# Full_bridge-2-Buck_drives_-_8.net
KiCad netlist of a schematic drawn in Altium Designer
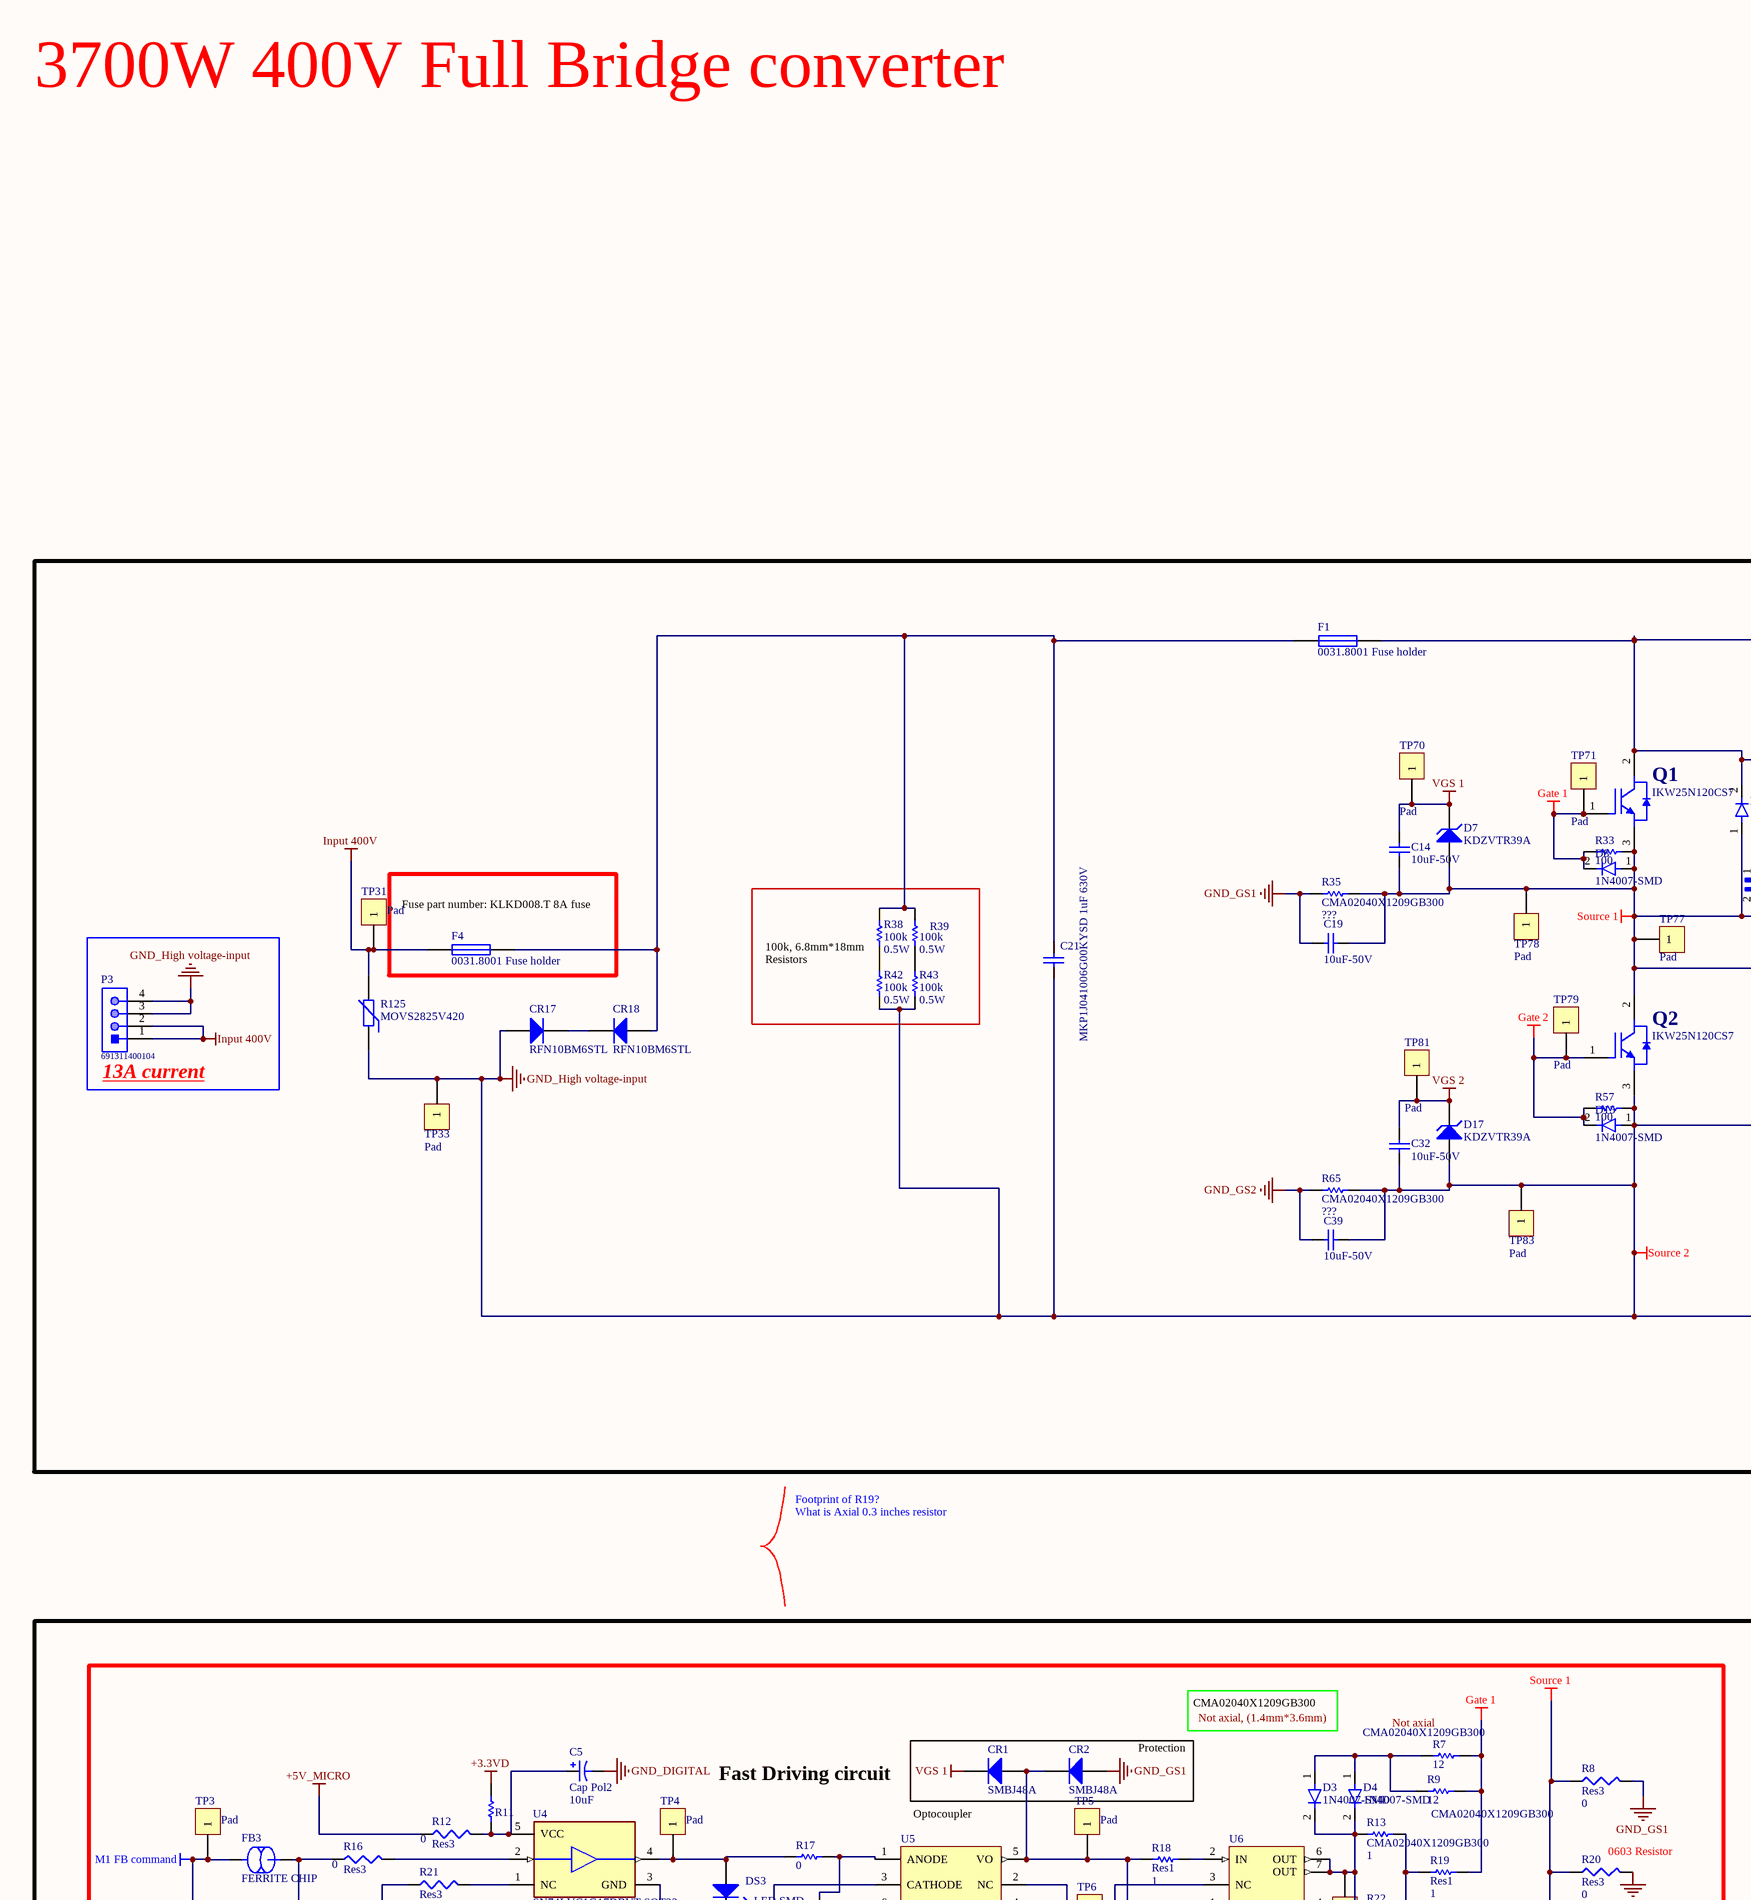
[diagram p0: Full bridge-2-Buck drives - 8.SchDoc, top left]
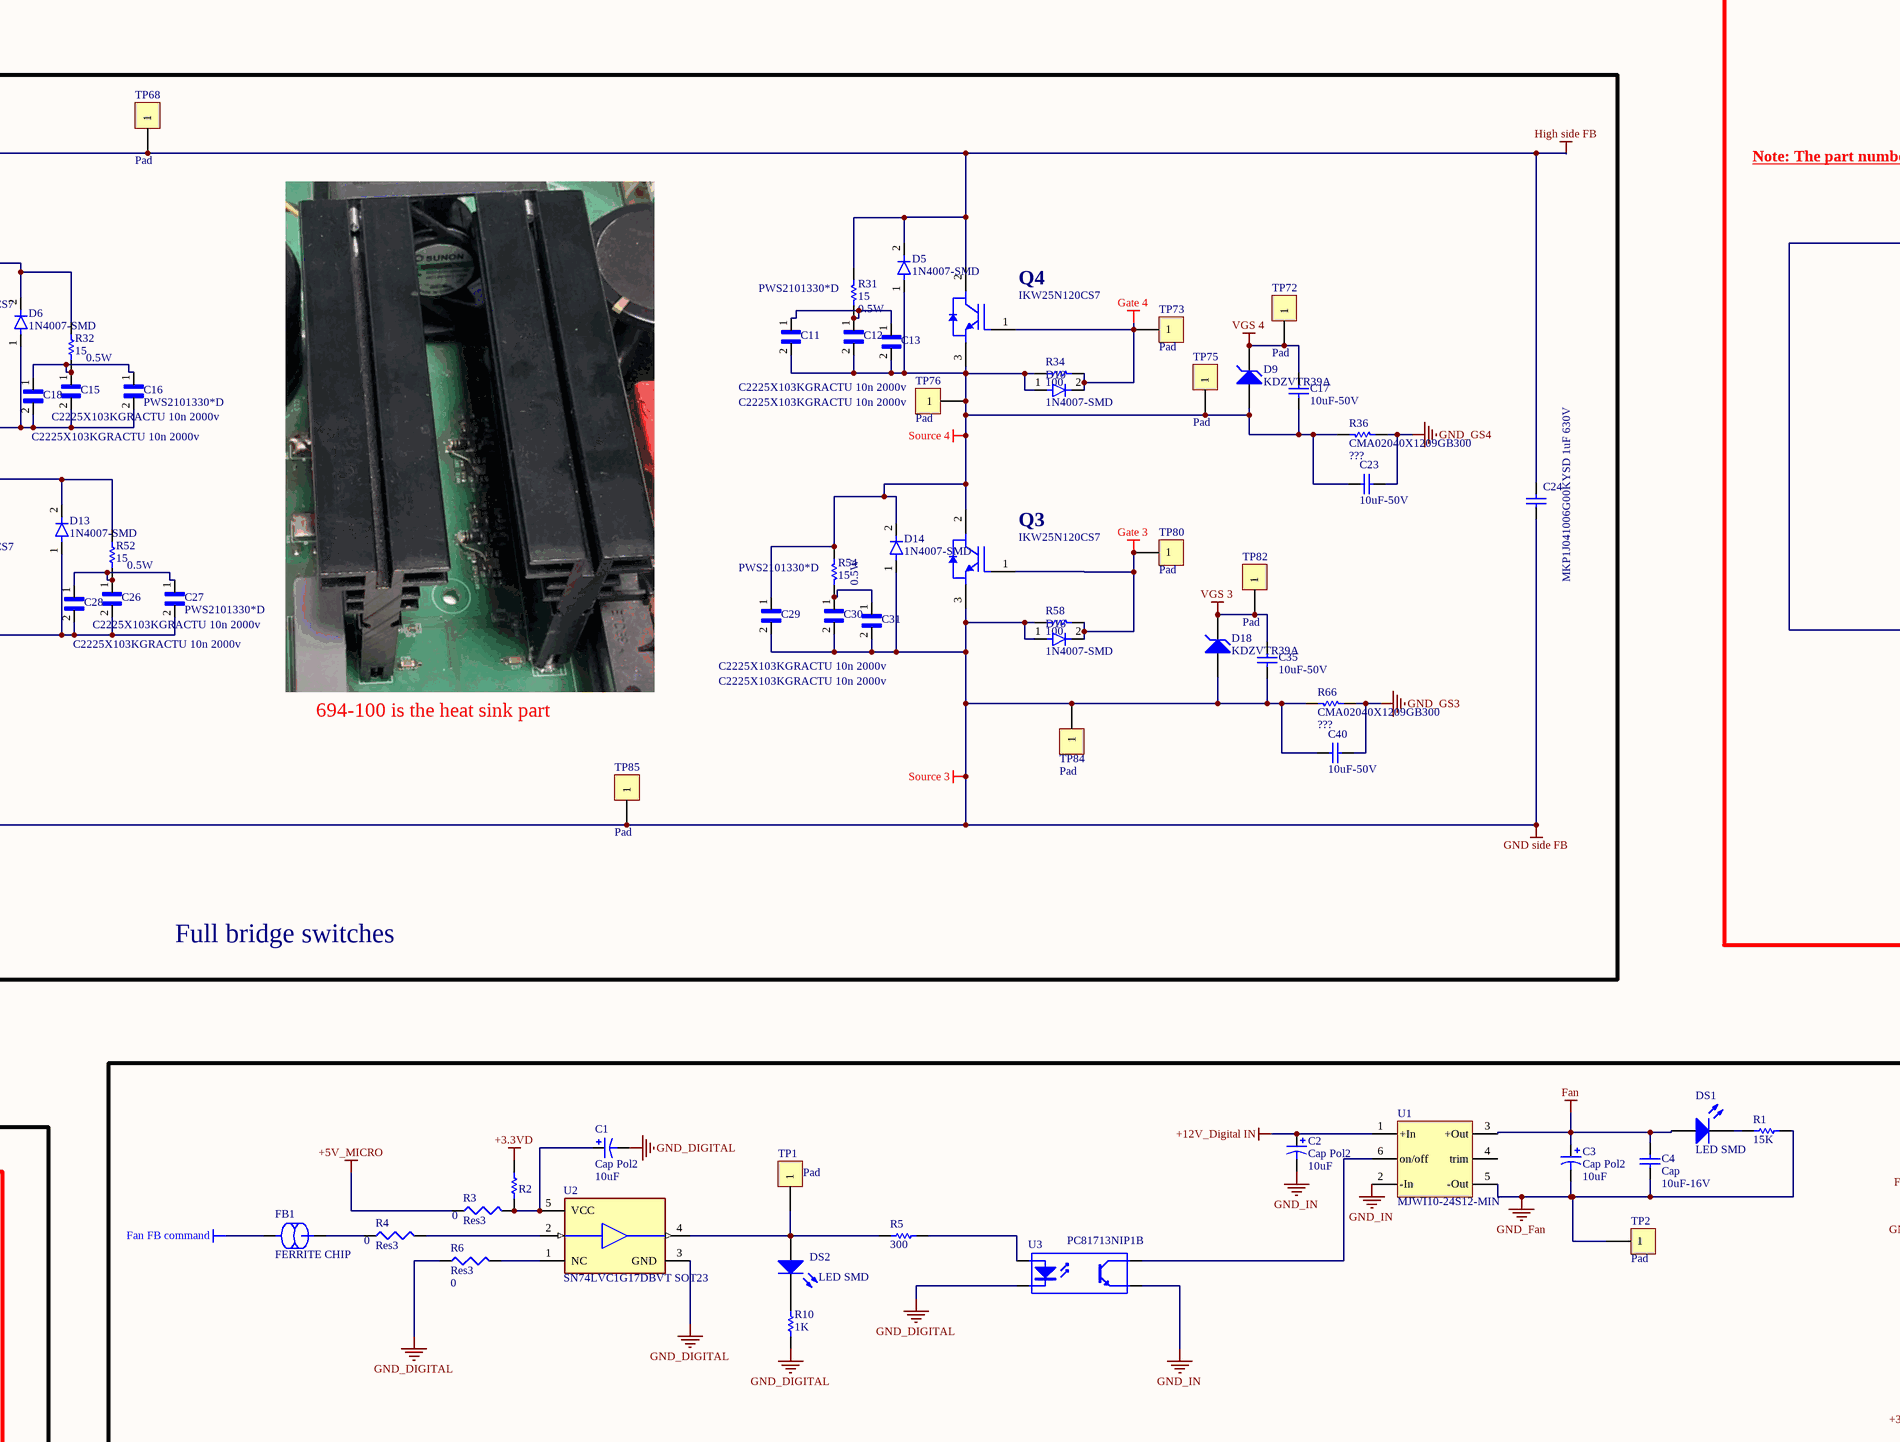
[diagram p1: Full bridge-2-Buck drives - 8.SchDoc, top middle]
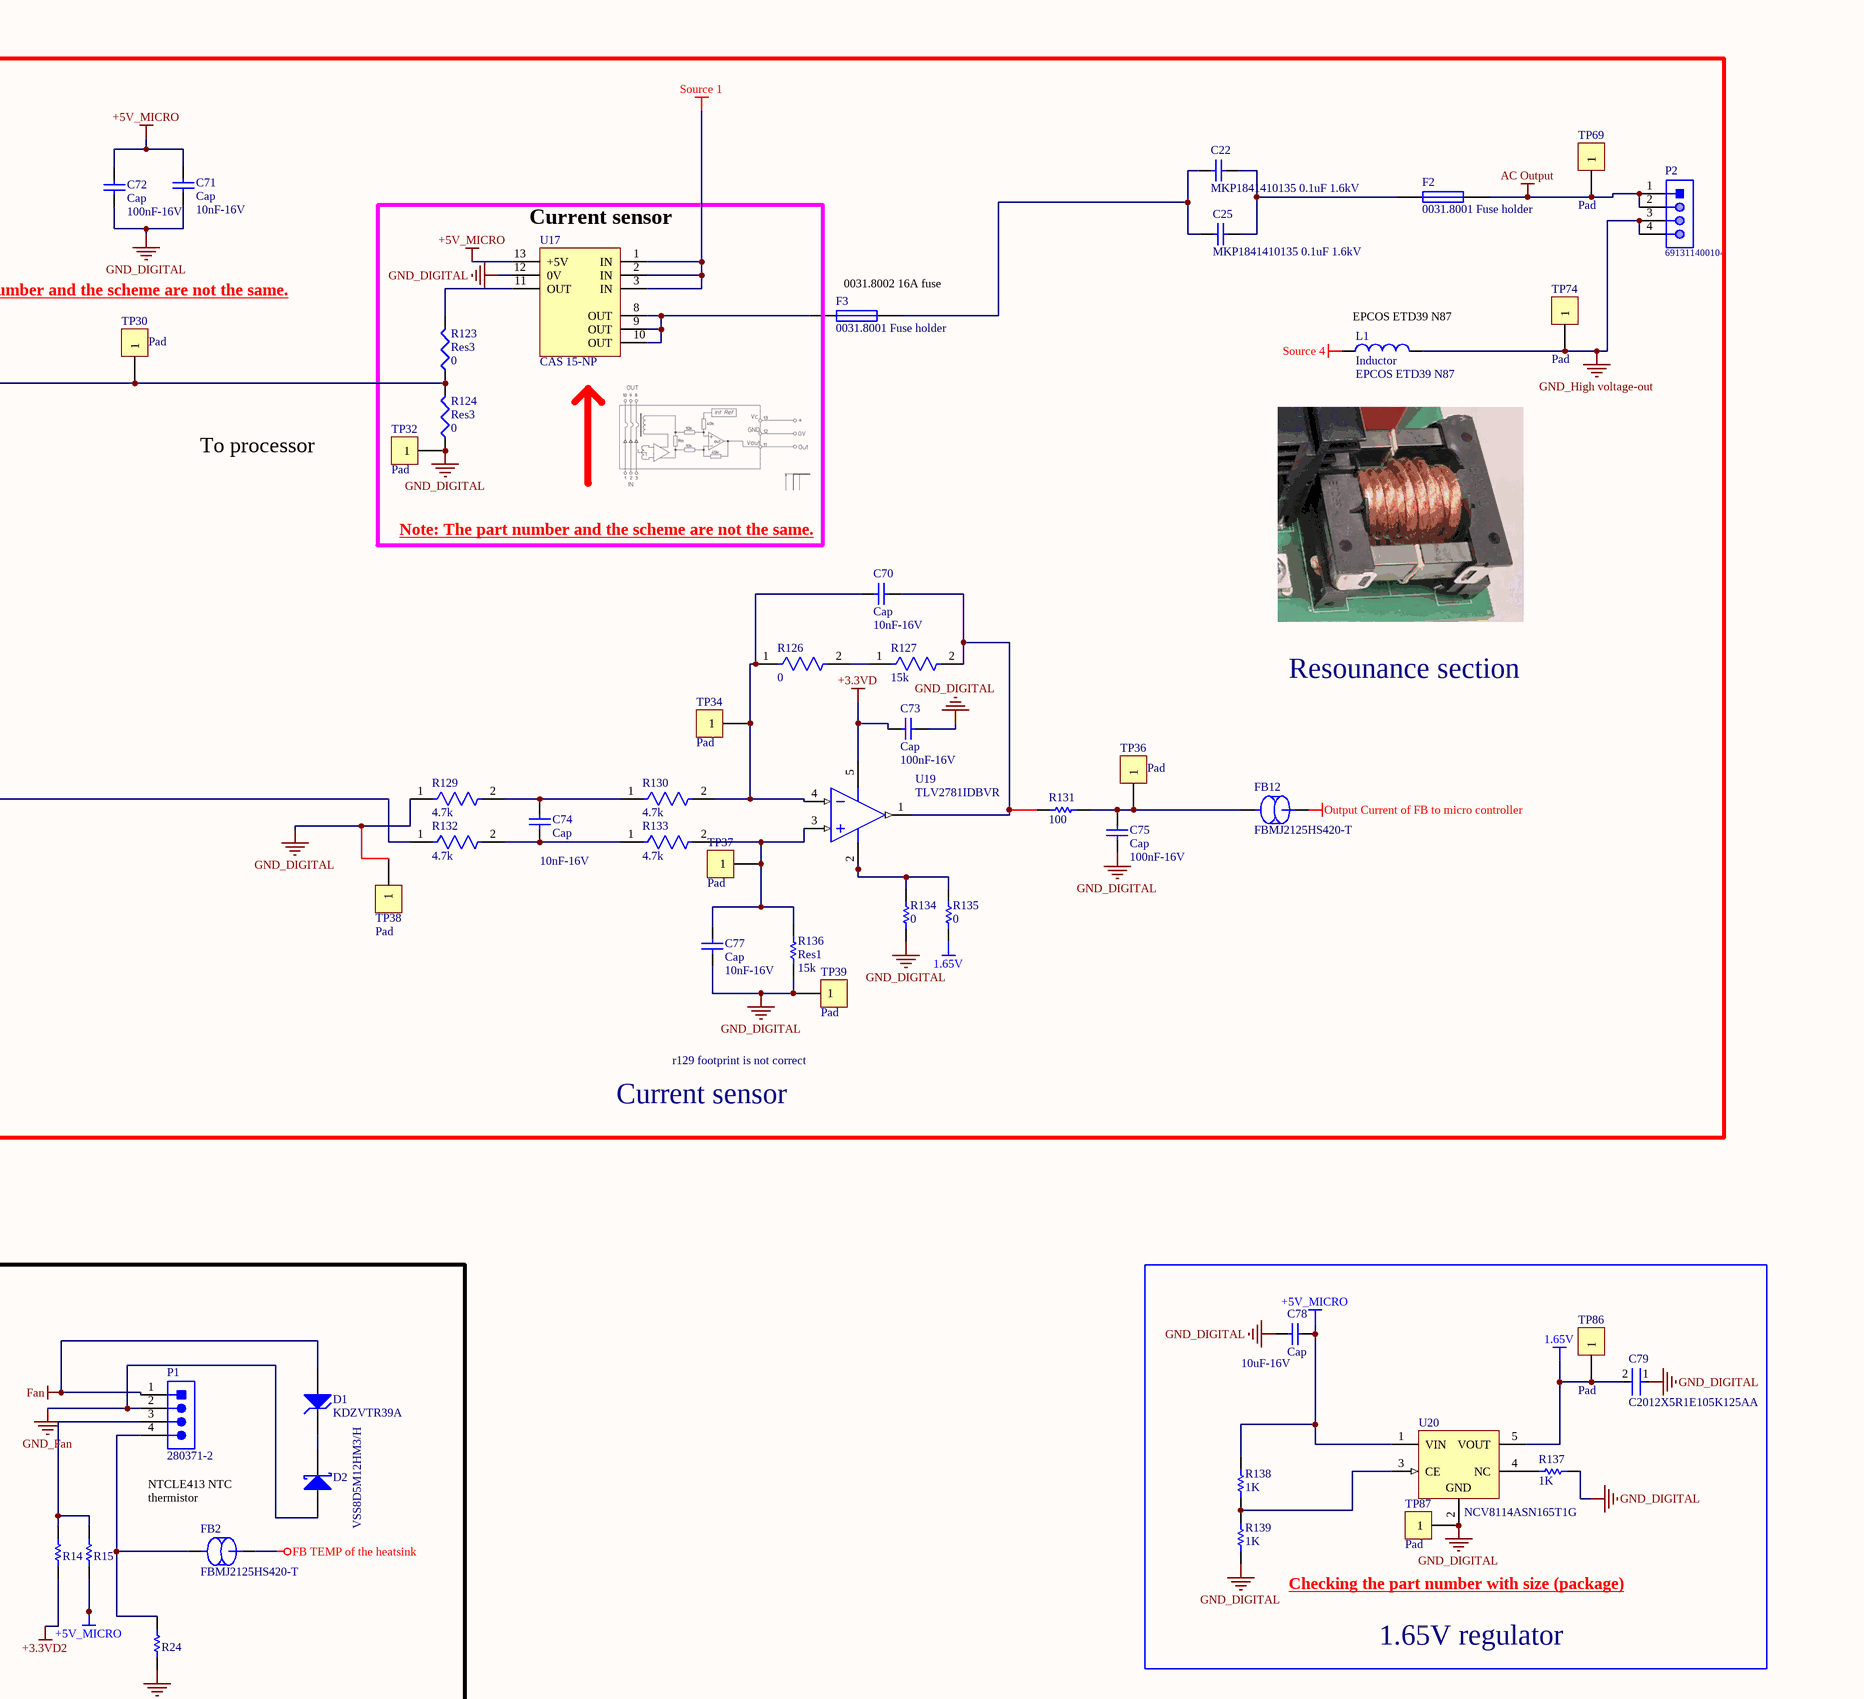
[diagram p2: Full bridge-2-Buck drives - 8.SchDoc, top right]
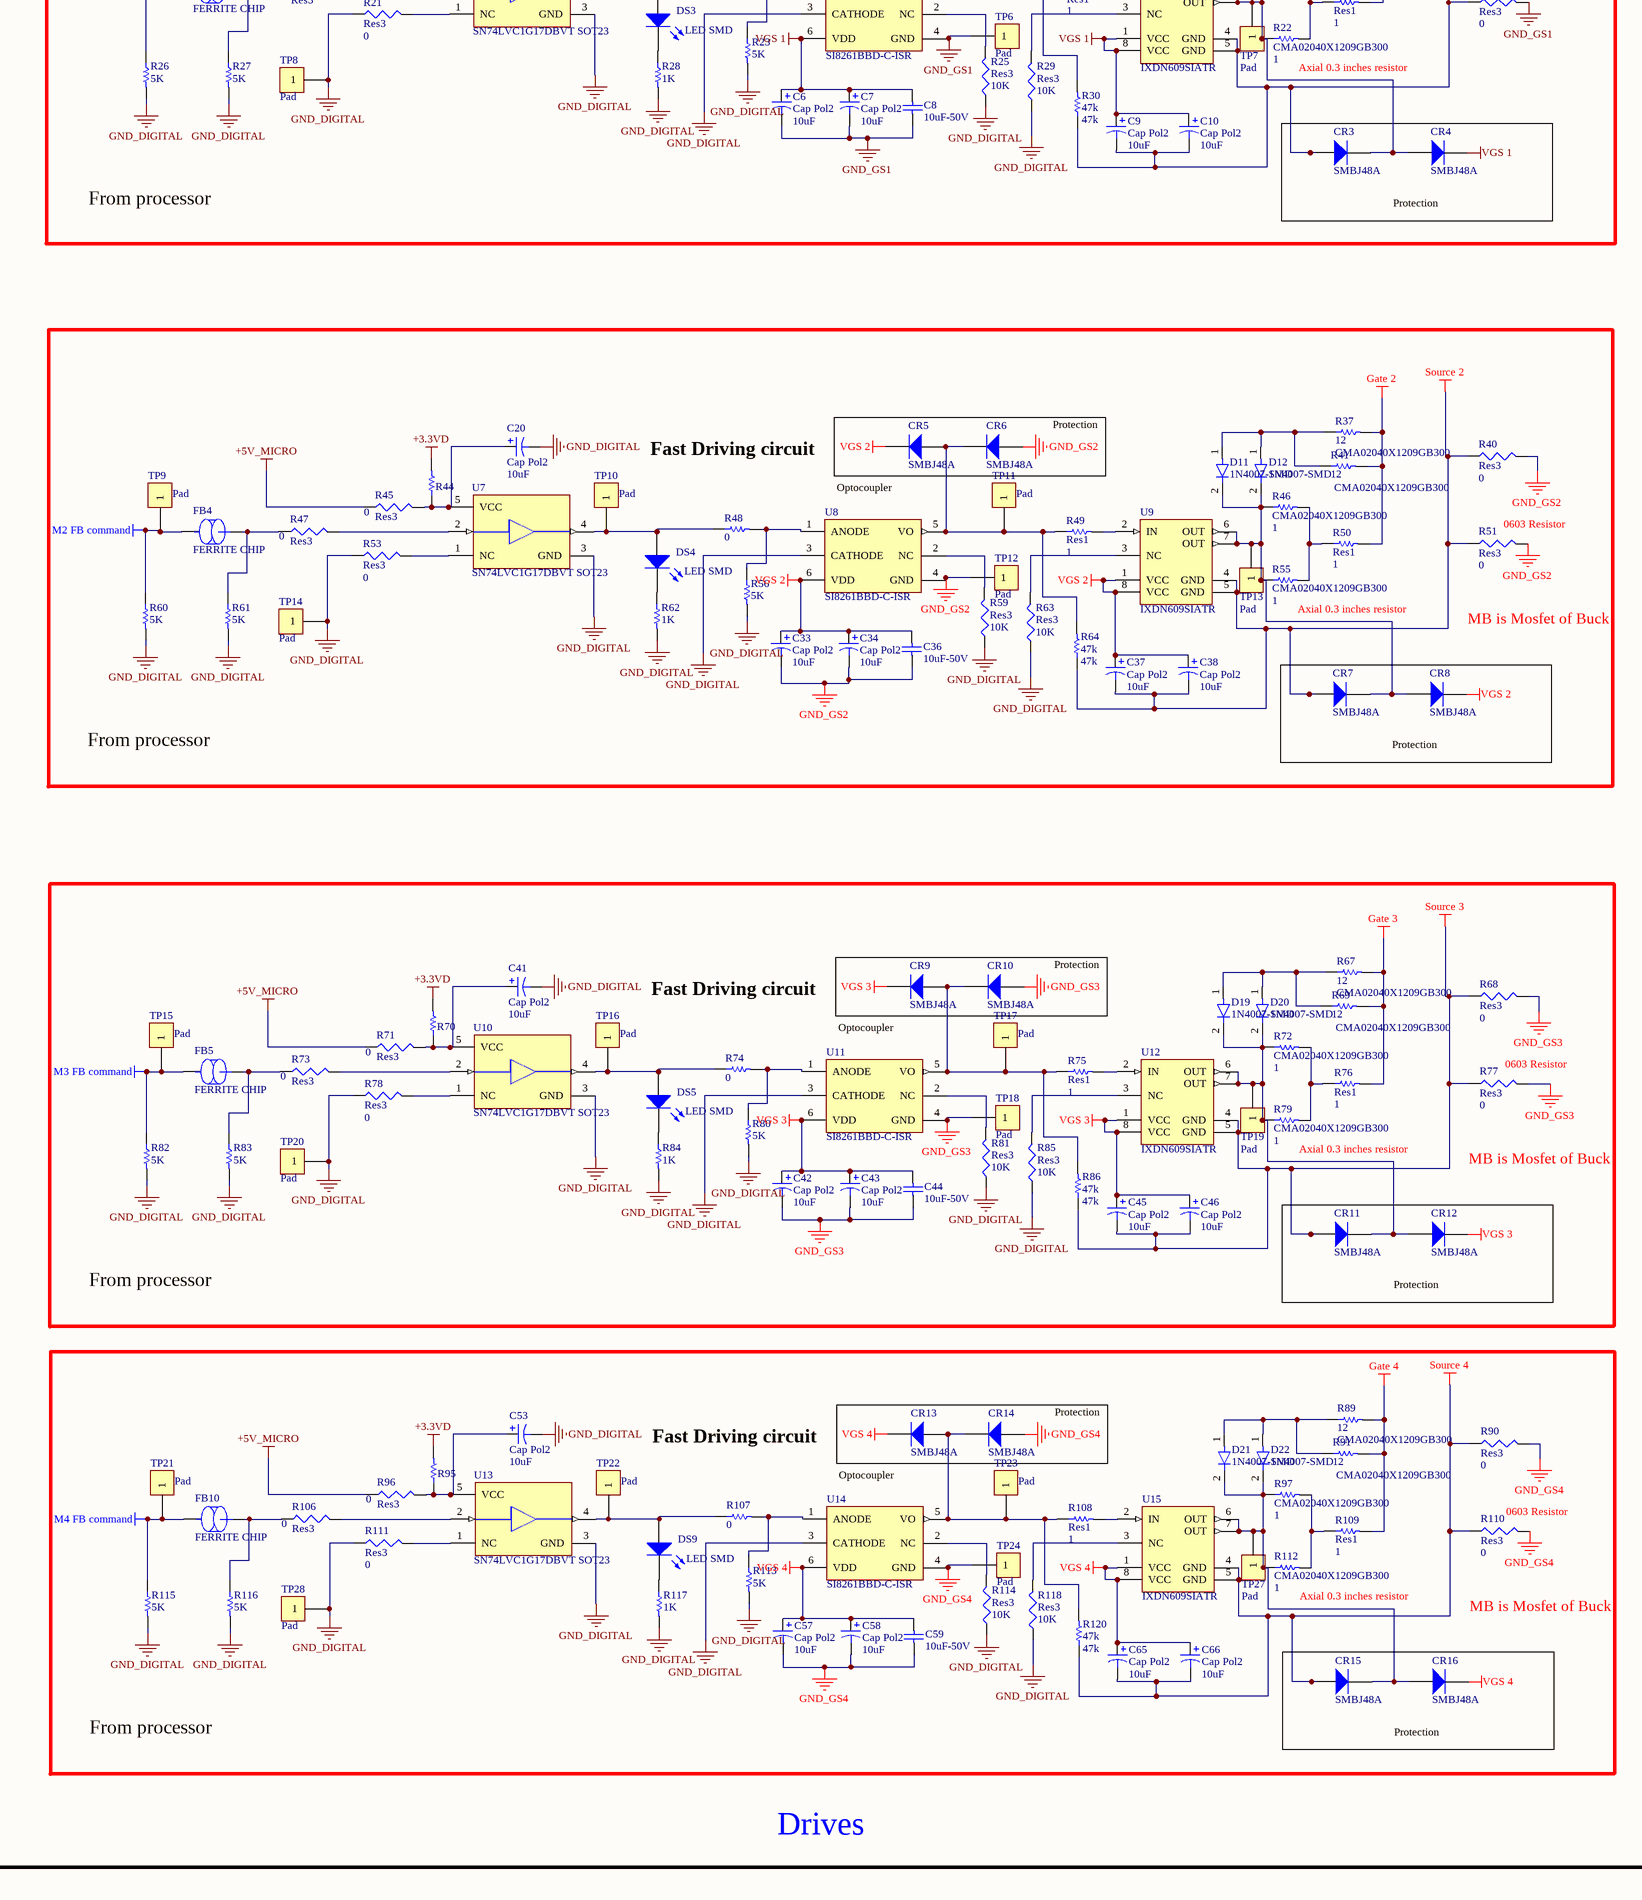
[diagram p3: Full bridge-2-Buck drives - 8.SchDoc, bottom left]
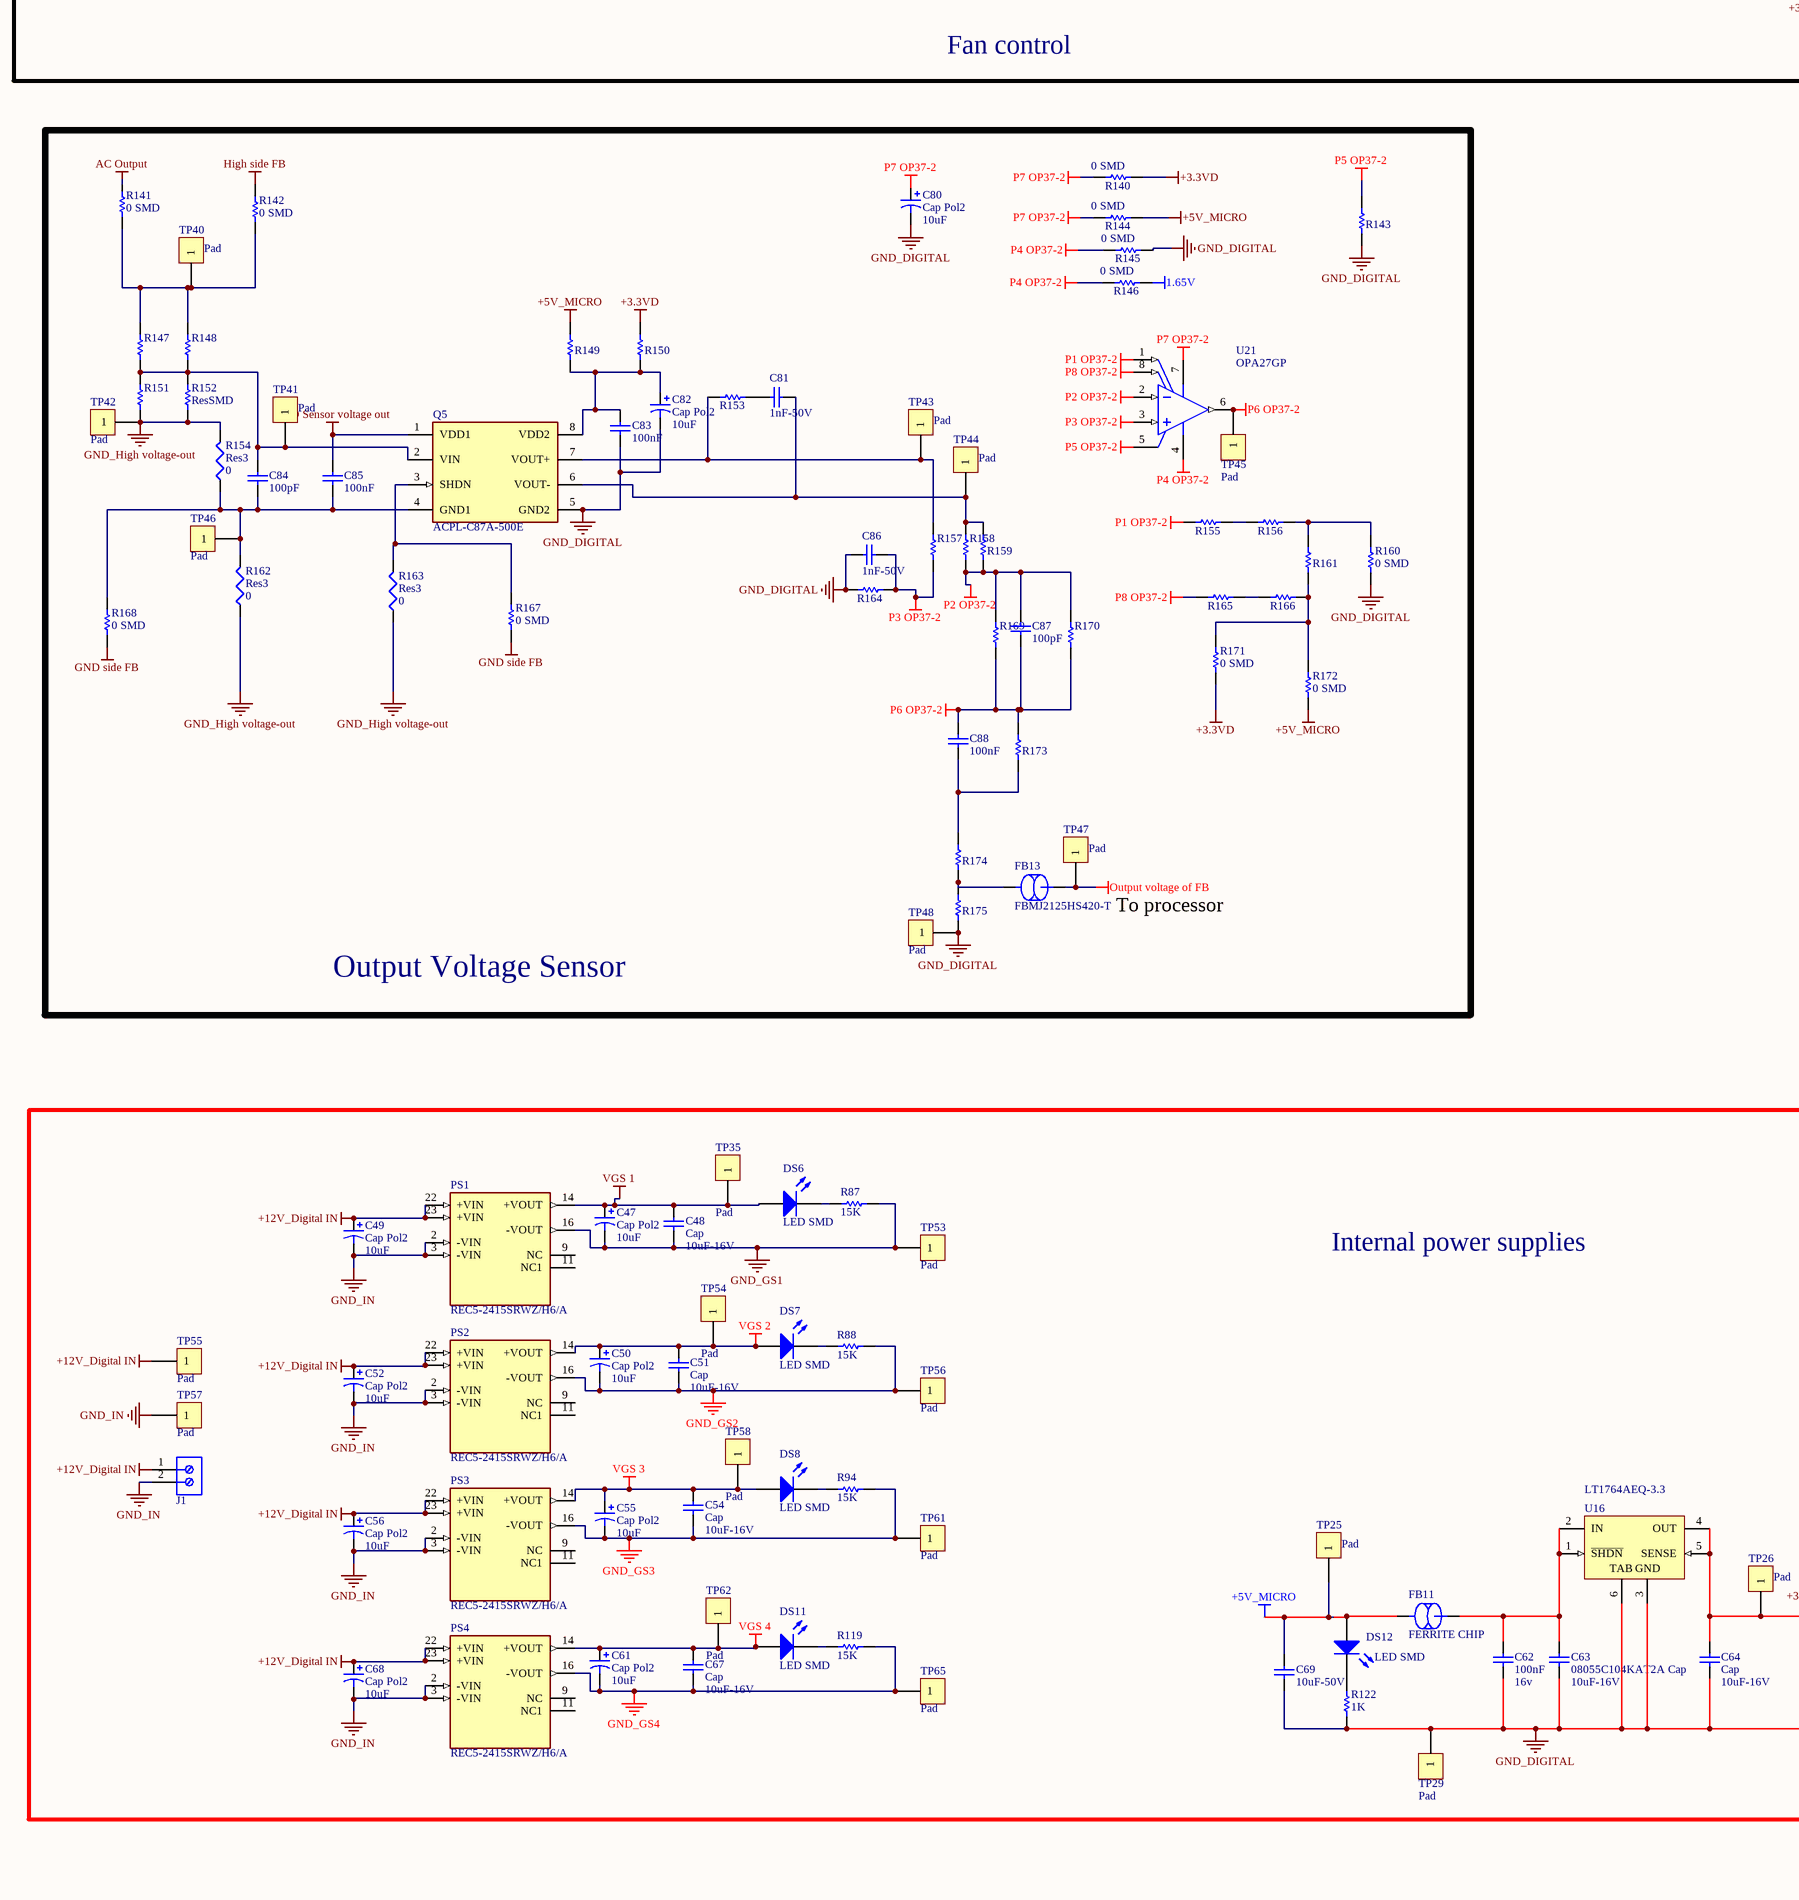
[diagram p4: Full bridge-2-Buck drives - 8.SchDoc, bottom middle]
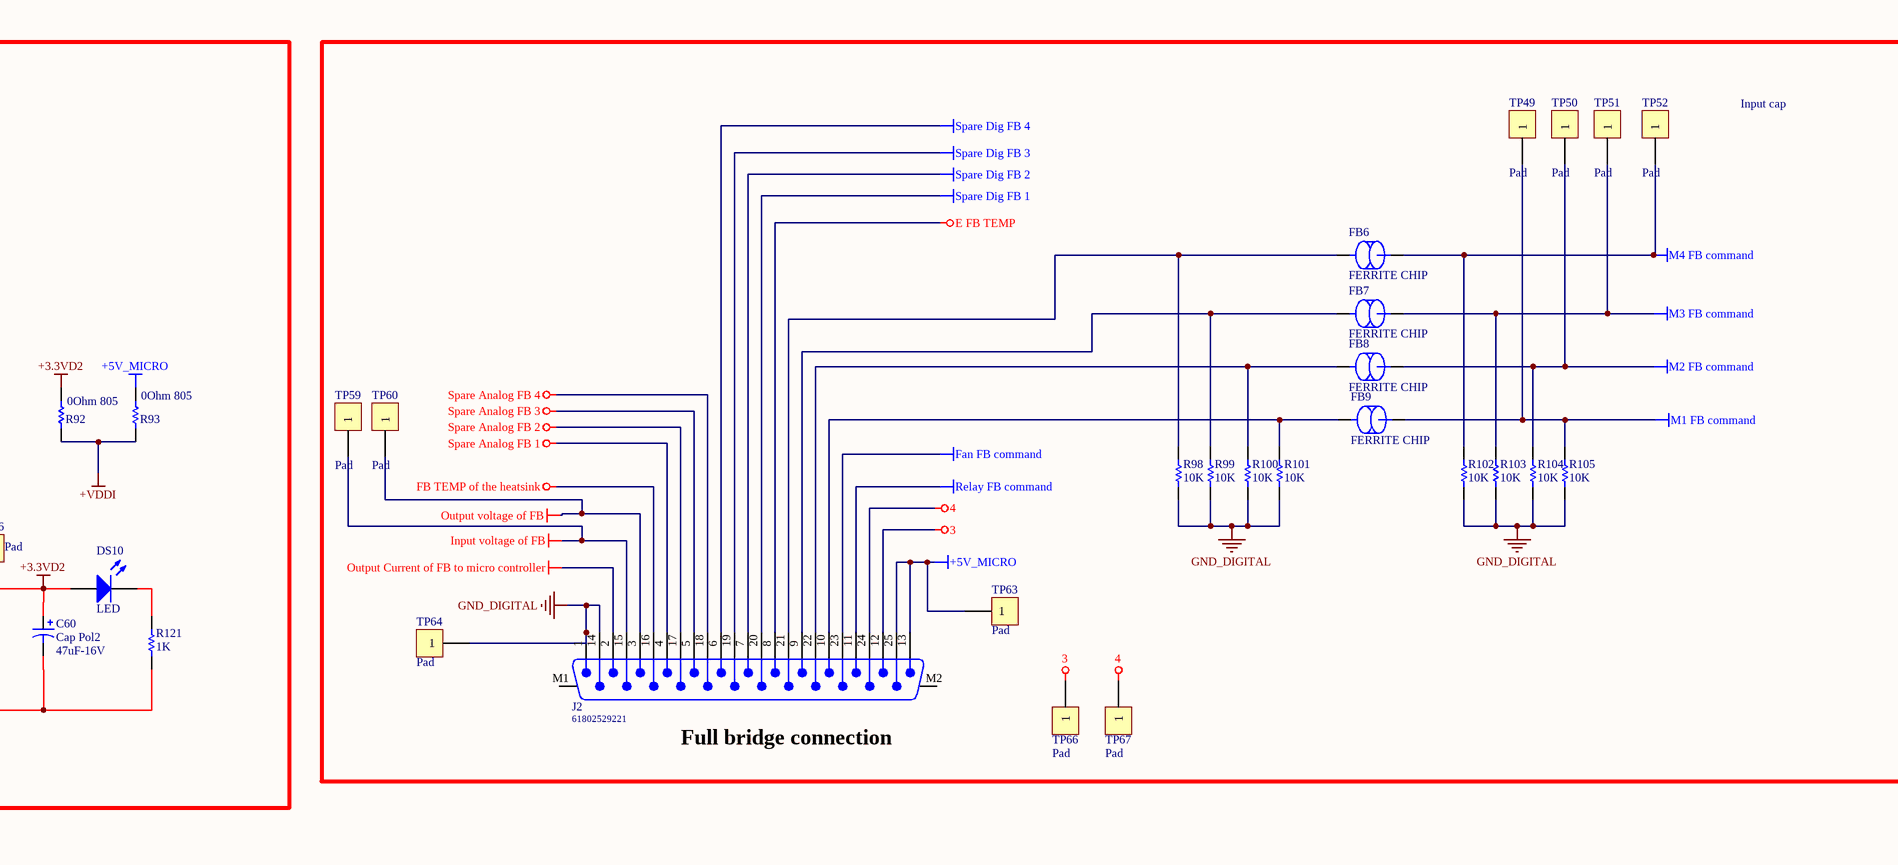
[diagram p5: Full bridge-2-Buck drives - 8.SchDoc, bottom right]

(export (version "E")
  (design (tool "Eeschema 10.0.6"))
  (components
    (comp (ref "C1")
      (value "Cap Pol2")
      (footprint "Buck:CAPAE430X565N")
      (description "Polarized Capacitor (Axial)")
      (fields (field (name "ALTIUM_VALUE") "10uF") (field (name "PUBLISHER") "Altium Limited"))
      (libsource (lib "SCH") (part "Cap Pol2"))
    )
    (comp (ref "C2")
      (value "Cap Pol2")
      (footprint "Buck:CAPAE430X565N")
      (description "Polarized Capacitor (Axial)")
      (fields (field (name "ALTIUM_VALUE") "10uF") (field (name "PUBLISHER") "Altium Limited"))
      (libsource (lib "SCH") (part "Cap Pol2"))
    )
    (comp (ref "C3")
      (value "Cap Pol2")
      (footprint "Buck:CAPAE430X565N")
      (description "Polarized Capacitor (Axial)")
      (fields (field (name "ALTIUM_VALUE") "10uF") (field (name "PUBLISHER") "Altium Limited"))
      (libsource (lib "SCH") (part "Cap Pol2"))
    )
    (comp (ref "C4")
      (value "Cap")
      (footprint "Buck:C0805")
      (description "Capacitor")
      (fields (field (name "ALTIUM_VALUE") "10uF-16V") (field (name "PUBLISHER") "Altium Limited"))
      (libsource (lib "SCH") (part "Cap"))
    )
    (comp (ref "C5")
      (value "Cap Pol2")
      (footprint "Buck:CAPAE430X565N")
      (description "Polarized Capacitor (Axial)")
      (fields (field (name "ALTIUM_VALUE") "10uF") (field (name "PUBLISHER") "Altium Limited"))
      (libsource (lib "SCH") (part "Cap Pol2"))
    )
    (comp (ref "C6")
      (value "Cap Pol2")
      (footprint "Buck:CAPAE430X565N")
      (description "Polarized Capacitor (Axial)")
      (fields (field (name "ALTIUM_VALUE") "10uF") (field (name "PUBLISHER") "Altium Limited"))
      (libsource (lib "SCH") (part "Cap Pol2"))
    )
    (comp (ref "C7")
      (value "Cap Pol2")
      (footprint "Buck:CAPAE430X565N")
      (description "Polarized Capacitor (Axial)")
      (fields (field (name "ALTIUM_VALUE") "10uF") (field (name "PUBLISHER") "Altium Limited"))
      (libsource (lib "SCH") (part "Cap Pol2"))
    )
    (comp (ref "C8") (value "10uF-50V") (footprint "Buck:C0805") (libsource (lib "MYLIB") (part "CapSMD")))
    (comp (ref "C9")
      (value "Cap Pol2")
      (footprint "Buck:CAPAE430X565N")
      (description "Polarized Capacitor (Axial)")
      (fields (field (name "ALTIUM_VALUE") "10uF") (field (name "PUBLISHER") "Altium Limited"))
      (libsource (lib "SCH") (part "Cap Pol2"))
    )
    (comp (ref "C10")
      (value "Cap Pol2")
      (footprint "Buck:CAPAE430X565N")
      (description "Polarized Capacitor (Axial)")
      (fields (field (name "ALTIUM_VALUE") "10uF") (field (name "PUBLISHER") "Altium Limited"))
      (libsource (lib "SCH") (part "Cap Pol2"))
    )
    (comp (ref "C11")
      (value "PWS2101330*D")
      (footprint "Buck:PWS2101330KD")
      (fields (field (name "MF") "AVX") (field (name "MP") "LD052C153JAB2A"))
      (libsource (lib "") (part "Ceramic disk capacitor_1"))
    )
    (comp (ref "C12")
      (value "C2225X103KGRACTU 10n 2000v")
      (footprint "Buck:C2225")
      (fields (field (name "MF") "AVX") (field (name "MP") "LD052C153JAB2A"))
      (libsource (lib "") (part "Ceramic disk capacitor_1"))
    )
    (comp (ref "C13")
      (value "C2225X103KGRACTU 10n 2000v")
      (footprint "Buck:C2225")
      (fields (field (name "MF") "AVX") (field (name "MP") "LD052C153JAB2A"))
      (libsource (lib "") (part "Ceramic disk capacitor_1"))
    )
    (comp (ref "C14") (value "10uF-50V") (footprint "Buck:C0805") (libsource (lib "MYLIB") (part "CapSMD")))
    (comp (ref "C15")
      (value "C2225X103KGRACTU 10n 2000v")
      (footprint "Buck:C2225")
      (fields (field (name "MF") "AVX") (field (name "MP") "LD052C153JAB2A"))
      (libsource (lib "Capacitors dip") (part "Ceramic disk capacitor"))
    )
    (comp (ref "C16")
      (value "PWS2101330*D")
      (footprint "Buck:PWS2101330KD")
      (fields (field (name "MF") "AVX") (field (name "MP") "LD052C153JAB2A"))
      (libsource (lib "Capacitors dip") (part "Ceramic disk capacitor"))
    )
    (comp (ref "C17") (value "10uF-50V") (footprint "Buck:C0805") (libsource (lib "MYLIB") (part "CapSMD")))
    (comp (ref "C18")
      (value "C2225X103KGRACTU 10n 2000v")
      (footprint "Buck:C2225")
      (fields (field (name "MF") "AVX") (field (name "MP") "LD052C153JAB2A"))
      (libsource (lib "Capacitors dip") (part "Ceramic disk capacitor"))
    )
    (comp (ref "C19") (value "10uF-50V") (footprint "Buck:C0805") (libsource (lib "MYLIB") (part "CapSMD")))
    (comp (ref "C20")
      (value "Cap Pol2")
      (footprint "Buck:CAPAE430X565N")
      (description "Polarized Capacitor (Axial)")
      (fields (field (name "ALTIUM_VALUE") "10uF") (field (name "PUBLISHER") "Altium Limited"))
      (libsource (lib "SCH") (part "Cap Pol2"))
    )
    (comp (ref "C21")
      (value "MKP1J041006G00KYSD 1uF 630V")
      (footprint "Buck:MKP10_31x17-P27.5mm")
      (libsource (lib "") (part "CapSMD_1"))
    )
    (comp (ref "C22")
      (value "MKP1841410135 0.1uF 1.6kV")
      (footprint "Buck:MKP1841410135")
      (libsource (lib "") (part "CapSMD_1"))
    )
    (comp (ref "C23") (value "10uF-50V") (footprint "Buck:C0805") (libsource (lib "MYLIB") (part "CapSMD")))
    (comp (ref "C24")
      (value "MKP1J041006G00KYSD 1uF 630V")
      (footprint "Buck:MKP10_31x17-P27.5mm")
      (libsource (lib "") (part "CapSMD_1"))
    )
    (comp (ref "C25")
      (value "MKP1841410135 0.1uF 1.6kV")
      (footprint "Buck:MKP1841410135")
      (libsource (lib "") (part "CapSMD_1"))
    )
    (comp (ref "C26")
      (value "C2225X103KGRACTU 10n 2000v")
      (footprint "Buck:C2225")
      (fields (field (name "MF") "AVX") (field (name "MP") "LD052C153JAB2A"))
      (libsource (lib "Capacitors dip") (part "Ceramic disk capacitor"))
    )
    (comp (ref "C27")
      (value "PWS2101330*D")
      (footprint "Buck:PWS2101330KD")
      (fields (field (name "MF") "AVX") (field (name "MP") "LD052C153JAB2A"))
      (libsource (lib "Capacitors dip") (part "Ceramic disk capacitor"))
    )
    (comp (ref "C28")
      (value "C2225X103KGRACTU 10n 2000v")
      (footprint "Buck:C2225")
      (fields (field (name "MF") "AVX") (field (name "MP") "LD052C153JAB2A"))
      (libsource (lib "Capacitors dip") (part "Ceramic disk capacitor"))
    )
    (comp (ref "C29")
      (value "PWS2101330*D")
      (footprint "Buck:PWS2101330KD")
      (fields (field (name "MF") "AVX") (field (name "MP") "LD052C153JAB2A"))
      (libsource (lib "") (part "Ceramic disk capacitor_1"))
    )
    (comp (ref "C30")
      (value "C2225X103KGRACTU 10n 2000v")
      (footprint "Buck:C2225")
      (fields (field (name "MF") "AVX") (field (name "MP") "LD052C153JAB2A"))
      (libsource (lib "") (part "Ceramic disk capacitor_1"))
    )
    (comp (ref "C31")
      (value "C2225X103KGRACTU 10n 2000v")
      (footprint "Buck:C2225")
      (fields (field (name "MF") "AVX") (field (name "MP") "LD052C153JAB2A"))
      (libsource (lib "") (part "Ceramic disk capacitor_1"))
    )
    (comp (ref "C32") (value "10uF-50V") (footprint "Buck:C0805") (libsource (lib "MYLIB") (part "CapSMD")))
    (comp (ref "C33")
      (value "Cap Pol2")
      (footprint "Buck:CAPAE430X565N")
      (description "Polarized Capacitor (Axial)")
      (fields (field (name "ALTIUM_VALUE") "10uF") (field (name "PUBLISHER") "Altium Limited"))
      (libsource (lib "SCH") (part "Cap Pol2"))
    )
    (comp (ref "C34")
      (value "Cap Pol2")
      (footprint "Buck:CAPAE430X565N")
      (description "Polarized Capacitor (Axial)")
      (fields (field (name "ALTIUM_VALUE") "10uF") (field (name "PUBLISHER") "Altium Limited"))
      (libsource (lib "SCH") (part "Cap Pol2"))
    )
    (comp (ref "C35") (value "10uF-50V") (footprint "Buck:C0805") (libsource (lib "MYLIB") (part "CapSMD")))
    (comp (ref "C36") (value "10uF-50V") (footprint "Buck:C0805") (libsource (lib "MYLIB") (part "CapSMD")))
    (comp (ref "C37")
      (value "Cap Pol2")
      (footprint "Buck:CAPAE430X565N")
      (description "Polarized Capacitor (Axial)")
      (fields (field (name "ALTIUM_VALUE") "10uF") (field (name "PUBLISHER") "Altium Limited"))
      (libsource (lib "SCH") (part "Cap Pol2"))
    )
    (comp (ref "C38")
      (value "Cap Pol2")
      (footprint "Buck:CAPAE430X565N")
      (description "Polarized Capacitor (Axial)")
      (fields (field (name "ALTIUM_VALUE") "10uF") (field (name "PUBLISHER") "Altium Limited"))
      (libsource (lib "SCH") (part "Cap Pol2"))
    )
    (comp (ref "C39") (value "10uF-50V") (footprint "Buck:C0805") (libsource (lib "MYLIB") (part "CapSMD")))
    (comp (ref "C40") (value "10uF-50V") (footprint "Buck:C0805") (libsource (lib "MYLIB") (part "CapSMD")))
    (comp (ref "C41")
      (value "Cap Pol2")
      (footprint "Buck:CAPAE430X565N")
      (description "Polarized Capacitor (Axial)")
      (fields (field (name "ALTIUM_VALUE") "10uF") (field (name "PUBLISHER") "Altium Limited"))
      (libsource (lib "SCH") (part "Cap Pol2"))
    )
    (comp (ref "C42")
      (value "Cap Pol2")
      (footprint "Buck:CAPAE430X565N")
      (description "Polarized Capacitor (Axial)")
      (fields (field (name "ALTIUM_VALUE") "10uF") (field (name "PUBLISHER") "Altium Limited"))
      (libsource (lib "SCH") (part "Cap Pol2"))
    )
    (comp (ref "C43")
      (value "Cap Pol2")
      (footprint "Buck:CAPAE430X565N")
      (description "Polarized Capacitor (Axial)")
      (fields (field (name "ALTIUM_VALUE") "10uF") (field (name "PUBLISHER") "Altium Limited"))
      (libsource (lib "SCH") (part "Cap Pol2"))
    )
    (comp (ref "C44") (value "10uF-50V") (footprint "Buck:C0805") (libsource (lib "MYLIB") (part "CapSMD")))
    (comp (ref "C45")
      (value "Cap Pol2")
      (footprint "Buck:CAPAE430X565N")
      (description "Polarized Capacitor (Axial)")
      (fields (field (name "ALTIUM_VALUE") "10uF") (field (name "PUBLISHER") "Altium Limited"))
      (libsource (lib "SCH") (part "Cap Pol2"))
    )
    (comp (ref "C46")
      (value "Cap Pol2")
      (footprint "Buck:CAPAE430X565N")
      (description "Polarized Capacitor (Axial)")
      (fields (field (name "ALTIUM_VALUE") "10uF") (field (name "PUBLISHER") "Altium Limited"))
      (libsource (lib "SCH") (part "Cap Pol2"))
    )
    (comp (ref "C47")
      (value "Cap Pol2")
      (footprint "Buck:CAPAE430X565N")
      (description "Polarized Capacitor (Axial)")
      (fields (field (name "ALTIUM_VALUE") "10uF") (field (name "PUBLISHER") "Altium Limited"))
      (libsource (lib "SCH") (part "Cap Pol2"))
    )
    (comp (ref "C48")
      (value "Cap")
      (footprint "Buck:C0805")
      (description "Capacitor")
      (fields (field (name "ALTIUM_VALUE") "10uF-16V") (field (name "PUBLISHER") "Altium Limited"))
      (libsource (lib "SCH") (part "Cap"))
    )
    (comp (ref "C49")
      (value "Cap Pol2")
      (footprint "Buck:CAPAE430X565N")
      (description "Polarized Capacitor (Axial)")
      (fields (field (name "ALTIUM_VALUE") "10uF") (field (name "PUBLISHER") "Altium Limited"))
      (libsource (lib "SCH") (part "Cap Pol2"))
    )
    (comp (ref "C50")
      (value "Cap Pol2")
      (footprint "Buck:CAPAE430X565N")
      (description "Polarized Capacitor (Axial)")
      (fields (field (name "ALTIUM_VALUE") "10uF") (field (name "PUBLISHER") "Altium Limited"))
      (libsource (lib "SCH") (part "Cap Pol2"))
    )
    (comp (ref "C51")
      (value "Cap")
      (footprint "Buck:C0805")
      (description "Capacitor")
      (fields (field (name "ALTIUM_VALUE") "10uF-16V") (field (name "PUBLISHER") "Altium Limited"))
      (libsource (lib "SCH") (part "Cap"))
    )
    (comp (ref "C52")
      (value "Cap Pol2")
      (footprint "Buck:CAPAE430X565N")
      (description "Polarized Capacitor (Axial)")
      (fields (field (name "ALTIUM_VALUE") "10uF") (field (name "PUBLISHER") "Altium Limited"))
      (libsource (lib "SCH") (part "Cap Pol2"))
    )
    (comp (ref "C53")
      (value "Cap Pol2")
      (footprint "Buck:CAPAE430X565N")
      (description "Polarized Capacitor (Axial)")
      (fields (field (name "ALTIUM_VALUE") "10uF") (field (name "PUBLISHER") "Altium Limited"))
      (libsource (lib "SCH") (part "Cap Pol2"))
    )
    (comp (ref "C54")
      (value "Cap")
      (footprint "Buck:C0805")
      (description "Capacitor")
      (fields (field (name "ALTIUM_VALUE") "10uF-16V") (field (name "PUBLISHER") "Altium Limited"))
      (libsource (lib "SCH") (part "Cap"))
    )
    (comp (ref "C55")
      (value "Cap Pol2")
      (footprint "Buck:CAPAE430X565N")
      (description "Polarized Capacitor (Axial)")
      (fields (field (name "ALTIUM_VALUE") "10uF") (field (name "PUBLISHER") "Altium Limited"))
      (libsource (lib "SCH") (part "Cap Pol2"))
    )
    (comp (ref "C56")
      (value "Cap Pol2")
      (footprint "Buck:CAPAE430X565N")
      (description "Polarized Capacitor (Axial)")
      (fields (field (name "ALTIUM_VALUE") "10uF") (field (name "PUBLISHER") "Altium Limited"))
      (libsource (lib "SCH") (part "Cap Pol2"))
    )
    (comp (ref "C57")
      (value "Cap Pol2")
      (footprint "Buck:CAPAE430X565N")
      (description "Polarized Capacitor (Axial)")
      (fields (field (name "ALTIUM_VALUE") "10uF") (field (name "PUBLISHER") "Altium Limited"))
      (libsource (lib "SCH") (part "Cap Pol2"))
    )
    (comp (ref "C58")
      (value "Cap Pol2")
      (footprint "Buck:CAPAE430X565N")
      (description "Polarized Capacitor (Axial)")
      (fields (field (name "ALTIUM_VALUE") "10uF") (field (name "PUBLISHER") "Altium Limited"))
      (libsource (lib "SCH") (part "Cap Pol2"))
    )
    (comp (ref "C59") (value "10uF-50V") (footprint "Buck:C0805") (libsource (lib "MYLIB") (part "CapSMD")))
    (comp (ref "C60")
      (value "Cap Pol2")
      (footprint "Buck:CAPAE430X565N")
      (description "Polarized Capacitor (Axial)")
      (fields (field (name "ALTIUM_VALUE") "47uF-16V") (field (name "PUBLISHER") "Altium Limited"))
      (libsource (lib "SCH") (part "Cap Pol2"))
    )
    (comp (ref "C61")
      (value "Cap Pol2")
      (footprint "Buck:CAPAE430X565N")
      (description "Polarized Capacitor (Axial)")
      (fields (field (name "ALTIUM_VALUE") "10uF") (field (name "PUBLISHER") "Altium Limited"))
      (libsource (lib "SCH") (part "Cap Pol2"))
    )
    (comp (ref "C62")
      (value "100nF")
      (footprint "Buck:C0805")
      (description "None polar capacitor")
      (fields (field (name "VOLTE") "16v"))
      (libsource (lib "Mylib") (part "Cap ceramic"))
    )
    (comp (ref "C63")
      (value "08055C104KAT2A Cap")
      (footprint "Buck:C0805")
      (description "Capacitor")
      (fields (field (name "ALTIUM_VALUE") "10uF-16V") (field (name "PUBLISHER") "Altium Limited"))
      (libsource (lib "SCH") (part "Cap"))
    )
    (comp (ref "C64")
      (value "Cap")
      (footprint "Buck:C0805")
      (description "Capacitor")
      (fields (field (name "ALTIUM_VALUE") "10uF-16V") (field (name "PUBLISHER") "Altium Limited"))
      (libsource (lib "SCH") (part "Cap"))
    )
    (comp (ref "C65")
      (value "Cap Pol2")
      (footprint "Buck:CAPAE430X565N")
      (description "Polarized Capacitor (Axial)")
      (fields (field (name "ALTIUM_VALUE") "10uF") (field (name "PUBLISHER") "Altium Limited"))
      (libsource (lib "SCH") (part "Cap Pol2"))
    )
    (comp (ref "C66")
      (value "Cap Pol2")
      (footprint "Buck:CAPAE430X565N")
      (description "Polarized Capacitor (Axial)")
      (fields (field (name "ALTIUM_VALUE") "10uF") (field (name "PUBLISHER") "Altium Limited"))
      (libsource (lib "SCH") (part "Cap Pol2"))
    )
    (comp (ref "C67")
      (value "Cap")
      (footprint "Buck:C0805")
      (description "Capacitor")
      (fields (field (name "ALTIUM_VALUE") "10uF-16V") (field (name "PUBLISHER") "Altium Limited"))
      (libsource (lib "SCH") (part "Cap"))
    )
    (comp (ref "C68")
      (value "Cap Pol2")
      (footprint "Buck:CAPAE430X565N")
      (description "Polarized Capacitor (Axial)")
      (fields (field (name "ALTIUM_VALUE") "10uF") (field (name "PUBLISHER") "Altium Limited"))
      (libsource (lib "SCH") (part "Cap Pol2"))
    )
    (comp (ref "C69") (value "10uF-50V") (footprint "Buck:C0805") (libsource (lib "MYLIB") (part "CapSMD")))
    (comp (ref "C70")
      (value "Cap")
      (footprint "Buck:C0805")
      (description "Capacitor")
      (fields (field (name "ALTIUM_VALUE") "10nF-16V") (field (name "PUBLISHER") "Altium Limited"))
      (libsource (lib "SCH") (part "Cap"))
    )
    (comp (ref "C71")
      (value "Cap")
      (footprint "Buck:C0805")
      (description "Capacitor")
      (fields (field (name "ALTIUM_VALUE") "10nF-16V") (field (name "PUBLISHER") "Altium Limited"))
      (libsource (lib "SCH") (part "Cap"))
    )
    (comp (ref "C72")
      (value "Cap")
      (footprint "Buck:C0805")
      (description "Capacitor")
      (fields (field (name "ALTIUM_VALUE") "100nF-16V") (field (name "PUBLISHER") "Altium Limited"))
      (libsource (lib "SCH") (part "Cap"))
    )
    (comp (ref "C73")
      (value "Cap")
      (footprint "Buck:C0805")
      (description "Capacitor")
      (fields (field (name "ALTIUM_VALUE") "100nF-16V") (field (name "PUBLISHER") "Altium Limited"))
      (libsource (lib "SCH") (part "Cap"))
    )
    (comp (ref "C74")
      (value "Cap")
      (footprint "Buck:C0805")
      (description "Capacitor")
      (fields (field (name "ALTIUM_VALUE") "10nF-16V") (field (name "PUBLISHER") "Altium Limited"))
      (libsource (lib "SCH") (part "Cap"))
    )
    (comp (ref "C75")
      (value "Cap")
      (footprint "Buck:C0805")
      (description "Capacitor")
      (fields (field (name "ALTIUM_VALUE") "100nF-16V") (field (name "PUBLISHER") "Altium Limited"))
      (libsource (lib "SCH") (part "Cap"))
    )
    (comp (ref "C77")
      (value "Cap")
      (footprint "Buck:C0805")
      (description "Capacitor")
      (fields (field (name "ALTIUM_VALUE") "10nF-16V") (field (name "PUBLISHER") "Altium Limited"))
      (libsource (lib "SCH") (part "Cap"))
    )
    (comp (ref "C78")
      (value "Cap")
      (footprint "Buck:C0805")
      (description "Capacitor")
      (fields (field (name "ALTIUM_VALUE") "10uF-16V") (field (name "PUBLISHER") "Altium Limited"))
      (libsource (lib "SCH") (part "Cap"))
    )
    (comp (ref "C79")
      (value "C2012X5R1E105K125AA")
      (footprint "Buck:C0805")
      (description "Multilayer Ceramic Capacitors 1μF ±10% 25V X5R SMD 0805")
      (fields (field (name "VOLTAGE") "25V") (field (name "TOLERANCE") "10%"))
      (libsource (lib "Miscellaneous Devices") (part "b4654b650e69147ec39a6b967a45e02"))
    )
    (comp (ref "C80")
      (value "Cap Pol2")
      (footprint "Buck:C0805")
      (description "Polarized Capacitor (Axial)")
      (fields (field (name "ALTIUM_VALUE") "10uF") (field (name "PUBLISHER") "Altium Limited"))
      (libsource (lib "SCH") (part "Cap Pol2"))
    )
    (comp (ref "C81") (value "1nF-50V") (footprint "Buck:C0805") (libsource (lib "") (part "CapSMD_1")))
    (comp (ref "C82")
      (value "Cap Pol2")
      (footprint "Buck:C0805")
      (description "Polarized Capacitor (Axial)")
      (fields (field (name "ALTIUM_VALUE") "10uF") (field (name "PUBLISHER") "Altium Limited"))
      (libsource (lib "SCH") (part "Cap Pol2"))
    )
    (comp (ref "C83")
      (value "100nF")
      (footprint "Buck:C0805")
      (description "None polar capacitor")
      (libsource (lib "Mylib") (part "Cap ceramic"))
    )
    (comp (ref "C84")
      (value "100pF")
      (footprint "Buck:C0805")
      (description "None polar capacitor")
      (libsource (lib "Mylib") (part "Cap ceramic"))
    )
    (comp (ref "C85")
      (value "100nF")
      (footprint "Buck:C0805")
      (description "None polar capacitor")
      (libsource (lib "Mylib") (part "Cap ceramic"))
    )
    (comp (ref "C86") (value "1nF-50V") (footprint "Buck:C0805") (libsource (lib "") (part "CapSMD_1")))
    (comp (ref "C87")
      (value "100pF")
      (footprint "Buck:C0805")
      (description "None polar capacitor")
      (libsource (lib "Mylib") (part "Cap ceramic"))
    )
    (comp (ref "C88")
      (value "100nF")
      (footprint "Buck:C0805")
      (description "None polar capacitor")
      (libsource (lib "Mylib") (part "Cap ceramic"))
    )
    (comp (ref "CR1")
      (value "SMBJ48A")
      (footprint "Buck:SMB (DO-214AA)")
      (libsource (lib "MYLIB") (part "DiodeSMD4.5mm"))
    )
    (comp (ref "CR2")
      (value "SMBJ48A")
      (footprint "Buck:SMB (DO-214AA)")
      (libsource (lib "MYLIB") (part "DiodeSMD4.5mm"))
    )
    (comp (ref "CR3")
      (value "SMBJ48A")
      (footprint "Buck:SMB (DO-214AA)")
      (libsource (lib "MYLIB") (part "DiodeSMD4.5mm"))
    )
    (comp (ref "CR4")
      (value "SMBJ48A")
      (footprint "Buck:SMB (DO-214AA)")
      (libsource (lib "MYLIB") (part "DiodeSMD4.5mm"))
    )
    (comp (ref "CR5")
      (value "SMBJ48A")
      (footprint "Buck:SMB (DO-214AA)")
      (libsource (lib "MYLIB") (part "DiodeSMD4.5mm"))
    )
    (comp (ref "CR6")
      (value "SMBJ48A")
      (footprint "Buck:SMB (DO-214AA)")
      (libsource (lib "MYLIB") (part "DiodeSMD4.5mm"))
    )
    (comp (ref "CR7")
      (value "SMBJ48A")
      (footprint "Buck:SMB (DO-214AA)")
      (libsource (lib "MYLIB") (part "DiodeSMD4.5mm"))
    )
    (comp (ref "CR8")
      (value "SMBJ48A")
      (footprint "Buck:SMB (DO-214AA)")
      (libsource (lib "MYLIB") (part "DiodeSMD4.5mm"))
    )
    (comp (ref "CR9")
      (value "SMBJ48A")
      (footprint "Buck:SMB (DO-214AA)")
      (libsource (lib "MYLIB") (part "DiodeSMD4.5mm"))
    )
    (comp (ref "CR10")
      (value "SMBJ48A")
      (footprint "Buck:SMB (DO-214AA)")
      (libsource (lib "MYLIB") (part "DiodeSMD4.5mm"))
    )
    (comp (ref "CR11")
      (value "SMBJ48A")
      (footprint "Buck:SMB (DO-214AA)")
      (libsource (lib "MYLIB") (part "DiodeSMD4.5mm"))
    )
    (comp (ref "CR12")
      (value "SMBJ48A")
      (footprint "Buck:SMB (DO-214AA)")
      (libsource (lib "MYLIB") (part "DiodeSMD4.5mm"))
    )
    (comp (ref "CR13")
      (value "SMBJ48A")
      (footprint "Buck:SMB (DO-214AA)")
      (libsource (lib "MYLIB") (part "DiodeSMD4.5mm"))
    )
    (comp (ref "CR14")
      (value "SMBJ48A")
      (footprint "Buck:SMB (DO-214AA)")
      (libsource (lib "MYLIB") (part "DiodeSMD4.5mm"))
    )
    (comp (ref "CR15")
      (value "SMBJ48A")
      (footprint "Buck:SMB (DO-214AA)")
      (libsource (lib "MYLIB") (part "DiodeSMD4.5mm"))
    )
    (comp (ref "CR16")
      (value "SMBJ48A")
      (footprint "Buck:SMB (DO-214AA)")
      (libsource (lib "MYLIB") (part "DiodeSMD4.5mm"))
    )
    (comp (ref "CR17")
      (value "RFN10BM6STL")
      (footprint "Buck:RFN10BM")
      (libsource (lib "MYLIB") (part "DiodeSMD4.5mm"))
    )
    (comp (ref "CR18")
      (value "RFN10BM6STL")
      (footprint "Buck:RFN10BM")
      (libsource (lib "MYLIB") (part "DiodeSMD4.5mm"))
    )
    (comp (ref "D1")
      (value "KDZVTR39A")
      (footprint "Buck:SOD-123FL")
      (description "Zener Diode")
      (fields (field (name "PUBLISHER") "Altium Limited"))
      (libsource (lib "Miscellaneous Devices") (part "D Zener"))
    )
    (comp (ref "D2")
      (value "VSS8D5M12HM3/H")
      (footprint "Buck:DO-221AD")
      (description "Schottky Diode")
      (fields (field (name "PUBLISHER") "Altium Limited"))
      (libsource (lib "Miscellaneous Devices") (part "D Schottky"))
    )
    (comp (ref "D3")
      (value "1N4007-SMD")
      (footprint "Buck:SMA (DO-214AC)")
      (description "Diode Standard 1000V 1A Through Hole DO-204AL _DO-41_")
      (fields (field (name "MF") "ON Semiconductor") (field (name "MP") "1N4007"))
      (libsource (lib "Buck") (part "1N4007"))
    )
    (comp (ref "D4")
      (value "1N4007-SMD")
      (footprint "Buck:SMA (DO-214AC)")
      (description "Diode Standard 1000V 1A Through Hole DO-204AL _DO-41_")
      (fields (field (name "MF") "ON Semiconductor") (field (name "MP") "1N4007"))
      (libsource (lib "Buck") (part "1N4007"))
    )
    (comp (ref "D5")
      (value "1N4007-SMD")
      (footprint "Buck:SMA (DO-214AC)")
      (description "Diode Standard 1000V 1A Through Hole DO-204AL _DO-41_")
      (fields (field (name "MF") "ON Semiconductor") (field (name "MP") "1N4007"))
      (libsource (lib "Buck") (part "1N4007"))
    )
    (comp (ref "D6")
      (value "1N4007-SMD")
      (footprint "Buck:SMA (DO-214AC)")
      (description "Diode Standard 1000V 1A Through Hole DO-204AL _DO-41_")
      (fields (field (name "MF") "ON Semiconductor") (field (name "MP") "1N4007"))
      (libsource (lib "Buck") (part "1N4007"))
    )
    (comp (ref "D7")
      (value "KDZVTR39A")
      (footprint "Buck:SOD-123FL")
      (description "Zener Diode")
      (fields (field (name "PUBLISHER") "Altium Limited"))
      (libsource (lib "Miscellaneous Devices") (part "D Zener"))
    )
    (comp (ref "D8")
      (value "1N4007-SMD")
      (footprint "Buck:SMA (DO-214AC)")
      (description "Diode Standard 1000V 1A Through Hole DO-204AL _DO-41_")
      (fields (field (name "MF") "ON Semiconductor") (field (name "MP") "1N4007"))
      (libsource (lib "Buck") (part "1N4007"))
    )
    (comp (ref "D9")
      (value "KDZVTR39A")
      (footprint "Buck:SOD-123FL")
      (description "Zener Diode")
      (fields (field (name "PUBLISHER") "Altium Limited"))
      (libsource (lib "Miscellaneous Devices") (part "D Zener"))
    )
    (comp (ref "D10")
      (value "1N4007-SMD")
      (footprint "Buck:SMA (DO-214AC)")
      (description "Diode Standard 1000V 1A Through Hole DO-204AL _DO-41_")
      (fields (field (name "MF") "ON Semiconductor") (field (name "MP") "1N4007"))
      (libsource (lib "Buck") (part "1N4007"))
    )
    (comp (ref "D11")
      (value "1N4007-SMD")
      (footprint "Buck:SMA (DO-214AC)")
      (description "Diode Standard 1000V 1A Through Hole DO-204AL _DO-41_")
      (fields (field (name "MF") "ON Semiconductor") (field (name "MP") "1N4007"))
      (libsource (lib "Buck") (part "1N4007"))
    )
    (comp (ref "D12")
      (value "1N4007-SMD")
      (footprint "Buck:SMA (DO-214AC)")
      (description "Diode Standard 1000V 1A Through Hole DO-204AL _DO-41_")
      (fields (field (name "MF") "ON Semiconductor") (field (name "MP") "1N4007"))
      (libsource (lib "Buck") (part "1N4007"))
    )
    (comp (ref "D13")
      (value "1N4007-SMD")
      (footprint "Buck:SMA (DO-214AC)")
      (description "Diode Standard 1000V 1A Through Hole DO-204AL _DO-41_")
      (fields (field (name "MF") "ON Semiconductor") (field (name "MP") "1N4007"))
      (libsource (lib "Buck") (part "1N4007"))
    )
    (comp (ref "D14")
      (value "1N4007-SMD")
      (footprint "Buck:SMA (DO-214AC)")
      (description "Diode Standard 1000V 1A Through Hole DO-204AL _DO-41_")
      (fields (field (name "MF") "ON Semiconductor") (field (name "MP") "1N4007"))
      (libsource (lib "Buck") (part "1N4007"))
    )
    (comp (ref "D15")
      (value "1N4007-SMD")
      (footprint "Buck:SMA (DO-214AC)")
      (description "Diode Standard 1000V 1A Through Hole DO-204AL _DO-41_")
      (fields (field (name "MF") "ON Semiconductor") (field (name "MP") "1N4007"))
      (libsource (lib "Buck") (part "1N4007"))
    )
    (comp (ref "D16")
      (value "1N4007-SMD")
      (footprint "Buck:SMA (DO-214AC)")
      (description "Diode Standard 1000V 1A Through Hole DO-204AL _DO-41_")
      (fields (field (name "MF") "ON Semiconductor") (field (name "MP") "1N4007"))
      (libsource (lib "Buck") (part "1N4007"))
    )
    (comp (ref "D17")
      (value "KDZVTR39A")
      (footprint "Buck:SOD-123FL")
      (description "Zener Diode")
      (fields (field (name "PUBLISHER") "Altium Limited"))
      (libsource (lib "Miscellaneous Devices") (part "D Zener"))
    )
    (comp (ref "D18")
      (value "KDZVTR39A")
      (footprint "Buck:SOD-123FL")
      (description "Zener Diode")
      (fields (field (name "PUBLISHER") "Altium Limited"))
      (libsource (lib "Miscellaneous Devices") (part "D Zener"))
    )
    (comp (ref "D19")
      (value "1N4007-SMD")
      (footprint "Buck:SMA (DO-214AC)")
      (description "Diode Standard 1000V 1A Through Hole DO-204AL _DO-41_")
      (fields (field (name "MF") "ON Semiconductor") (field (name "MP") "1N4007"))
      (libsource (lib "Buck") (part "1N4007"))
    )
    (comp (ref "D20")
      (value "1N4007-SMD")
      (footprint "Buck:SMA (DO-214AC)")
      (description "Diode Standard 1000V 1A Through Hole DO-204AL _DO-41_")
      (fields (field (name "MF") "ON Semiconductor") (field (name "MP") "1N4007"))
      (libsource (lib "Buck") (part "1N4007"))
    )
    (comp (ref "D21")
      (value "1N4007-SMD")
      (footprint "Buck:SMA (DO-214AC)")
      (description "Diode Standard 1000V 1A Through Hole DO-204AL _DO-41_")
      (fields (field (name "MF") "ON Semiconductor") (field (name "MP") "1N4007"))
      (libsource (lib "Buck") (part "1N4007"))
    )
    (comp (ref "D22")
      (value "1N4007-SMD")
      (footprint "Buck:SMA (DO-214AC)")
      (description "Diode Standard 1000V 1A Through Hole DO-204AL _DO-41_")
      (fields (field (name "MF") "ON Semiconductor") (field (name "MP") "1N4007"))
      (libsource (lib "Buck") (part "1N4007"))
    )
    (comp (ref "DS1") (value "LED SMD") (footprint "Buck:LED0805") (libsource (lib "MYLIB") (part "LED SMD")))
    (comp (ref "DS2")
      (value "LED SMD")
      (footprint "Buck:LED0805")
      (description "Blue SURFACE MOUNT LED LAMP, -40 to +85 ,0805 SIZE")
      (fields (field (name "PART NUMBER") "QTLP630C-7"))
      (libsource (lib "kashizadeh_ali") (part "LED"))
    )
    (comp (ref "DS3")
      (value "LED SMD")
      (footprint "Buck:LED0805")
      (description "Blue SURFACE MOUNT LED LAMP, -40 to +85 ,0805 SIZE")
      (fields (field (name "PART NUMBER") "QTLP630C-7"))
      (libsource (lib "kashizadeh_ali") (part "LED"))
    )
    (comp (ref "DS4")
      (value "LED SMD")
      (footprint "Buck:LED0805")
      (description "Blue SURFACE MOUNT LED LAMP, -40 to +85 ,0805 SIZE")
      (fields (field (name "PART NUMBER") "QTLP630C-7"))
      (libsource (lib "kashizadeh_ali") (part "LED"))
    )
    (comp (ref "DS5")
      (value "LED SMD")
      (footprint "Buck:LED0805")
      (description "Blue SURFACE MOUNT LED LAMP, -40 to +85 ,0805 SIZE")
      (fields (field (name "PART NUMBER") "QTLP630C-7"))
      (libsource (lib "kashizadeh_ali") (part "LED"))
    )
    (comp (ref "DS6") (value "LED SMD") (footprint "Buck:LED0805") (libsource (lib "MYLIB") (part "LED SMD")))
    (comp (ref "DS7") (value "LED SMD") (footprint "Buck:LED0805") (libsource (lib "MYLIB") (part "LED SMD")))
    (comp (ref "DS8") (value "LED SMD") (footprint "Buck:LED0805") (libsource (lib "MYLIB") (part "LED SMD")))
    (comp (ref "DS9")
      (value "LED SMD")
      (footprint "Buck:LED0805")
      (description "Blue SURFACE MOUNT LED LAMP, -40 to +85 ,0805 SIZE")
      (fields (field (name "PART NUMBER") "QTLP630C-7"))
      (libsource (lib "kashizadeh_ali") (part "LED"))
    )
    (comp (ref "DS10") (value "LED") (footprint "Buck:LED0805") (libsource (lib "SCH") (part "LED")))
    (comp (ref "DS11")
      (value "LED SMD")
      (footprint "Buck:LED0805")
      (libsource (lib "MYLIB") (part "LED SMD"))
    )
    (comp (ref "DS12")
      (value "LED SMD")
      (footprint "Buck:LED0805")
      (description "Blue SURFACE MOUNT LED LAMP, -40 to +85 ,0805 SIZE")
      (fields (field (name "PART NUMBER") "QTLP630C-7"))
      (libsource (lib "kashizadeh_ali") (part "LED"))
    )
    (comp (ref "F1")
      (value "0031.8001 Fuse holder")
      (footprint "Buck:00318001")
      (description "Fuse")
      (fields (field (name "PUBLISHER") "Altium Limited"))
      (libsource (lib "Miscellaneous Devices") (part "Fuse 1"))
    )
    (comp (ref "F2")
      (value "0031.8001 Fuse holder")
      (footprint "Buck:00318001")
      (description "Fuse")
      (fields (field (name "PUBLISHER") "Altium Limited"))
      (libsource (lib "Miscellaneous Devices") (part "Fuse 1"))
    )
    (comp (ref "F3")
      (value "0031.8001 Fuse holder")
      (footprint "Buck:00318001")
      (description "Fuse")
      (fields (field (name "PUBLISHER") "Altium Limited"))
      (libsource (lib "Miscellaneous Devices") (part "Fuse 1"))
    )
    (comp (ref "F4")
      (value "0031.8001 Fuse holder")
      (footprint "Buck:00318001")
      (description "Fuse")
      (fields (field (name "PUBLISHER") "Altium Limited"))
      (libsource (lib "Miscellaneous Devices") (part "Fuse 1"))
    )
    (comp (ref "FB1")
      (value "FERRITE CHIP")
      (footprint "Buck:L0805")
      (libsource (lib "No_avaran") (part "FERRITE CHIP"))
    )
    (comp (ref "FB2")
      (value "FBMJ2125HS420-T")
      (footprint "Buck:L0805")
      (libsource (lib "No_avaran") (part "FERRITE CHIP"))
    )
    (comp (ref "FB3")
      (value "FERRITE CHIP")
      (footprint "Buck:L0805")
      (libsource (lib "No_avaran") (part "FERRITE CHIP"))
    )
    (comp (ref "FB4")
      (value "FERRITE CHIP")
      (footprint "Buck:L0805")
      (libsource (lib "No_avaran") (part "FERRITE CHIP"))
    )
    (comp (ref "FB5")
      (value "FERRITE CHIP")
      (footprint "Buck:L0805")
      (libsource (lib "No_avaran") (part "FERRITE CHIP"))
    )
    (comp (ref "FB6")
      (value "FERRITE CHIP")
      (footprint "Buck:L0805")
      (libsource (lib "No_avaran") (part "FERRITE CHIP"))
    )
    (comp (ref "FB7")
      (value "FERRITE CHIP")
      (footprint "Buck:L0805")
      (libsource (lib "No_avaran") (part "FERRITE CHIP"))
    )
    (comp (ref "FB8")
      (value "FERRITE CHIP")
      (footprint "Buck:L0805")
      (libsource (lib "No_avaran") (part "FERRITE CHIP"))
    )
    (comp (ref "FB9")
      (value "FERRITE CHIP")
      (footprint "Buck:L0805")
      (libsource (lib "No_avaran") (part "FERRITE CHIP"))
    )
    (comp (ref "FB10")
      (value "FERRITE CHIP")
      (footprint "Buck:L0805")
      (libsource (lib "No_avaran") (part "FERRITE CHIP"))
    )
    (comp (ref "FB11")
      (value "FERRITE CHIP")
      (footprint "Buck:L0805")
      (libsource (lib "No_avaran") (part "FERRITE CHIP"))
    )
    (comp (ref "FB12")
      (value "FBMJ2125HS420-T")
      (footprint "Buck:L0805")
      (libsource (lib "No_avaran") (part "FERRITE CHIP"))
    )
    (comp (ref "FB13")
      (value "FBMJ2125HS420-T")
      (footprint "Buck:L0805")
      (libsource (lib "No_avaran") (part "FERRITE CHIP"))
    )
    (comp (ref "J1")
      (value "691101710002")
      (footprint "Buck:691101710002")
      (description "WR-TBL Series 101 Horizontal Entry Modular, THT, pitch 5mm, 2p")
      (fields (field (name "MANUFACTURER") "Wurth Elektronik"))
      (libsource (lib "Altium_WR-TBL (rev22b)") (part "691101710002"))
    )
    (comp (ref "J2")
      (value "61802529221")
      (footprint "Buck:61802525123")
      (description "Male PCB Connector with Hex Screw WR-DSUB, Vertical, 25 pins")
      (fields (field (name "MANUFACTURER") "Wurth Elektronik") (field (name "PUBLISHER") "WurthElektronik"))
      (libsource (lib "Miscellaneous Connectors") (part "WE-CN-2S-2M-D25"))
    )
    (comp (ref "L1")
      (value "Inductor")
      (footprint "Buck:FullBridge_Inductor")
      (fields (field (name "ALTIUM_VALUE") "EPCOS ETD39 N87") (field (name "PUBLISHER") "Altium Limited"))
      (libsource (lib "Miscellaneous Devices") (part "Inductor"))
    )
    (comp (ref "P1")
      (value "280371-2")
      (footprint "Buck:TECO-280371-2_V")
      (fields (field (name "MANUFACTURER") "TE Connectivity"))
      (libsource (lib "Miscellaneous Devices") (part "CN-1P-M-R4"))
    )
    (comp (ref "P2")
      (value "691311400104")
      (footprint "Buck:691311400104")
      (description "Serie 3114 - 7.62mm Close Vertical PCB Header WR-TBL, 4 pin")
      (fields (field (name "MANUFACTURER") "Wurth Elektronik") (field (name "PUBLISHER") "WurthElektronik"))
      (libsource (lib "Miscellaneous Connectors") (part "WE-CN-1P-M-R4"))
    )
    (comp (ref "P3")
      (value "691311400104")
      (footprint "Buck:691311400104")
      (description "Serie 3114 - 7.62mm Close Vertical PCB Header WR-TBL, 4 pin")
      (fields (field (name "MANUFACTURER") "Wurth Elektronik") (field (name "PUBLISHER") "WurthElektronik"))
      (libsource (lib "") (part "WE-CN-1P-M-R4_1"))
    )
    (comp (ref "PS1")
      (value "REC5-2415SRWZ/H6/A")
      (footprint "Buck:REC52415SRWZH6A")
      (description "DC/DC-Converter, 2kV, 4kVDC & 6kVDC Isolation. Continuous Short Circuit Protection")
      (libsource (lib "REC5-2415SRWZ_H6_A") (part "REC5-2415SRWZ/H6/A"))
    )
    (comp (ref "PS2")
      (value "REC5-2415SRWZ/H6/A")
      (footprint "Buck:REC52415SRWZH6A")
      (description "DC/DC-Converter, 2kV, 4kVDC & 6kVDC Isolation. Continuous Short Circuit Protection")
      (libsource (lib "REC5-2415SRWZ_H6_A") (part "REC5-2415SRWZ/H6/A"))
    )
    (comp (ref "PS3")
      (value "REC5-2415SRWZ/H6/A")
      (footprint "Buck:REC52415SRWZH6A")
      (description "DC/DC-Converter, 2kV, 4kVDC & 6kVDC Isolation. Continuous Short Circuit Protection")
      (libsource (lib "REC5-2415SRWZ_H6_A") (part "REC5-2415SRWZ/H6/A"))
    )
    (comp (ref "PS4")
      (value "REC5-2415SRWZ/H6/A")
      (footprint "Buck:REC52415SRWZH6A")
      (description "DC/DC-Converter, 2kV, 4kVDC & 6kVDC Isolation. Continuous Short Circuit Protection")
      (libsource (lib "REC5-2415SRWZ_H6_A") (part "REC5-2415SRWZ/H6/A"))
    )
    (comp (ref "Q1")
      (value "IKW25N120CS7")
      (footprint "Buck:PG-TO247-3")
      (fields (field (name "MANUFACTURER") "Infineon") (field (name "PARTNUMBER") "IKW40N120H3"))
      (libsource (lib "Miscellaneous Devices") (part "INF-IXXXXXXX-PG-TO220_247-3_1"))
    )
    (comp (ref "Q2")
      (value "IKW25N120CS7")
      (footprint "Buck:PG-TO247-3")
      (fields (field (name "MANUFACTURER") "Infineon") (field (name "PARTNUMBER") "IKW40N120H3"))
      (libsource (lib "Miscellaneous Devices") (part "INF-IXXXXXXX-PG-TO220_247-3_1"))
    )
    (comp (ref "Q3")
      (value "IKW25N120CS7")
      (footprint "Buck:PG-TO247-3")
      (fields (field (name "MANUFACTURER") "Infineon") (field (name "PARTNUMBER") "IKW40N120H3"))
      (libsource (lib "Miscellaneous Devices") (part "INF-IXXXXXXX-PG-TO220_247-3_1"))
    )
    (comp (ref "Q4")
      (value "IKW25N120CS7")
      (footprint "Buck:PG-TO247-3")
      (fields (field (name "MANUFACTURER") "Infineon") (field (name "PARTNUMBER") "IKW40N120H3"))
      (libsource (lib "Miscellaneous Devices") (part "INF-IXXXXXXX-PG-TO220_247-3_1"))
    )
    (comp (ref "Q5")
      (value "ACPL-C87A-500E")
      (footprint "Buck:FP-SSO-8-MFG")
      (description "IC OPAMP ISOLATION 100KHZ 8SO")
      (libsource (lib "Miscellaneous Devices") (part "b42ed144594ce334135a4fb1ded0a30"))
    )
    (comp (ref "R1") (value "15K") (footprint "Buck:R0805") (libsource (lib "MYLIB") (part "ResSMD")))
    (comp (ref "R2") (value "ResSMD") (footprint "Buck:R0805") (libsource (lib "MYLIB") (part "ResSMD")))
    (comp (ref "R3")
      (value "Res3")
      (footprint "Buck:R0603")
      (description "Resistor")
      (fields (field (name "ALTIUM_VALUE") "0") (field (name "PUBLISHER") "Altium Limited"))
      (libsource (lib "Miscellaneous Devices") (part "Res3"))
    )
    (comp (ref "R4")
      (value "Res3")
      (footprint "Buck:R0603")
      (description "Resistor")
      (fields (field (name "ALTIUM_VALUE") "0") (field (name "PUBLISHER") "Altium Limited"))
      (libsource (lib "Miscellaneous Devices") (part "Res3"))
    )
    (comp (ref "R5") (value "300") (footprint "Buck:R0805") (libsource (lib "MYLIB") (part "ResSMD")))
    (comp (ref "R6")
      (value "Res3")
      (footprint "Buck:R0603")
      (description "Resistor")
      (fields (field (name "ALTIUM_VALUE") "0") (field (name "PUBLISHER") "Altium Limited"))
      (libsource (lib "Miscellaneous Devices") (part "Res3"))
    )
    (comp (ref "R7")
      (value "12")
      (footprint "Buck:MELF 0204")
      (description "Semiconductor Resistor")
      (fields (field (name "ALTIUM_VALUE") "CMA02040X1209GB300") (field (name "PUBLISHER") "Altium Limited"))
      (libsource (lib "Miscellaneous Devices") (part "Res Semi"))
    )
    (comp (ref "R8")
      (value "Res3")
      (footprint "Buck:R0603")
      (description "Resistor")
      (fields (field (name "ALTIUM_VALUE") "0") (field (name "PUBLISHER") "Altium Limited"))
      (libsource (lib "Miscellaneous Devices") (part "Res3"))
    )
    (comp (ref "R9")
      (value "12")
      (footprint "Buck:MELF 0204")
      (description "Semiconductor Resistor")
      (fields (field (name "ALTIUM_VALUE") "CMA02040X1209GB300") (field (name "PUBLISHER") "Altium Limited"))
      (libsource (lib "Miscellaneous Devices") (part "Res Semi"))
    )
    (comp (ref "R10") (value "1K") (footprint "Buck:R0805") (libsource (lib "MYLIB") (part "ResSMD")))
    (comp (ref "R11") (value "ResSMD") (footprint "Buck:R0805") (libsource (lib "MYLIB") (part "ResSMD")))
    (comp (ref "R12")
      (value "Res3")
      (footprint "Buck:R0603")
      (description "Resistor")
      (fields (field (name "ALTIUM_VALUE") "0") (field (name "PUBLISHER") "Altium Limited"))
      (libsource (lib "Miscellaneous Devices") (part "Res3"))
    )
    (comp (ref "R13")
      (value "CMA02040X1209GB300")
      (footprint "Buck:MMF50S")
      (description "Resistor")
      (fields (field (name "ALTIUM_VALUE") "1") (field (name "PUBLISHER") "Altium Limited"))
      (libsource (lib "Miscellaneous Devices") (part "Res1"))
    )
    (comp (ref "R14") (value "ResSMD") (footprint "Buck:R0805") (libsource (lib "MYLIB") (part "ResSMD")))
    (comp (ref "R15") (value "ResSMD") (footprint "Buck:R0805") (libsource (lib "MYLIB") (part "ResSMD")))
    (comp (ref "R16")
      (value "Res3")
      (footprint "Buck:R0603")
      (description "Resistor")
      (fields (field (name "ALTIUM_VALUE") "0") (field (name "PUBLISHER") "Altium Limited"))
      (libsource (lib "Miscellaneous Devices") (part "Res3"))
    )
    (comp (ref "R17") (value "0") (footprint "Buck:R0805") (libsource (lib "MYLIB") (part "ResSMD")))
    (comp (ref "R18")
      (value "Res1")
      (footprint "Buck:R0805")
      (description "Resistor")
      (fields (field (name "ALTIUM_VALUE") "1") (field (name "PUBLISHER") "Altium Limited"))
      (libsource (lib "Miscellaneous Devices") (part "Res1"))
    )
    (comp (ref "R19")
      (value "Res1")
      (footprint "Buck:R0805")
      (description "Resistor")
      (fields (field (name "ALTIUM_VALUE") "1") (field (name "PUBLISHER") "Altium Limited"))
      (libsource (lib "Miscellaneous Devices") (part "Res1"))
    )
    (comp (ref "R20")
      (value "Res3")
      (footprint "Buck:R0603")
      (description "Resistor")
      (fields (field (name "ALTIUM_VALUE") "0") (field (name "PUBLISHER") "Altium Limited"))
      (libsource (lib "Miscellaneous Devices") (part "Res3"))
    )
    (comp (ref "R21")
      (value "Res3")
      (footprint "Buck:R0603")
      (description "Resistor")
      (fields (field (name "ALTIUM_VALUE") "0") (field (name "PUBLISHER") "Altium Limited"))
      (libsource (lib "Miscellaneous Devices") (part "Res3"))
    )
    (comp (ref "R22")
      (value "CMA02040X1209GB300")
      (footprint "Buck:MMF50S")
      (description "Resistor")
      (fields (field (name "ALTIUM_VALUE") "1") (field (name "PUBLISHER") "Altium Limited"))
      (libsource (lib "Miscellaneous Devices") (part "Res1"))
    )
    (comp (ref "R23") (value "5K") (footprint "Buck:R0805") (libsource (lib "MYLIB") (part "ResSMD")))
    (comp (ref "R24") (value "ResSMD") (footprint "Buck:R0805") (libsource (lib "MYLIB") (part "ResSMD")))
    (comp (ref "R25")
      (value "Res3")
      (footprint "Buck:R0603")
      (description "Resistor")
      (fields (field (name "ALTIUM_VALUE") "10K") (field (name "PUBLISHER") "Altium Limited"))
      (libsource (lib "Miscellaneous Devices") (part "Res3"))
    )
    (comp (ref "R26") (value "5K") (footprint "Buck:R0805") (libsource (lib "MYLIB") (part "ResSMD")))
    (comp (ref "R27") (value "5K") (footprint "Buck:R0805") (libsource (lib "MYLIB") (part "ResSMD")))
    (comp (ref "R28") (value "1K") (footprint "Buck:R0805") (libsource (lib "MYLIB") (part "ResSMD")))
    (comp (ref "R29")
      (value "Res3")
      (footprint "Buck:R0603")
      (description "Resistor")
      (fields (field (name "ALTIUM_VALUE") "10K") (field (name "PUBLISHER") "Altium Limited"))
      (libsource (lib "Miscellaneous Devices") (part "Res3"))
    )
    (comp (ref "R30")
      (value "47k")
      (footprint "Buck:R0805")
      (description "Resistor")
      (fields (field (name "ALTIUM_VALUE") "47k") (field (name "PUBLISHER") "Altium Limited"))
      (libsource (lib "Miscellaneous Devices") (part "Res1"))
    )
    (comp (ref "R31")
      (value "15")
      (footprint "Buck:AXIAL-0.5")
      (description "Semiconductor Resistor")
      (fields (field (name "ALTIUM_VALUE") "0.5W") (field (name "PUBLISHER") "Altium Limited"))
      (libsource (lib "Miscellaneous Devices") (part "Res Semi"))
    )
    (comp (ref "R32")
      (value "15")
      (footprint "Buck:AXIAL-0.5")
      (description "Semiconductor Resistor")
      (fields (field (name "ALTIUM_VALUE") "0.5W") (field (name "PUBLISHER") "Altium Limited"))
      (libsource (lib "Miscellaneous Devices") (part "Res Semi"))
    )
    (comp (ref "R33") (value "100") (footprint "Buck:R0805") (libsource (lib "MYLIB") (part "ResSMD")))
    (comp (ref "R34") (value "100") (footprint "Buck:R0805") (libsource (lib "MYLIB") (part "ResSMD")))
    (comp (ref "R35")
      (value "CMA02040X1209GB300")
      (footprint "Buck:MMF50S")
      (description "Resistor")
      (fields (field (name "ALTIUM_VALUE") "???") (field (name "PUBLISHER") "Altium Limited"))
      (libsource (lib "Miscellaneous Devices") (part "Res1"))
    )
    (comp (ref "R36")
      (value "CMA02040X1209GB300")
      (footprint "Buck:MMF50S")
      (description "Resistor")
      (fields (field (name "ALTIUM_VALUE") "???") (field (name "PUBLISHER") "Altium Limited"))
      (libsource (lib "Miscellaneous Devices") (part "Res1"))
    )
    (comp (ref "R37")
      (value "12")
      (footprint "Buck:MELF 0204")
      (description "Semiconductor Resistor")
      (fields (field (name "ALTIUM_VALUE") "CMA02040X1209GB300") (field (name "PUBLISHER") "Altium Limited"))
      (libsource (lib "Miscellaneous Devices") (part "Res Semi"))
    )
    (comp (ref "R38")
      (value "100k")
      (footprint "Buck:AXIAL0.9-VR68")
      (description "Semiconductor Resistor")
      (fields (field (name "ALTIUM_VALUE") "0.5W") (field (name "PUBLISHER") "Altium Limited"))
      (libsource (lib "Miscellaneous Devices") (part "Res Semi"))
    )
    (comp (ref "R39")
      (value "100k")
      (footprint "Buck:AXIAL0.9-VR68")
      (description "Semiconductor Resistor")
      (fields (field (name "ALTIUM_VALUE") "0.5W") (field (name "PUBLISHER") "Altium Limited"))
      (libsource (lib "Miscellaneous Devices") (part "Res Semi"))
    )
    (comp (ref "R40")
      (value "Res3")
      (footprint "Buck:R0603")
      (description "Resistor")
      (fields (field (name "ALTIUM_VALUE") "0") (field (name "PUBLISHER") "Altium Limited"))
      (libsource (lib "Miscellaneous Devices") (part "Res3"))
    )
    (comp (ref "R41")
      (value "12")
      (footprint "Buck:MELF 0204")
      (description "Semiconductor Resistor")
      (fields (field (name "ALTIUM_VALUE") "CMA02040X1209GB300") (field (name "PUBLISHER") "Altium Limited"))
      (libsource (lib "Miscellaneous Devices") (part "Res Semi"))
    )
    (comp (ref "R42")
      (value "100k")
      (footprint "Buck:AXIAL0.9-VR68")
      (description "Semiconductor Resistor")
      (fields (field (name "ALTIUM_VALUE") "0.5W") (field (name "PUBLISHER") "Altium Limited"))
      (libsource (lib "Miscellaneous Devices") (part "Res Semi"))
    )
    (comp (ref "R43")
      (value "100k")
      (footprint "Buck:AXIAL0.9-VR68")
      (description "Semiconductor Resistor")
      (fields (field (name "ALTIUM_VALUE") "0.5W") (field (name "PUBLISHER") "Altium Limited"))
      (libsource (lib "Miscellaneous Devices") (part "Res Semi"))
    )
    (comp (ref "R44") (value "ResSMD") (footprint "Buck:R0805") (libsource (lib "MYLIB") (part "ResSMD")))
    (comp (ref "R45")
      (value "Res3")
      (footprint "Buck:R0603")
      (description "Resistor")
      (fields (field (name "ALTIUM_VALUE") "0") (field (name "PUBLISHER") "Altium Limited"))
      (libsource (lib "Miscellaneous Devices") (part "Res3"))
    )
    (comp (ref "R46")
      (value "CMA02040X1209GB300")
      (footprint "Buck:MMF50S")
      (description "Resistor")
      (fields (field (name "ALTIUM_VALUE") "1") (field (name "PUBLISHER") "Altium Limited"))
      (libsource (lib "Miscellaneous Devices") (part "Res1"))
    )
    (comp (ref "R47")
      (value "Res3")
      (footprint "Buck:R0603")
      (description "Resistor")
      (fields (field (name "ALTIUM_VALUE") "0") (field (name "PUBLISHER") "Altium Limited"))
      (libsource (lib "Miscellaneous Devices") (part "Res3"))
    )
    (comp (ref "R48") (value "0") (footprint "Buck:R0805") (libsource (lib "MYLIB") (part "ResSMD")))
    (comp (ref "R49")
      (value "Res1")
      (footprint "Buck:R0805")
      (description "Resistor")
      (fields (field (name "ALTIUM_VALUE") "1") (field (name "PUBLISHER") "Altium Limited"))
      (libsource (lib "Miscellaneous Devices") (part "Res1"))
    )
    (comp (ref "R50")
      (value "Res1")
      (footprint "Buck:R0805")
      (description "Resistor")
      (fields (field (name "ALTIUM_VALUE") "1") (field (name "PUBLISHER") "Altium Limited"))
      (libsource (lib "Miscellaneous Devices") (part "Res1"))
    )
    (comp (ref "R51")
      (value "Res3")
      (footprint "Buck:R0603")
      (description "Resistor")
      (fields (field (name "ALTIUM_VALUE") "0") (field (name "PUBLISHER") "Altium Limited"))
      (libsource (lib "Miscellaneous Devices") (part "Res3"))
    )
    (comp (ref "R52")
      (value "15")
      (footprint "Buck:AXIAL-0.5")
      (description "Semiconductor Resistor")
      (fields (field (name "ALTIUM_VALUE") "0.5W") (field (name "PUBLISHER") "Altium Limited"))
      (libsource (lib "Miscellaneous Devices") (part "Res Semi"))
    )
    (comp (ref "R53")
      (value "Res3")
      (footprint "Buck:R0603")
      (description "Resistor")
      (fields (field (name "ALTIUM_VALUE") "0") (field (name "PUBLISHER") "Altium Limited"))
      (libsource (lib "Miscellaneous Devices") (part "Res3"))
    )
    (comp (ref "R54")
      (value "15")
      (footprint "Buck:AXIAL-0.5")
      (description "Semiconductor Resistor")
      (fields (field (name "ALTIUM_VALUE") "0.5W") (field (name "PUBLISHER") "Altium Limited"))
      (libsource (lib "Miscellaneous Devices") (part "Res Semi"))
    )
    (comp (ref "R55")
      (value "CMA02040X1209GB300")
      (footprint "Buck:MMF50S")
      (description "Resistor")
      (fields (field (name "ALTIUM_VALUE") "1") (field (name "PUBLISHER") "Altium Limited"))
      (libsource (lib "Miscellaneous Devices") (part "Res1"))
    )
    (comp (ref "R56") (value "5K") (footprint "Buck:R0805") (libsource (lib "MYLIB") (part "ResSMD")))
    (comp (ref "R57") (value "100") (footprint "Buck:R0805") (libsource (lib "MYLIB") (part "ResSMD")))
    (comp (ref "R58") (value "100") (footprint "Buck:R0805") (libsource (lib "MYLIB") (part "ResSMD")))
    (comp (ref "R59")
      (value "Res3")
      (footprint "Buck:R0603")
      (description "Resistor")
      (fields (field (name "ALTIUM_VALUE") "10K") (field (name "PUBLISHER") "Altium Limited"))
      (libsource (lib "Miscellaneous Devices") (part "Res3"))
    )
    (comp (ref "R60") (value "5K") (footprint "Buck:R0805") (libsource (lib "MYLIB") (part "ResSMD")))
    (comp (ref "R61") (value "5K") (footprint "Buck:R0805") (libsource (lib "MYLIB") (part "ResSMD")))
    (comp (ref "R62") (value "1K") (footprint "Buck:R0805") (libsource (lib "MYLIB") (part "ResSMD")))
    (comp (ref "R63")
      (value "Res3")
      (footprint "Buck:R0603")
      (description "Resistor")
      (fields (field (name "ALTIUM_VALUE") "10K") (field (name "PUBLISHER") "Altium Limited"))
      (libsource (lib "Miscellaneous Devices") (part "Res3"))
    )
    (comp (ref "R64")
      (value "47k")
      (footprint "Buck:R0805")
      (description "Resistor")
      (fields (field (name "ALTIUM_VALUE") "47k") (field (name "PUBLISHER") "Altium Limited"))
      (libsource (lib "Miscellaneous Devices") (part "Res1"))
    )
    (comp (ref "R65")
      (value "CMA02040X1209GB300")
      (footprint "Buck:MMF50S")
      (description "Resistor")
      (fields (field (name "ALTIUM_VALUE") "???") (field (name "PUBLISHER") "Altium Limited"))
      (libsource (lib "Miscellaneous Devices") (part "Res1"))
    )
    (comp (ref "R66")
      (value "CMA02040X1209GB300")
      (footprint "Buck:MMF50S")
      (description "Resistor")
      (fields (field (name "ALTIUM_VALUE") "???") (field (name "PUBLISHER") "Altium Limited"))
      (libsource (lib "Miscellaneous Devices") (part "Res1"))
    )
    (comp (ref "R67")
      (value "12")
      (footprint "Buck:MELF 0204")
      (description "Semiconductor Resistor")
      (fields (field (name "ALTIUM_VALUE") "CMA02040X1209GB300") (field (name "PUBLISHER") "Altium Limited"))
      (libsource (lib "Miscellaneous Devices") (part "Res Semi"))
    )
    (comp (ref "R68")
      (value "Res3")
      (footprint "Buck:R0603")
      (description "Resistor")
      (fields (field (name "ALTIUM_VALUE") "0") (field (name "PUBLISHER") "Altium Limited"))
      (libsource (lib "Miscellaneous Devices") (part "Res3"))
    )
    (comp (ref "R69")
      (value "12")
      (footprint "Buck:MELF 0204")
      (description "Semiconductor Resistor")
      (fields (field (name "ALTIUM_VALUE") "CMA02040X1209GB300") (field (name "PUBLISHER") "Altium Limited"))
      (libsource (lib "Miscellaneous Devices") (part "Res Semi"))
    )
    (comp (ref "R70") (value "ResSMD") (footprint "Buck:R0805") (libsource (lib "MYLIB") (part "ResSMD")))
    (comp (ref "R71")
      (value "Res3")
      (footprint "Buck:R0603")
      (description "Resistor")
      (fields (field (name "ALTIUM_VALUE") "0") (field (name "PUBLISHER") "Altium Limited"))
      (libsource (lib "Miscellaneous Devices") (part "Res3"))
    )
    (comp (ref "R72")
      (value "CMA02040X1209GB300")
      (footprint "Buck:MMF50S")
      (description "Resistor")
      (fields (field (name "ALTIUM_VALUE") "1") (field (name "PUBLISHER") "Altium Limited"))
      (libsource (lib "Miscellaneous Devices") (part "Res1"))
    )
    (comp (ref "R73")
      (value "Res3")
      (footprint "Buck:R0603")
      (description "Resistor")
      (fields (field (name "ALTIUM_VALUE") "0") (field (name "PUBLISHER") "Altium Limited"))
      (libsource (lib "Miscellaneous Devices") (part "Res3"))
    )
    (comp (ref "R74") (value "0") (footprint "Buck:R0805") (libsource (lib "MYLIB") (part "ResSMD")))
    (comp (ref "R75")
      (value "Res1")
      (footprint "Buck:R0805")
      (description "Resistor")
      (fields (field (name "ALTIUM_VALUE") "1") (field (name "PUBLISHER") "Altium Limited"))
      (libsource (lib "Miscellaneous Devices") (part "Res1"))
    )
    (comp (ref "R76")
      (value "Res1")
      (footprint "Buck:R0805")
      (description "Resistor")
      (fields (field (name "ALTIUM_VALUE") "1") (field (name "PUBLISHER") "Altium Limited"))
      (libsource (lib "Miscellaneous Devices") (part "Res1"))
    )
    (comp (ref "R77")
      (value "Res3")
      (footprint "Buck:R0603")
      (description "Resistor")
      (fields (field (name "ALTIUM_VALUE") "0") (field (name "PUBLISHER") "Altium Limited"))
      (libsource (lib "Miscellaneous Devices") (part "Res3"))
    )
    (comp (ref "R78")
      (value "Res3")
      (footprint "Buck:R0603")
      (description "Resistor")
      (fields (field (name "ALTIUM_VALUE") "0") (field (name "PUBLISHER") "Altium Limited"))
      (libsource (lib "Miscellaneous Devices") (part "Res3"))
    )
    (comp (ref "R79")
      (value "CMA02040X1209GB300")
      (footprint "Buck:MMF50S")
      (description "Resistor")
      (fields (field (name "ALTIUM_VALUE") "1") (field (name "PUBLISHER") "Altium Limited"))
      (libsource (lib "Miscellaneous Devices") (part "Res1"))
    )
    (comp (ref "R80") (value "5K") (footprint "Buck:R0805") (libsource (lib "MYLIB") (part "ResSMD")))
    (comp (ref "R81")
      (value "Res3")
      (footprint "Buck:R0603")
      (description "Resistor")
      (fields (field (name "ALTIUM_VALUE") "10K") (field (name "PUBLISHER") "Altium Limited"))
      (libsource (lib "Miscellaneous Devices") (part "Res3"))
    )
    (comp (ref "R82") (value "5K") (footprint "Buck:R0805") (libsource (lib "MYLIB") (part "ResSMD")))
    (comp (ref "R83") (value "5K") (footprint "Buck:R0805") (libsource (lib "MYLIB") (part "ResSMD")))
    (comp (ref "R84") (value "1K") (footprint "Buck:R0805") (libsource (lib "MYLIB") (part "ResSMD")))
    (comp (ref "R85")
      (value "Res3")
      (footprint "Buck:R0603")
      (description "Resistor")
      (fields (field (name "ALTIUM_VALUE") "10K") (field (name "PUBLISHER") "Altium Limited"))
      (libsource (lib "Miscellaneous Devices") (part "Res3"))
    )
    (comp (ref "R86")
      (value "47k")
      (footprint "Buck:R0805")
      (description "Resistor")
      (fields (field (name "ALTIUM_VALUE") "47k") (field (name "PUBLISHER") "Altium Limited"))
      (libsource (lib "Miscellaneous Devices") (part "Res1"))
    )
    (comp (ref "R87") (value "15K") (footprint "Buck:R0805") (libsource (lib "MYLIB") (part "ResSMD")))
    (comp (ref "R88") (value "15K") (footprint "Buck:R0805") (libsource (lib "MYLIB") (part "ResSMD")))
    (comp (ref "R89")
      (value "12")
      (footprint "Buck:MELF 0204")
      (description "Semiconductor Resistor")
      (fields (field (name "ALTIUM_VALUE") "CMA02040X1209GB300") (field (name "PUBLISHER") "Altium Limited"))
      (libsource (lib "Miscellaneous Devices") (part "Res Semi"))
    )
    (comp (ref "R90")
      (value "Res3")
      (footprint "Buck:R0603")
      (description "Resistor")
      (fields (field (name "ALTIUM_VALUE") "0") (field (name "PUBLISHER") "Altium Limited"))
      (libsource (lib "Miscellaneous Devices") (part "Res3"))
    )
    (comp (ref "R91")
      (value "12")
      (footprint "Buck:MELF 0204")
      (description "Semiconductor Resistor")
      (fields (field (name "ALTIUM_VALUE") "CMA02040X1209GB300") (field (name "PUBLISHER") "Altium Limited"))
      (libsource (lib "Miscellaneous Devices") (part "Res Semi"))
    )
    (comp (ref "R92") (value "0Ohm 805") (footprint "Buck:R0805") (libsource (lib "MYLIB") (part "ResSMD")))
    (comp (ref "R93") (value "0Ohm 805") (footprint "Buck:R0805") (libsource (lib "MYLIB") (part "ResSMD")))
    (comp (ref "R94") (value "15K") (footprint "Buck:R0805") (libsource (lib "MYLIB") (part "ResSMD")))
    (comp (ref "R95") (value "ResSMD") (footprint "Buck:R0805") (libsource (lib "MYLIB") (part "ResSMD")))
    (comp (ref "R96")
      (value "Res3")
      (footprint "Buck:R0603")
      (description "Resistor")
      (fields (field (name "ALTIUM_VALUE") "0") (field (name "PUBLISHER") "Altium Limited"))
      (libsource (lib "Miscellaneous Devices") (part "Res3"))
    )
    (comp (ref "R97")
      (value "CMA02040X1209GB300")
      (footprint "Buck:MMF50S")
      (description "Resistor")
      (fields (field (name "ALTIUM_VALUE") "1") (field (name "PUBLISHER") "Altium Limited"))
      (libsource (lib "Miscellaneous Devices") (part "Res1"))
    )
    (comp (ref "R98") (value "10K") (footprint "Buck:R0805") (libsource (lib "MYLIB") (part "ResSMD")))
    (comp (ref "R99") (value "10K") (footprint "Buck:R0805") (libsource (lib "MYLIB") (part "ResSMD")))
    (comp (ref "R100") (value "10K") (footprint "Buck:R0805") (libsource (lib "MYLIB") (part "ResSMD")))
    (comp (ref "R101") (value "10K") (footprint "Buck:R0805") (libsource (lib "MYLIB") (part "ResSMD")))
    (comp (ref "R102") (value "10K") (footprint "Buck:R0805") (libsource (lib "MYLIB") (part "ResSMD")))
    (comp (ref "R103") (value "10K") (footprint "Buck:R0805") (libsource (lib "MYLIB") (part "ResSMD")))
    (comp (ref "R104") (value "10K") (footprint "Buck:R0805") (libsource (lib "MYLIB") (part "ResSMD")))
    (comp (ref "R105") (value "10K") (footprint "Buck:R0805") (libsource (lib "MYLIB") (part "ResSMD")))
    (comp (ref "R106")
      (value "Res3")
      (footprint "Buck:R0603")
      (description "Resistor")
      (fields (field (name "ALTIUM_VALUE") "0") (field (name "PUBLISHER") "Altium Limited"))
      (libsource (lib "Miscellaneous Devices") (part "Res3"))
    )
    (comp (ref "R107") (value "0") (footprint "Buck:R0805") (libsource (lib "MYLIB") (part "ResSMD")))
    (comp (ref "R108")
      (value "Res1")
      (footprint "Buck:R0805")
      (description "Resistor")
      (fields (field (name "ALTIUM_VALUE") "1") (field (name "PUBLISHER") "Altium Limited"))
      (libsource (lib "Miscellaneous Devices") (part "Res1"))
    )
    (comp (ref "R109")
      (value "Res1")
      (footprint "Buck:R0805")
      (description "Resistor")
      (fields (field (name "ALTIUM_VALUE") "1") (field (name "PUBLISHER") "Altium Limited"))
      (libsource (lib "Miscellaneous Devices") (part "Res1"))
    )
    (comp (ref "R110")
      (value "Res3")
      (footprint "Buck:R0603")
      (description "Resistor")
      (fields (field (name "ALTIUM_VALUE") "0") (field (name "PUBLISHER") "Altium Limited"))
      (libsource (lib "Miscellaneous Devices") (part "Res3"))
    )
    (comp (ref "R111")
      (value "Res3")
      (footprint "Buck:R0603")
      (description "Resistor")
      (fields (field (name "ALTIUM_VALUE") "0") (field (name "PUBLISHER") "Altium Limited"))
      (libsource (lib "Miscellaneous Devices") (part "Res3"))
    )
    (comp (ref "R112")
      (value "CMA02040X1209GB300")
      (footprint "Buck:MMF50S")
      (description "Resistor")
      (fields (field (name "ALTIUM_VALUE") "1") (field (name "PUBLISHER") "Altium Limited"))
      (libsource (lib "Miscellaneous Devices") (part "Res1"))
    )
    (comp (ref "R113") (value "5K") (footprint "Buck:R0805") (libsource (lib "MYLIB") (part "ResSMD")))
    (comp (ref "R114")
      (value "Res3")
      (footprint "Buck:R0603")
      (description "Resistor")
      (fields (field (name "ALTIUM_VALUE") "10K") (field (name "PUBLISHER") "Altium Limited"))
      (libsource (lib "Miscellaneous Devices") (part "Res3"))
    )
    (comp (ref "R115") (value "5K") (footprint "Buck:R0805") (libsource (lib "MYLIB") (part "ResSMD")))
    (comp (ref "R116") (value "5K") (footprint "Buck:R0805") (libsource (lib "MYLIB") (part "ResSMD")))
    (comp (ref "R117") (value "1K") (footprint "Buck:R0805") (libsource (lib "MYLIB") (part "ResSMD")))
    (comp (ref "R118")
      (value "Res3")
      (footprint "Buck:R0603")
      (description "Resistor")
      (fields (field (name "ALTIUM_VALUE") "10K") (field (name "PUBLISHER") "Altium Limited"))
      (libsource (lib "Miscellaneous Devices") (part "Res3"))
    )
    (comp (ref "R119") (value "15K") (footprint "Buck:R0805") (libsource (lib "MYLIB") (part "ResSMD")))
    (comp (ref "R120")
      (value "47k")
      (footprint "Buck:R0805")
      (description "Resistor")
      (fields (field (name "ALTIUM_VALUE") "47k") (field (name "PUBLISHER") "Altium Limited"))
      (libsource (lib "Miscellaneous Devices") (part "Res1"))
    )
    (comp (ref "R121")
      (value "1K")
      (footprint "Buck:R0805")
      (description "resistor 1/4 wat")
      (libsource (lib "Mylib") (part "Res"))
    )
    (comp (ref "R122") (value "1K") (footprint "Buck:R0805") (libsource (lib "MYLIB") (part "ResSMD")))
    (comp (ref "R123")
      (value "Res3")
      (footprint "Buck:R0603")
      (description "Resistor")
      (fields (field (name "ALTIUM_VALUE") "0") (field (name "PUBLISHER") "Altium Limited"))
      (libsource (lib "Miscellaneous Devices") (part "Res3"))
    )
    (comp (ref "R124")
      (value "Res3")
      (footprint "Buck:R0603")
      (description "Resistor")
      (fields (field (name "ALTIUM_VALUE") "0") (field (name "PUBLISHER") "Altium Limited"))
      (libsource (lib "Miscellaneous Devices") (part "Res3"))
    )
    (comp (ref "R125")
      (value "MOVS2825V420")
      (footprint "Buck:MOVS2825V420")
      (description "Varistor (Voltage-Sensitive Resistor)")
      (fields (field (name "PUBLISHER") "Altium Limited"))
      (libsource (lib "Miscellaneous Devices") (part "Res Varistor"))
    )
    (comp (ref "R126")
      (value "0")
      (footprint "Buck:R0603")
      (description "RES Thick Film, 2kΩ, 1%, 0.25W, 100ppm/°C, 1206")
      (fields (field (name "TOLERANCE") "1%"))
      (libsource (lib "Miscellaneous Devices") (part "1029c3af85768c4190bb7ad29bc67b5"))
    )
    (comp (ref "R127")
      (value "15k")
      (footprint "Buck:R0603")
      (description "RES Thick Film, 2kΩ, 1%, 0.25W, 100ppm/°C, 1206")
      (fields (field (name "TOLERANCE") "1%"))
      (libsource (lib "Miscellaneous Devices") (part "1029c3af85768c4190bb7ad29bc67b5"))
    )
    (comp (ref "R129")
      (value "4.7k")
      (footprint "Buck:R0805")
      (description "RES Thick Film, 2kΩ, 1%, 0.25W, 100ppm/°C, 1206")
      (fields (field (name "TOLERANCE") "1%"))
      (libsource (lib "Miscellaneous Devices") (part "1029c3af85768c4190bb7ad29bc67b5"))
    )
    (comp (ref "R130")
      (value "4.7k")
      (footprint "Buck:R0805")
      (description "RES Thick Film, 2kΩ, 1%, 0.25W, 100ppm/°C, 1206")
      (fields (field (name "TOLERANCE") "1%"))
      (libsource (lib "Miscellaneous Devices") (part "1029c3af85768c4190bb7ad29bc67b5"))
    )
    (comp (ref "R131") (value "100") (footprint "Buck:R0805") (libsource (lib "MYLIB") (part "ResSMD")))
    (comp (ref "R132")
      (value "4.7k")
      (footprint "Buck:R0805")
      (description "RES Thick Film, 2kΩ, 1%, 0.25W, 100ppm/°C, 1206")
      (fields (field (name "TOLERANCE") "1%"))
      (libsource (lib "Miscellaneous Devices") (part "1029c3af85768c4190bb7ad29bc67b5"))
    )
    (comp (ref "R133")
      (value "4.7k")
      (footprint "Buck:R0805")
      (description "RES Thick Film, 2kΩ, 1%, 0.25W, 100ppm/°C, 1206")
      (fields (field (name "TOLERANCE") "1%"))
      (libsource (lib "Miscellaneous Devices") (part "1029c3af85768c4190bb7ad29bc67b5"))
    )
    (comp (ref "R134") (value "0") (footprint "Buck:R0805") (libsource (lib "MYLIB") (part "ResSMD")))
    (comp (ref "R135") (value "0") (footprint "Buck:R0805") (libsource (lib "MYLIB") (part "ResSMD")))
    (comp (ref "R136")
      (value "Res1")
      (footprint "Buck:R0805")
      (description "Resistor")
      (fields (field (name "ALTIUM_VALUE") "15k") (field (name "PUBLISHER") "Altium Limited"))
      (libsource (lib "Miscellaneous Devices") (part "Res1"))
    )
    (comp (ref "R137") (value "1K") (footprint "Buck:R0805") (libsource (lib "MYLIB") (part "ResSMD")))
    (comp (ref "R138") (value "1K") (footprint "Buck:R0805") (libsource (lib "MYLIB") (part "ResSMD")))
    (comp (ref "R139") (value "1K") (footprint "Buck:R0805") (libsource (lib "MYLIB") (part "ResSMD")))
    (comp (ref "R140") (value "0 SMD") (footprint "Buck:R0805") (libsource (lib "MYLIB") (part "ResSMD")))
    (comp (ref "R141") (value "0 SMD") (footprint "Buck:R0805") (libsource (lib "MYLIB") (part "ResSMD")))
    (comp (ref "R142") (value "0 SMD") (footprint "Buck:R0805") (libsource (lib "MYLIB") (part "ResSMD")))
    (comp (ref "R143") (value "ResSMD") (footprint "Buck:R0805") (libsource (lib "MYLIB") (part "ResSMD")))
    (comp (ref "R144") (value "0 SMD") (footprint "Buck:R0805") (libsource (lib "MYLIB") (part "ResSMD")))
    (comp (ref "R145") (value "0 SMD") (footprint "Buck:R0805") (libsource (lib "MYLIB") (part "ResSMD")))
    (comp (ref "R146") (value "0 SMD") (footprint "Buck:R0805") (libsource (lib "MYLIB") (part "ResSMD")))
    (comp (ref "R147") (value "ResSMD") (footprint "Buck:R0805") (libsource (lib "MYLIB") (part "ResSMD")))
    (comp (ref "R148") (value "ResSMD") (footprint "Buck:R0805") (libsource (lib "MYLIB") (part "ResSMD")))
    (comp (ref "R149") (value "ResSMD") (footprint "Buck:R0805") (libsource (lib "MYLIB") (part "ResSMD")))
    (comp (ref "R150") (value "ResSMD") (footprint "Buck:R0805") (libsource (lib "MYLIB") (part "ResSMD")))
    (comp (ref "R151") (value "ResSMD") (footprint "Buck:R0805") (libsource (lib "MYLIB") (part "ResSMD")))
    (comp (ref "R152") (value "ResSMD") (footprint "Buck:R0805") (libsource (lib "MYLIB") (part "ResSMD")))
    (comp (ref "R153") (value "ResSMD") (footprint "Buck:R0805") (libsource (lib "MYLIB") (part "ResSMD")))
    (comp (ref "R154")
      (value "Res3")
      (footprint "Buck:R0603")
      (description "Resistor")
      (fields (field (name "ALTIUM_VALUE") "0") (field (name "PUBLISHER") "Altium Limited"))
      (libsource (lib "Miscellaneous Devices") (part "Res3"))
    )
    (comp (ref "R155") (value "ResSMD") (footprint "Buck:R0805") (libsource (lib "MYLIB") (part "ResSMD")))
    (comp (ref "R156") (value "ResSMD") (footprint "Buck:R0805") (libsource (lib "MYLIB") (part "ResSMD")))
    (comp (ref "R157") (value "ResSMD") (footprint "Buck:R0805") (libsource (lib "MYLIB") (part "ResSMD")))
    (comp (ref "R158") (value "ResSMD") (footprint "Buck:R0805") (libsource (lib "MYLIB") (part "ResSMD")))
    (comp (ref "R159") (value "ResSMD") (footprint "Buck:R0805") (libsource (lib "MYLIB") (part "ResSMD")))
    (comp (ref "R160") (value "0 SMD") (footprint "Buck:R0805") (libsource (lib "MYLIB") (part "ResSMD")))
    (comp (ref "R161") (value "ResSMD") (footprint "Buck:R0805") (libsource (lib "MYLIB") (part "ResSMD")))
    (comp (ref "R162")
      (value "Res3")
      (footprint "Buck:R0603")
      (description "Resistor")
      (fields (field (name "ALTIUM_VALUE") "0") (field (name "PUBLISHER") "Altium Limited"))
      (libsource (lib "Miscellaneous Devices") (part "Res3"))
    )
    (comp (ref "R163")
      (value "Res3")
      (footprint "Buck:R0603")
      (description "Resistor")
      (fields (field (name "ALTIUM_VALUE") "0") (field (name "PUBLISHER") "Altium Limited"))
      (libsource (lib "Miscellaneous Devices") (part "Res3"))
    )
    (comp (ref "R164") (value "ResSMD") (footprint "Buck:R0805") (libsource (lib "MYLIB") (part "ResSMD")))
    (comp (ref "R165") (value "ResSMD") (footprint "Buck:R0805") (libsource (lib "MYLIB") (part "ResSMD")))
    (comp (ref "R166") (value "ResSMD") (footprint "Buck:R0805") (libsource (lib "MYLIB") (part "ResSMD")))
    (comp (ref "R167") (value "0 SMD") (footprint "Buck:R0805") (libsource (lib "MYLIB") (part "ResSMD")))
    (comp (ref "R168") (value "0 SMD") (footprint "Buck:R0805") (libsource (lib "MYLIB") (part "ResSMD")))
    (comp (ref "R169") (value "ResSMD") (footprint "Buck:R0805") (libsource (lib "MYLIB") (part "ResSMD")))
    (comp (ref "R170") (value "ResSMD") (footprint "Buck:R0805") (libsource (lib "MYLIB") (part "ResSMD")))
    (comp (ref "R171") (value "0 SMD") (footprint "Buck:R0805") (libsource (lib "MYLIB") (part "ResSMD")))
    (comp (ref "R172") (value "0 SMD") (footprint "Buck:R0805") (libsource (lib "MYLIB") (part "ResSMD")))
    (comp (ref "R173") (value "ResSMD") (footprint "Buck:R0805") (libsource (lib "MYLIB") (part "ResSMD")))
    (comp (ref "R174") (value "ResSMD") (footprint "Buck:R0805") (libsource (lib "MYLIB") (part "ResSMD")))
    (comp (ref "R175") (value "ResSMD") (footprint "Buck:R0805") (libsource (lib "MYLIB") (part "ResSMD")))
    (comp (ref "TP1")
      (value "Pad")
      (footprint "Buck:TP-0.5mm")
      (libsource (lib "MYLIB") (part "Con1 pin-Small"))
    )
    (comp (ref "TP2")
      (value "Pad")
      (footprint "Buck:TP-0.5mm")
      (libsource (lib "") (part "Con1 pin-Small_3"))
    )
    (comp (ref "TP3")
      (value "Pad")
      (footprint "Buck:TP-0.5mm")
      (libsource (lib "MYLIB") (part "Con1 pin-Small"))
    )
    (comp (ref "TP4")
      (value "Pad")
      (footprint "Buck:TP-0.5mm")
      (libsource (lib "MYLIB") (part "Con1 pin-Small"))
    )
    (comp (ref "TP5")
      (value "Pad")
      (footprint "Buck:TP-0.5mm")
      (libsource (lib "MYLIB") (part "Con1 pin-Small"))
    )
    (comp (ref "TP6")
      (value "Pad")
      (footprint "Buck:TP-0.5mm")
      (libsource (lib "") (part "Con1 pin-Small_3"))
    )
    (comp (ref "TP7")
      (value "Pad")
      (footprint "Buck:TP-0.5mm")
      (libsource (lib "") (part "Con1 pin-Small_2"))
    )
    (comp (ref "TP8")
      (value "Pad")
      (footprint "Buck:TP-0.5mm")
      (libsource (lib "") (part "Con1 pin-Small_1"))
    )
    (comp (ref "TP9")
      (value "Pad")
      (footprint "Buck:TP-0.5mm")
      (libsource (lib "MYLIB") (part "Con1 pin-Small"))
    )
    (comp (ref "TP10")
      (value "Pad")
      (footprint "Buck:TP-0.5mm")
      (libsource (lib "MYLIB") (part "Con1 pin-Small"))
    )
    (comp (ref "TP11")
      (value "Pad")
      (footprint "Buck:TP-0.5mm")
      (libsource (lib "MYLIB") (part "Con1 pin-Small"))
    )
    (comp (ref "TP12")
      (value "Pad")
      (footprint "Buck:TP-0.5mm")
      (libsource (lib "") (part "Con1 pin-Small_3"))
    )
    (comp (ref "TP13")
      (value "Pad")
      (footprint "Buck:TP-0.5mm")
      (libsource (lib "") (part "Con1 pin-Small_2"))
    )
    (comp (ref "TP14")
      (value "Pad")
      (footprint "Buck:TP-0.5mm")
      (libsource (lib "") (part "Con1 pin-Small_1"))
    )
    (comp (ref "TP15")
      (value "Pad")
      (footprint "Buck:TP-0.5mm")
      (libsource (lib "MYLIB") (part "Con1 pin-Small"))
    )
    (comp (ref "TP16")
      (value "Pad")
      (footprint "Buck:TP-0.5mm")
      (libsource (lib "MYLIB") (part "Con1 pin-Small"))
    )
    (comp (ref "TP17")
      (value "Pad")
      (footprint "Buck:TP-0.5mm")
      (libsource (lib "MYLIB") (part "Con1 pin-Small"))
    )
    (comp (ref "TP18")
      (value "Pad")
      (footprint "Buck:TP-0.5mm")
      (libsource (lib "") (part "Con1 pin-Small_3"))
    )
    (comp (ref "TP19")
      (value "Pad")
      (footprint "Buck:TP-0.5mm")
      (libsource (lib "") (part "Con1 pin-Small_2"))
    )
    (comp (ref "TP20")
      (value "Pad")
      (footprint "Buck:TP-0.5mm")
      (libsource (lib "") (part "Con1 pin-Small_1"))
    )
    (comp (ref "TP21")
      (value "Pad")
      (footprint "Buck:TP-0.5mm")
      (libsource (lib "MYLIB") (part "Con1 pin-Small"))
    )
    (comp (ref "TP22")
      (value "Pad")
      (footprint "Buck:TP-0.5mm")
      (libsource (lib "MYLIB") (part "Con1 pin-Small"))
    )
    (comp (ref "TP23")
      (value "Pad")
      (footprint "Buck:TP-0.5mm")
      (libsource (lib "MYLIB") (part "Con1 pin-Small"))
    )
    (comp (ref "TP24")
      (value "Pad")
      (footprint "Buck:TP-0.5mm")
      (libsource (lib "") (part "Con1 pin-Small_3"))
    )
    (comp (ref "TP25")
      (value "Pad")
      (footprint "Buck:TP-0.5mm")
      (libsource (lib "MYLIB") (part "Con1 pin-Small"))
    )
    (comp (ref "TP26")
      (value "Pad")
      (footprint "Buck:TP-0.5mm")
      (libsource (lib "MYLIB") (part "Con1 pin-Small"))
    )
    (comp (ref "TP27")
      (value "Pad")
      (footprint "Buck:TP-0.5mm")
      (libsource (lib "") (part "Con1 pin-Small_2"))
    )
    (comp (ref "TP28")
      (value "Pad")
      (footprint "Buck:TP-0.5mm")
      (libsource (lib "") (part "Con1 pin-Small_1"))
    )
    (comp (ref "TP29")
      (value "Pad")
      (footprint "Buck:TP-0.5mm")
      (libsource (lib "") (part "Con1 pin-Small_2"))
    )
    (comp (ref "TP30")
      (value "Pad")
      (footprint "Buck:TP-0.5mm")
      (libsource (lib "MYLIB") (part "Con1 pin-Small"))
    )
    (comp (ref "TP31")
      (value "Pad")
      (footprint "Buck:TP-0.5mm")
      (libsource (lib "MYLIB") (part "Con1 pin-Small"))
    )
    (comp (ref "TP32")
      (value "Pad")
      (footprint "Buck:TP-0.5mm")
      (libsource (lib "") (part "Con1 pin-Small_1"))
    )
    (comp (ref "TP33")
      (value "Pad")
      (footprint "Buck:TP-0.5mm")
      (libsource (lib "") (part "Con1 pin-Small_2"))
    )
    (comp (ref "TP34")
      (value "Pad")
      (footprint "Buck:TP-0.5mm")
      (libsource (lib "") (part "Con1 pin-Small_1"))
    )
    (comp (ref "TP35")
      (value "Pad")
      (footprint "Buck:TP-0.5mm")
      (libsource (lib "MYLIB") (part "Con1 pin-Small"))
    )
    (comp (ref "TP36")
      (value "Pad")
      (footprint "Buck:TP-0.5mm")
      (libsource (lib "MYLIB") (part "Con1 pin-Small"))
    )
    (comp (ref "TP37")
      (value "Pad")
      (footprint "Buck:TP-0.5mm")
      (libsource (lib "") (part "Con1 pin-Small_1"))
    )
    (comp (ref "TP38")
      (value "Pad")
      (footprint "Buck:TP-0.5mm")
      (libsource (lib "") (part "Con1 pin-Small_2"))
    )
    (comp (ref "TP39")
      (value "Pad")
      (footprint "Buck:TP-0.5mm")
      (libsource (lib "") (part "Con1 pin-Small_3"))
    )
    (comp (ref "TP40")
      (value "Pad")
      (footprint "Buck:TP-0.5mm")
      (libsource (lib "MYLIB") (part "Con1 pin-Small"))
    )
    (comp (ref "TP41")
      (value "Pad")
      (footprint "Buck:TP-0.5mm")
      (libsource (lib "MYLIB") (part "Con1 pin-Small"))
    )
    (comp (ref "TP42")
      (value "Pad")
      (footprint "Buck:TP-0.5mm")
      (libsource (lib "") (part "Con1 pin-Small_1"))
    )
    (comp (ref "TP43")
      (value "Pad")
      (footprint "Buck:TP-0.5mm")
      (libsource (lib "MYLIB") (part "Con1 pin-Small"))
    )
    (comp (ref "TP44")
      (value "Pad")
      (footprint "Buck:TP-0.5mm")
      (libsource (lib "MYLIB") (part "Con1 pin-Small"))
    )
    (comp (ref "TP45")
      (value "Pad")
      (footprint "Buck:TP-0.5mm")
      (libsource (lib "") (part "Con1 pin-Small_2"))
    )
    (comp (ref "TP46")
      (value "Pad")
      (footprint "Buck:TP-0.5mm")
      (libsource (lib "") (part "Con1 pin-Small_1"))
    )
    (comp (ref "TP47")
      (value "Pad")
      (footprint "Buck:TP-0.5mm")
      (libsource (lib "MYLIB") (part "Con1 pin-Small"))
    )
    (comp (ref "TP48")
      (value "Pad")
      (footprint "Buck:TP-0.5mm")
      (libsource (lib "") (part "Con1 pin-Small_1"))
    )
    (comp (ref "TP49")
      (value "Pad")
      (footprint "Buck:TP-0.5mm")
      (libsource (lib "MYLIB") (part "Con1 pin-Small"))
    )
    (comp (ref "TP50")
      (value "Pad")
      (footprint "Buck:TP-0.5mm")
      (libsource (lib "MYLIB") (part "Con1 pin-Small"))
    )
    (comp (ref "TP51")
      (value "Pad")
      (footprint "Buck:TP-0.5mm")
      (libsource (lib "MYLIB") (part "Con1 pin-Small"))
    )
    (comp (ref "TP52")
      (value "Pad")
      (footprint "Buck:TP-0.5mm")
      (libsource (lib "MYLIB") (part "Con1 pin-Small"))
    )
    (comp (ref "TP53")
      (value "Pad")
      (footprint "Buck:TP-0.5mm")
      (libsource (lib "") (part "Con1 pin-Small_3"))
    )
    (comp (ref "TP54")
      (value "Pad")
      (footprint "Buck:TP-0.5mm")
      (libsource (lib "MYLIB") (part "Con1 pin-Small"))
    )
    (comp (ref "TP55")
      (value "Pad")
      (footprint "Buck:TP-0.5mm")
      (libsource (lib "") (part "Con1 pin-Small_3"))
    )
    (comp (ref "TP56")
      (value "Pad")
      (footprint "Buck:TP-0.5mm")
      (libsource (lib "") (part "Con1 pin-Small_3"))
    )
    (comp (ref "TP57")
      (value "Pad")
      (footprint "Buck:TP-0.5mm")
      (libsource (lib "") (part "Con1 pin-Small_3"))
    )
    (comp (ref "TP58")
      (value "Pad")
      (footprint "Buck:TP-0.5mm")
      (libsource (lib "MYLIB") (part "Con1 pin-Small"))
    )
    (comp (ref "TP59")
      (value "Pad")
      (footprint "Buck:TP-0.5mm")
      (libsource (lib "MYLIB") (part "Con1 pin-Small"))
    )
    (comp (ref "TP60")
      (value "Pad")
      (footprint "Buck:TP-0.5mm")
      (libsource (lib "MYLIB") (part "Con1 pin-Small"))
    )
    (comp (ref "TP61")
      (value "Pad")
      (footprint "Buck:TP-0.5mm")
      (libsource (lib "") (part "Con1 pin-Small_3"))
    )
    (comp (ref "TP62")
      (value "Pad")
      (footprint "Buck:TP-0.5mm")
      (libsource (lib "MYLIB") (part "Con1 pin-Small"))
    )
    (comp (ref "TP63")
      (value "Pad")
      (footprint "Buck:TP-0.5mm")
      (libsource (lib "") (part "Con1 pin-Small_3"))
    )
    (comp (ref "TP64")
      (value "Pad")
      (footprint "Buck:TP-0.5mm")
      (libsource (lib "") (part "Con1 pin-Small_1"))
    )
    (comp (ref "TP65")
      (value "Pad")
      (footprint "Buck:TP-0.5mm")
      (libsource (lib "") (part "Con1 pin-Small_3"))
    )
    (comp (ref "TP66")
      (value "Pad")
      (footprint "Buck:TP-0.5mm")
      (libsource (lib "") (part "Con1 pin-Small_2"))
    )
    (comp (ref "TP67")
      (value "Pad")
      (footprint "Buck:TP-0.5mm")
      (libsource (lib "") (part "Con1 pin-Small_2"))
    )
    (comp (ref "TP68")
      (value "Pad")
      (footprint "Buck:TP-0.5mm")
      (libsource (lib "MYLIB") (part "Con1 pin-Small"))
    )
    (comp (ref "TP69")
      (value "Pad")
      (footprint "Buck:TP-0.5mm")
      (libsource (lib "MYLIB") (part "Con1 pin-Small"))
    )
    (comp (ref "TP70")
      (value "Pad")
      (footprint "Buck:TP-0.5mm")
      (libsource (lib "MYLIB") (part "Con1 pin-Small"))
    )
    (comp (ref "TP71")
      (value "Pad")
      (footprint "Buck:TP-0.5mm")
      (libsource (lib "MYLIB") (part "Con1 pin-Small"))
    )
    (comp (ref "TP72")
      (value "Pad")
      (footprint "Buck:TP-0.5mm")
      (libsource (lib "MYLIB") (part "Con1 pin-Small"))
    )
    (comp (ref "TP73")
      (value "Pad")
      (footprint "Buck:TP-0.5mm")
      (libsource (lib "") (part "Con1 pin-Small_3"))
    )
    (comp (ref "TP74")
      (value "Pad")
      (footprint "Buck:TP-0.5mm")
      (libsource (lib "MYLIB") (part "Con1 pin-Small"))
    )
    (comp (ref "TP75")
      (value "Pad")
      (footprint "Buck:TP-0.5mm")
      (libsource (lib "MYLIB") (part "Con1 pin-Small"))
    )
    (comp (ref "TP76")
      (value "Pad")
      (footprint "Buck:TP-0.5mm")
      (libsource (lib "") (part "Con1 pin-Small_1"))
    )
    (comp (ref "TP77")
      (value "Pad")
      (footprint "Buck:TP-0.5mm")
      (libsource (lib "") (part "Con1 pin-Small_3"))
    )
    (comp (ref "TP78")
      (value "Pad")
      (footprint "Buck:TP-0.5mm")
      (libsource (lib "") (part "Con1 pin-Small_2"))
    )
    (comp (ref "TP79")
      (value "Pad")
      (footprint "Buck:TP-0.5mm")
      (libsource (lib "MYLIB") (part "Con1 pin-Small"))
    )
    (comp (ref "TP80")
      (value "Pad")
      (footprint "Buck:TP-0.5mm")
      (libsource (lib "") (part "Con1 pin-Small_3"))
    )
    (comp (ref "TP81")
      (value "Pad")
      (footprint "Buck:TP-0.5mm")
      (libsource (lib "MYLIB") (part "Con1 pin-Small"))
    )
    (comp (ref "TP82")
      (value "Pad")
      (footprint "Buck:TP-0.5mm")
      (libsource (lib "MYLIB") (part "Con1 pin-Small"))
    )
    (comp (ref "TP83")
      (value "Pad")
      (footprint "Buck:TP-0.5mm")
      (libsource (lib "") (part "Con1 pin-Small_2"))
    )
    (comp (ref "TP84")
      (value "Pad")
      (footprint "Buck:TP-0.5mm")
      (libsource (lib "") (part "Con1 pin-Small_2"))
    )
    (comp (ref "TP85")
      (value "Pad")
      (footprint "Buck:TP-0.5mm")
      (libsource (lib "MYLIB") (part "Con1 pin-Small"))
    )
    (comp (ref "TP86")
      (value "Pad")
      (footprint "Buck:TP-0.5mm")
      (libsource (lib "MYLIB") (part "Con1 pin-Small"))
    )
    (comp (ref "TP87")
      (value "Pad")
      (footprint "Buck:TP-0.5mm")
      (libsource (lib "") (part "Con1 pin-Small_1"))
    )
    (comp (ref "U1")
      (value "MJWI10-24S12-MIN")
      (footprint "Buck:MJWI10-24S12")
      (libsource (lib "MYLIB") (part "MINMAX-MJWI20"))
    )
    (comp (ref "U2")
      (value "SN74LVC1G17DBVT SOT23")
      (footprint "Buck:SOT95P280X145-5N")
      (description "IC BUF NON-INVERT 5.5V SC70-5")
      (libsource (lib "Miscellaneous Devices") (part "333895c48767551a2a38df23237d11a"))
    )
    (comp (ref "U3")
      (value "PC81713NIP1B")
      (footprint "Buck:SOP-4L")
      (libsource (lib "MYLIB") (part "PC817"))
    )
    (comp (ref "U4")
      (value "SN74LVC1G17DBVT SOT23")
      (footprint "Buck:SOT95P280X145-5N")
      (description "IC BUF NON-INVERT 5.5V SC70-5")
      (libsource (lib "Miscellaneous Devices") (part "333895c48767551a2a38df23237d11a"))
    )
    (comp (ref "U5")
      (value "SI8261BBD-C-ISR")
      (footprint "Buck:SLAB-SDIP6_N")
      (fields (field (name "PARTNUMBER") "Si8261BBD-C-IS") (field (name "MANUFACTURER") "Silicon Labs"))
      (libsource (lib "Miscellaneous Devices") (part "SLAB-Si8261X-SDIP-6"))
    )
    (comp (ref "U6")
      (value "IXDN609SIATR")
      (footprint "Buck:IXDN609SIATR")
      (fields (field (name "PARTNUMBER") "IXDN609SI"))
      (libsource (lib "Miscellaneous Devices") (part "IXYS-IXDN609-8"))
    )
    (comp (ref "U7")
      (value "SN74LVC1G17DBVT SOT23")
      (footprint "Buck:SOT95P280X145-5N")
      (description "IC BUF NON-INVERT 5.5V SC70-5")
      (libsource (lib "Miscellaneous Devices") (part "333895c48767551a2a38df23237d11a"))
    )
    (comp (ref "U8")
      (value "SI8261BBD-C-ISR")
      (footprint "Buck:SLAB-SDIP6_N")
      (fields (field (name "PARTNUMBER") "Si8261BBD-C-IS") (field (name "MANUFACTURER") "Silicon Labs"))
      (libsource (lib "Miscellaneous Devices") (part "SLAB-Si8261X-SDIP-6"))
    )
    (comp (ref "U9")
      (value "IXDN609SIATR")
      (footprint "Buck:IXDN609SIATR")
      (fields (field (name "PARTNUMBER") "IXDN609SI"))
      (libsource (lib "Miscellaneous Devices") (part "IXYS-IXDN609-8"))
    )
    (comp (ref "U10")
      (value "SN74LVC1G17DBVT SOT23")
      (footprint "Buck:SOT95P280X145-5N")
      (description "IC BUF NON-INVERT 5.5V SC70-5")
      (libsource (lib "Miscellaneous Devices") (part "333895c48767551a2a38df23237d11a"))
    )
    (comp (ref "U11")
      (value "SI8261BBD-C-ISR")
      (footprint "Buck:SLAB-SDIP6_N")
      (fields (field (name "PARTNUMBER") "Si8261BBD-C-IS") (field (name "MANUFACTURER") "Silicon Labs"))
      (libsource (lib "Miscellaneous Devices") (part "SLAB-Si8261X-SDIP-6"))
    )
    (comp (ref "U12")
      (value "IXDN609SIATR")
      (footprint "Buck:IXDN609SIATR")
      (fields (field (name "PARTNUMBER") "IXDN609SI"))
      (libsource (lib "Miscellaneous Devices") (part "IXYS-IXDN609-8"))
    )
    (comp (ref "U13")
      (value "SN74LVC1G17DBVT SOT23")
      (footprint "Buck:SOT95P280X145-5N")
      (description "IC BUF NON-INVERT 5.5V SC70-5")
      (libsource (lib "Miscellaneous Devices") (part "333895c48767551a2a38df23237d11a"))
    )
    (comp (ref "U14")
      (value "SI8261BBD-C-ISR")
      (footprint "Buck:SLAB-SDIP6_N")
      (fields (field (name "PARTNUMBER") "Si8261BBD-C-IS") (field (name "MANUFACTURER") "Silicon Labs"))
      (libsource (lib "Miscellaneous Devices") (part "SLAB-Si8261X-SDIP-6"))
    )
    (comp (ref "U15")
      (value "IXDN609SIATR")
      (footprint "Buck:IXDN609SIATR")
      (fields (field (name "PARTNUMBER") "IXDN609SI"))
      (libsource (lib "Miscellaneous Devices") (part "IXYS-IXDN609-8"))
    )
    (comp (ref "U16")
      (value "LT1764AEQ-3.3")
      (footprint "Buck:LT1764AEQ33TRPBF")
      (fields (field (name "MANUFACTURER") "Linear Technology"))
      (libsource (lib "Linear Technology Power Management LDO Linear Regulators") (part "LT1764AEQ-3.3"))
    )
    (comp (ref "U17")
      (value "CAS 15-NP")
      (footprint "Buck:CAS 15-NP")
      (description "Current Transducer, 5 V, -40 to 85 degC, 10-Pin THD, RoHS, Tray")
      (fields (field (name "MANUFACTURER") "LEM") (field (name "PARTNUMBER") "LTSR 15-NP"))
      (libsource (lib "Miscellaneous Devices") (part "CAS 15-NP"))
    )
    (comp (ref "U19")
      (value "TLV2781IDBVR")
      (footprint "Buck:DBV0005A_L")
      (fields (field (name "PARTNUMBER") "OPA320AIDBVR") (field (name "MANUFACTURER") "Texas Instruments"))
      (libsource (lib "Miscellaneous Devices") (part "TI-OPA_SM7XXXX-DBV5"))
    )
    (comp (ref "U20")
      (value "NCV8114ASN165T1G")
      (footprint "Buck:TSOP-5")
      (libsource (lib "Miscellaneous Devices") (part "ONSC-MC78PC-SOT-23-5"))
    )
    (comp (ref "U21")
      (value "OPA27GP")
      (footprint "Buck:P0008A")
      (fields (field (name "MANUFACTURER") "Texas Instruments"))
      (libsource (lib "Miscellaneous Devices") (part "TI-OPA27-X8"))
    )
  )
  (nets
    (net (code "1") (name "+3.3VD") (class "Default")
      (node (ref "C73") (pin "2") (pinfunction "2_2") (pintype "passive"))
      (node (ref "R11") (pin "2") (pinfunction "2_2") (pintype "passive"))
      (node (ref "R140") (pin "1") (pinfunction "1_1") (pintype "passive"))
      (node (ref "R150") (pin "2") (pinfunction "2_2") (pintype "passive"))
      (node (ref "R171") (pin "1") (pinfunction "1_1") (pintype "passive"))
      (node (ref "R2") (pin "2") (pinfunction "2_2") (pintype "passive"))
      (node (ref "R44") (pin "2") (pinfunction "2_2") (pintype "passive"))
      (node (ref "R70") (pin "2") (pinfunction "2_2") (pintype "passive"))
      (node (ref "R95") (pin "2") (pinfunction "2_2") (pintype "passive"))
      (node (ref "U19") (pin "5") (pinfunction "V+_5") (pintype "power_in"))
    )
    (net (code "2") (name "+3.3VD2") (class "Default")
      (node (ref "C60") (pin "1") (pinfunction "1_1") (pintype "passive"))
      (node (ref "C64") (pin "2") (pinfunction "2_2") (pintype "passive"))
      (node (ref "DS10") (pin "1") (pinfunction "A_1") (pintype "passive"))
      (node (ref "R14") (pin "1") (pinfunction "1_1") (pintype "passive"))
      (node (ref "R92") (pin "2") (pinfunction "2_2") (pintype "passive"))
      (node (ref "TP26") (pin "1") (pinfunction "1_1") (pintype "passive"))
      (node (ref "U16") (pin "4") (pinfunction "OUT_4") (pintype "power_in"))
      (node (ref "U16") (pin "5") (pinfunction "SENSE_5") (pintype "input"))
    )
    (net (code "3") (name "+5V_MICRO") (class "Default")
      (node (ref "C69") (pin "2") (pinfunction "2_2") (pintype "passive"))
      (node (ref "C71") (pin "2") (pinfunction "2_2") (pintype "passive"))
      (node (ref "C72") (pin "2") (pinfunction "2_2") (pintype "passive"))
      (node (ref "C78") (pin "2") (pinfunction "2_2") (pintype "passive"))
      (node (ref "DS12") (pin "1") (pinfunction "A_1") (pintype "passive"))
      (node (ref "FB11") (pin "1") (pinfunction "1_1") (pintype "power_in"))
      (node (ref "J2") (pin "13") (pinfunction "13_13") (pintype "passive"))
      (node (ref "J2") (pin "25") (pinfunction "25_25") (pintype "passive"))
      (node (ref "R12") (pin "1") (pinfunction "1_1") (pintype "passive"))
      (node (ref "R138") (pin "1") (pinfunction "1_1") (pintype "passive"))
      (node (ref "R144") (pin "1") (pinfunction "1_1") (pintype "passive"))
      (node (ref "R149") (pin "2") (pinfunction "2_2") (pintype "passive"))
      (node (ref "R15") (pin "1") (pinfunction "1_1") (pintype "passive"))
      (node (ref "R172") (pin "2") (pinfunction "2_2") (pintype "passive"))
      (node (ref "R3") (pin "1") (pinfunction "1_1") (pintype "passive"))
      (node (ref "R45") (pin "1") (pinfunction "1_1") (pintype "passive"))
      (node (ref "R71") (pin "1") (pinfunction "1_1") (pintype "passive"))
      (node (ref "R93") (pin "2") (pinfunction "2_2") (pintype "passive"))
      (node (ref "R96") (pin "1") (pinfunction "1_1") (pintype "passive"))
      (node (ref "TP25") (pin "1") (pinfunction "1_1") (pintype "passive"))
      (node (ref "TP63") (pin "1") (pinfunction "1_1") (pintype "passive"))
      (node (ref "U17") (pin "13") (pinfunction "+5V_13") (pintype "passive"))
      (node (ref "U20") (pin "1") (pinfunction "VIN_1") (pintype "power_in"))
    )
    (net (code "4") (name "+12V_Digital IN") (class "Default")
      (node (ref "C2") (pin "1") (pinfunction "1_1") (pintype "passive"))
      (node (ref "C49") (pin "1") (pinfunction "1_1") (pintype "passive"))
      (node (ref "C52") (pin "1") (pinfunction "1_1") (pintype "passive"))
      (node (ref "C56") (pin "1") (pinfunction "1_1") (pintype "passive"))
      (node (ref "C68") (pin "1") (pinfunction "1_1") (pintype "passive"))
      (node (ref "J1") (pin "1") (pinfunction "1_1") (pintype "passive"))
      (node (ref "PS1") (pin "22") (pinfunction "+VIN_22") (pintype "input"))
      (node (ref "PS1") (pin "23") (pinfunction "+VIN_23") (pintype "input"))
      (node (ref "PS2") (pin "22") (pinfunction "+VIN_22") (pintype "input"))
      (node (ref "PS2") (pin "23") (pinfunction "+VIN_23") (pintype "input"))
      (node (ref "PS3") (pin "22") (pinfunction "+VIN_22") (pintype "input"))
      (node (ref "PS3") (pin "23") (pinfunction "+VIN_23") (pintype "input"))
      (node (ref "PS4") (pin "22") (pinfunction "+VIN_22") (pintype "input"))
      (node (ref "PS4") (pin "23") (pinfunction "+VIN_23") (pintype "input"))
      (node (ref "TP55") (pin "1") (pinfunction "1_1") (pintype "passive"))
      (node (ref "U1") (pin "1") (pinfunction "+In_1") (pintype "passive"))
    )
    (net (code "5") (name "+VDDI") (class "Default")
      (node (ref "R92") (pin "1") (pinfunction "1_1") (pintype "passive"))
      (node (ref "R93") (pin "1") (pinfunction "1_1") (pintype "passive"))
    )
    (net (code "6") (name "1.65V") (class "Default")
      (node (ref "C79") (pin "2") (pinfunction "2_2") (pintype "passive"))
      (node (ref "R135") (pin "2") (pinfunction "2_2") (pintype "passive"))
      (node (ref "R146") (pin "1") (pinfunction "1_1") (pintype "passive"))
      (node (ref "TP86") (pin "1") (pinfunction "1_1") (pintype "passive"))
      (node (ref "U20") (pin "5") (pinfunction "VOUT_5") (pintype "power_in"))
    )
    (net (code "7") (name "3") (class "Default")
      (node (ref "J2") (pin "12") (pinfunction "12_12") (pintype "passive"))
      (node (ref "TP66") (pin "1") (pinfunction "1_1") (pintype "passive"))
    )
    (net (code "8") (name "4") (class "Default")
      (node (ref "J2") (pin "24") (pinfunction "24_24") (pintype "passive"))
      (node (ref "TP67") (pin "1") (pinfunction "1_1") (pintype "passive"))
    )
    (net (code "9") (name "AC Output") (class "Default")
      (node (ref "F2") (pin "2") (pinfunction "2_2") (pintype "passive"))
      (node (ref "P2") (pin "1") (pinfunction "1_1") (pintype "passive"))
      (node (ref "P2") (pin "2") (pinfunction "2_2") (pintype "passive"))
      (node (ref "R141") (pin "1") (pinfunction "1_1") (pintype "passive"))
      (node (ref "TP69") (pin "1") (pinfunction "1_1") (pintype "passive"))
    )
    (net (code "10") (name "E FB TEMP") (class "Default")
      (node (ref "J2") (pin "8") (pinfunction "8_8") (pintype "passive"))
    )
    (net (code "11") (name "FB TEMP of the heatsink") (class "Default")
      (node (ref "FB2") (pin "2") (pinfunction "2_2") (pintype "power_in"))
      (node (ref "J2") (pin "16") (pinfunction "16_16") (pintype "passive"))
    )
    (net (code "12") (name "Fan") (class "Default")
      (node (ref "C3") (pin "1") (pinfunction "1_1") (pintype "passive"))
      (node (ref "C4") (pin "2") (pinfunction "2_2") (pintype "passive"))
      (node (ref "D1") (pin "1") (pinfunction "A_1") (pintype "passive"))
      (node (ref "DS1") (pin "1") (pinfunction "A_1") (pintype "passive"))
      (node (ref "P1") (pin "1") (pinfunction "1_1") (pintype "passive"))
      (node (ref "U1") (pin "3") (pinfunction "+Out_3") (pintype "passive"))
    )
    (net (code "13") (name "Fan FB command") (class "Default")
      (node (ref "FB1") (pin "1") (pinfunction "1_1") (pintype "power_in"))
      (node (ref "J2") (pin "23") (pinfunction "23_23") (pintype "passive"))
    )
    (net (code "14") (name "GND side FB") (class "Default")
      (node (ref "C21") (pin "1") (pinfunction "1_1") (pintype "passive"))
      (node (ref "C24") (pin "1") (pinfunction "1_1") (pintype "passive"))
      (node (ref "C26") (pin "2") (pinfunction "2_2") (pintype "passive"))
      (node (ref "C27") (pin "2") (pinfunction "2_2") (pintype "passive"))
      (node (ref "C28") (pin "2") (pinfunction "2_2") (pintype "passive"))
      (node (ref "C29") (pin "2") (pinfunction "2_2") (pintype "passive"))
      (node (ref "C30") (pin "2") (pinfunction "2_2") (pintype "passive"))
      (node (ref "C31") (pin "2") (pinfunction "2_2") (pintype "passive"))
      (node (ref "C32") (pin "1") (pinfunction "1_1") (pintype "passive"))
      (node (ref "C35") (pin "1") (pinfunction "1_1") (pintype "passive"))
      (node (ref "C37") (pin "2") (pinfunction "2_2") (pintype "passive"))
      (node (ref "C38") (pin "2") (pinfunction "2_2") (pintype "passive"))
      (node (ref "C39") (pin "1") (pinfunction "1_1") (pintype "passive"))
      (node (ref "C40") (pin "1") (pinfunction "1_1") (pintype "passive"))
      (node (ref "C45") (pin "2") (pinfunction "2_2") (pintype "passive"))
      (node (ref "C46") (pin "2") (pinfunction "2_2") (pintype "passive"))
      (node (ref "CR11") (pin "1") (pinfunction "A_1") (pintype "passive"))
      (node (ref "CR17") (pin "1") (pinfunction "A_1") (pintype "passive"))
      (node (ref "CR7") (pin "1") (pinfunction "A_1") (pintype "passive"))
      (node (ref "D13") (pin "1") (pinfunction "A_1") (pintype "passive"))
      (node (ref "D14") (pin "1") (pinfunction "A_1") (pintype "passive"))
      (node (ref "D15") (pin "1") (pinfunction "A_1") (pintype "passive"))
      (node (ref "D16") (pin "1") (pinfunction "A_1") (pintype "passive"))
      (node (ref "D17") (pin "1") (pinfunction "A_1") (pintype "passive"))
      (node (ref "D18") (pin "1") (pinfunction "A_1") (pintype "passive"))
      (node (ref "P3") (pin "3") (pinfunction "3_3") (pintype "passive"))
      (node (ref "P3") (pin "4") (pinfunction "4_4") (pintype "passive"))
      (node (ref "Q2") (pin "3") (pinfunction "E_3") (pintype "passive"))
      (node (ref "Q3") (pin "3") (pinfunction "E_3") (pintype "passive"))
      (node (ref "R125") (pin "1") (pinfunction "1_1") (pintype "passive"))
      (node (ref "R167") (pin "2") (pinfunction "2_2") (pintype "passive"))
      (node (ref "R168") (pin "2") (pinfunction "2_2") (pintype "passive"))
      (node (ref "R40") (pin "1") (pinfunction "1_1") (pintype "passive"))
      (node (ref "R42") (pin "2") (pinfunction "2_2") (pintype "passive"))
      (node (ref "R43") (pin "2") (pinfunction "2_2") (pintype "passive"))
      (node (ref "R51") (pin "1") (pinfunction "1_1") (pintype "passive"))
      (node (ref "R57") (pin "1") (pinfunction "1_1") (pintype "passive"))
      (node (ref "R58") (pin "1") (pinfunction "1_1") (pintype "passive"))
      (node (ref "R64") (pin "1") (pinfunction "1_1") (pintype "passive"))
      (node (ref "R65") (pin "2") (pinfunction "2_2") (pintype "passive"))
      (node (ref "R66") (pin "2") (pinfunction "2_2") (pintype "passive"))
      (node (ref "R68") (pin "1") (pinfunction "1_1") (pintype "passive"))
      (node (ref "R77") (pin "1") (pinfunction "1_1") (pintype "passive"))
      (node (ref "R86") (pin "1") (pinfunction "1_1") (pintype "passive"))
      (node (ref "TP33") (pin "1") (pinfunction "1_1") (pintype "passive"))
      (node (ref "TP83") (pin "1") (pinfunction "1_1") (pintype "passive"))
      (node (ref "TP84") (pin "1") (pinfunction "1_1") (pintype "passive"))
      (node (ref "TP85") (pin "1") (pinfunction "1_1") (pintype "passive"))
      (node (ref "U12") (pin "4") (pinfunction "GND_4") (pintype "power_in"))
      (node (ref "U12") (pin "5") (pinfunction "GND_5") (pintype "power_in"))
      (node (ref "U9") (pin "4") (pinfunction "GND_4") (pintype "power_in"))
      (node (ref "U9") (pin "5") (pinfunction "GND_5") (pintype "power_in"))
    )
    (net (code "15") (name "GND_DIGITAL") (class "Default")
      (node (ref "C1") (pin "2") (pinfunction "2_2") (pintype "passive"))
      (node (ref "C20") (pin "2") (pinfunction "2_2") (pintype "passive"))
      (node (ref "C41") (pin "2") (pinfunction "2_2") (pintype "passive"))
      (node (ref "C5") (pin "2") (pinfunction "2_2") (pintype "passive"))
      (node (ref "C53") (pin "2") (pinfunction "2_2") (pintype "passive"))
      (node (ref "C60") (pin "2") (pinfunction "2_2") (pintype "passive"))
      (node (ref "C62") (pin "1") (pinfunction "1_1") (pintype "passive"))
      (node (ref "C63") (pin "1") (pinfunction "1_1") (pintype "passive"))
      (node (ref "C64") (pin "1") (pinfunction "1_1") (pintype "passive"))
      (node (ref "C69") (pin "1") (pinfunction "1_1") (pintype "passive"))
      (node (ref "C71") (pin "1") (pinfunction "1_1") (pintype "passive"))
      (node (ref "C72") (pin "1") (pinfunction "1_1") (pintype "passive"))
      (node (ref "C73") (pin "1") (pinfunction "1_1") (pintype "passive"))
      (node (ref "C75") (pin "1") (pinfunction "1_1") (pintype "passive"))
      (node (ref "C77") (pin "1") (pinfunction "1_1") (pintype "passive"))
      (node (ref "C78") (pin "1") (pinfunction "1_1") (pintype "passive"))
      (node (ref "C79") (pin "1") (pinfunction "1_1") (pintype "passive"))
      (node (ref "C80") (pin "2") (pinfunction "2_2") (pintype "passive"))
      (node (ref "C82") (pin "2") (pinfunction "2_2") (pintype "passive"))
      (node (ref "C83") (pin "2") (pinfunction "2_2") (pintype "passive"))
      (node (ref "C86") (pin "2") (pinfunction "2_2") (pintype "passive"))
      (node (ref "J2") (pin "1") (pinfunction "1_1") (pintype "passive"))
      (node (ref "J2") (pin "14") (pinfunction "14_14") (pintype "passive"))
      (node (ref "Q5") (pin "5") (pinfunction "GND2_5") (pintype "power_in"))
      (node (ref "R10") (pin "2") (pinfunction "2_2") (pintype "passive"))
      (node (ref "R100") (pin "2") (pinfunction "2_2") (pintype "passive"))
      (node (ref "R101") (pin "2") (pinfunction "2_2") (pintype "passive"))
      (node (ref "R102") (pin "2") (pinfunction "2_2") (pintype "passive"))
      (node (ref "R103") (pin "2") (pinfunction "2_2") (pintype "passive"))
      (node (ref "R104") (pin "2") (pinfunction "2_2") (pintype "passive"))
      (node (ref "R105") (pin "2") (pinfunction "2_2") (pintype "passive"))
      (node (ref "R111") (pin "1") (pinfunction "1_1") (pintype "passive"))
      (node (ref "R113") (pin "2") (pinfunction "2_2") (pintype "passive"))
      (node (ref "R114") (pin "1") (pinfunction "1_1") (pintype "passive"))
      (node (ref "R115") (pin "2") (pinfunction "2_2") (pintype "passive"))
      (node (ref "R116") (pin "2") (pinfunction "2_2") (pintype "passive"))
      (node (ref "R117") (pin "2") (pinfunction "2_2") (pintype "passive"))
      (node (ref "R118") (pin "1") (pinfunction "1_1") (pintype "passive"))
      (node (ref "R121") (pin "2") (pinfunction "2_2") (pintype "passive"))
      (node (ref "R122") (pin "2") (pinfunction "2_2") (pintype "passive"))
      (node (ref "R124") (pin "1") (pinfunction "1_1") (pintype "passive"))
      (node (ref "R129") (pin "1") (pinfunction "1_1") (pintype "passive"))
      (node (ref "R134") (pin "2") (pinfunction "2_2") (pintype "passive"))
      (node (ref "R136") (pin "1") (pinfunction "1_1") (pintype "passive"))
      (node (ref "R137") (pin "2") (pinfunction "2_2") (pintype "passive"))
      (node (ref "R139") (pin "2") (pinfunction "2_2") (pintype "passive"))
      (node (ref "R143") (pin "2") (pinfunction "2_2") (pintype "passive"))
      (node (ref "R145") (pin "1") (pinfunction "1_1") (pintype "passive"))
      (node (ref "R160") (pin "2") (pinfunction "2_2") (pintype "passive"))
      (node (ref "R164") (pin "2") (pinfunction "2_2") (pintype "passive"))
      (node (ref "R175") (pin "2") (pinfunction "2_2") (pintype "passive"))
      (node (ref "R21") (pin "1") (pinfunction "1_1") (pintype "passive"))
      (node (ref "R23") (pin "2") (pinfunction "2_2") (pintype "passive"))
      (node (ref "R24") (pin "2") (pinfunction "2_2") (pintype "passive"))
      (node (ref "R25") (pin "1") (pinfunction "1_1") (pintype "passive"))
      (node (ref "R26") (pin "2") (pinfunction "2_2") (pintype "passive"))
      (node (ref "R27") (pin "2") (pinfunction "2_2") (pintype "passive"))
      (node (ref "R28") (pin "2") (pinfunction "2_2") (pintype "passive"))
      (node (ref "R29") (pin "1") (pinfunction "1_1") (pintype "passive"))
      (node (ref "R53") (pin "1") (pinfunction "1_1") (pintype "passive"))
      (node (ref "R56") (pin "2") (pinfunction "2_2") (pintype "passive"))
      (node (ref "R59") (pin "1") (pinfunction "1_1") (pintype "passive"))
      (node (ref "R6") (pin "1") (pinfunction "1_1") (pintype "passive"))
      (node (ref "R60") (pin "2") (pinfunction "2_2") (pintype "passive"))
      (node (ref "R61") (pin "2") (pinfunction "2_2") (pintype "passive"))
      (node (ref "R62") (pin "2") (pinfunction "2_2") (pintype "passive"))
      (node (ref "R63") (pin "1") (pinfunction "1_1") (pintype "passive"))
      (node (ref "R78") (pin "1") (pinfunction "1_1") (pintype "passive"))
      (node (ref "R80") (pin "2") (pinfunction "2_2") (pintype "passive"))
      (node (ref "R81") (pin "1") (pinfunction "1_1") (pintype "passive"))
      (node (ref "R82") (pin "2") (pinfunction "2_2") (pintype "passive"))
      (node (ref "R83") (pin "2") (pinfunction "2_2") (pintype "passive"))
      (node (ref "R84") (pin "2") (pinfunction "2_2") (pintype "passive"))
      (node (ref "R85") (pin "1") (pinfunction "1_1") (pintype "passive"))
      (node (ref "R98") (pin "2") (pinfunction "2_2") (pintype "passive"))
      (node (ref "R99") (pin "2") (pinfunction "2_2") (pintype "passive"))
      (node (ref "TP14") (pin "1") (pinfunction "1_1") (pintype "passive"))
      (node (ref "TP20") (pin "1") (pinfunction "1_1") (pintype "passive"))
      (node (ref "TP28") (pin "1") (pinfunction "1_1") (pintype "passive"))
      (node (ref "TP29") (pin "1") (pinfunction "1_1") (pintype "passive"))
      (node (ref "TP32") (pin "1") (pinfunction "1_1") (pintype "passive"))
      (node (ref "TP38") (pin "1") (pinfunction "1_1") (pintype "passive"))
      (node (ref "TP39") (pin "1") (pinfunction "1_1") (pintype "passive"))
      (node (ref "TP48") (pin "1") (pinfunction "1_1") (pintype "passive"))
      (node (ref "TP64") (pin "1") (pinfunction "1_1") (pintype "passive"))
      (node (ref "TP8") (pin "1") (pinfunction "1_1") (pintype "passive"))
      (node (ref "TP87") (pin "1") (pinfunction "1_1") (pintype "passive"))
      (node (ref "U10") (pin "3") (pinfunction "GND_3") (pintype "power_in"))
      (node (ref "U11") (pin "3") (pinfunction "CATHODE_3") (pintype "passive"))
      (node (ref "U13") (pin "3") (pinfunction "GND_3") (pintype "power_in"))
      (node (ref "U14") (pin "3") (pinfunction "CATHODE_3") (pintype "passive"))
      (node (ref "U16") (pin "3") (pinfunction "GND_3") (pintype "power_in"))
      (node (ref "U16") (pin "6") (pinfunction "TAB_6") (pintype "power_in"))
      (node (ref "U17") (pin "12") (pinfunction "0V_12") (pintype "passive"))
      (node (ref "U2") (pin "3") (pinfunction "GND_3") (pintype "power_in"))
      (node (ref "U20") (pin "2") (pinfunction "GND_2") (pintype "power_in"))
      (node (ref "U3") (pin "2") (pinfunction "K_2") (pintype "passive"))
      (node (ref "U4") (pin "3") (pinfunction "GND_3") (pintype "power_in"))
      (node (ref "U5") (pin "3") (pinfunction "CATHODE_3") (pintype "passive"))
      (node (ref "U7") (pin "3") (pinfunction "GND_3") (pintype "power_in"))
      (node (ref "U8") (pin "3") (pinfunction "CATHODE_3") (pintype "passive"))
    )
    (net (code "16") (name "GND_Fan") (class "Default")
      (node (ref "C3") (pin "2") (pinfunction "2_2") (pintype "passive"))
      (node (ref "C4") (pin "1") (pinfunction "1_1") (pintype "passive"))
      (node (ref "D2") (pin "1") (pinfunction "A_1") (pintype "passive"))
      (node (ref "P1") (pin "2") (pinfunction "2_2") (pintype "passive"))
      (node (ref "R1") (pin "2") (pinfunction "2_2") (pintype "passive"))
      (node (ref "TP2") (pin "1") (pinfunction "1_1") (pintype "passive"))
      (node (ref "U1") (pin "5") (pinfunction "-Out_5") (pintype "passive"))
    )
    (net (code "17") (name "GND_GS1") (class "Default")
      (node (ref "C19") (pin "2") (pinfunction "2_2") (pintype "passive"))
      (node (ref "C47") (pin "2") (pinfunction "2_2") (pintype "passive"))
      (node (ref "C48") (pin "1") (pinfunction "1_1") (pintype "passive"))
      (node (ref "C6") (pin "2") (pinfunction "2_2") (pintype "passive"))
      (node (ref "C7") (pin "2") (pinfunction "2_2") (pintype "passive"))
      (node (ref "C8") (pin "1") (pinfunction "1_1") (pintype "passive"))
      (node (ref "CR2") (pin "1") (pinfunction "A_1") (pintype "passive"))
      (node (ref "PS1") (pin "16") (pinfunction "-VOUT_16") (pintype "output"))
      (node (ref "R20") (pin "2") (pinfunction "2_2") (pintype "passive"))
      (node (ref "R35") (pin "1") (pinfunction "1_1") (pintype "passive"))
      (node (ref "R8") (pin "2") (pinfunction "2_2") (pintype "passive"))
      (node (ref "R87") (pin "2") (pinfunction "2_2") (pintype "passive"))
      (node (ref "TP53") (pin "1") (pinfunction "1_1") (pintype "passive"))
      (node (ref "TP6") (pin "1") (pinfunction "1_1") (pintype "passive"))
      (node (ref "U5") (pin "4") (pinfunction "GND_4") (pintype "power_in"))
    )
    (net (code "18") (name "GND_GS2") (class "Default")
      (node (ref "C33") (pin "2") (pinfunction "2_2") (pintype "passive"))
      (node (ref "C34") (pin "2") (pinfunction "2_2") (pintype "passive"))
      (node (ref "C36") (pin "1") (pinfunction "1_1") (pintype "passive"))
      (node (ref "C39") (pin "2") (pinfunction "2_2") (pintype "passive"))
      (node (ref "C50") (pin "2") (pinfunction "2_2") (pintype "passive"))
      (node (ref "C51") (pin "1") (pinfunction "1_1") (pintype "passive"))
      (node (ref "CR6") (pin "1") (pinfunction "A_1") (pintype "passive"))
      (node (ref "PS2") (pin "16") (pinfunction "-VOUT_16") (pintype "output"))
      (node (ref "R40") (pin "2") (pinfunction "2_2") (pintype "passive"))
      (node (ref "R51") (pin "2") (pinfunction "2_2") (pintype "passive"))
      (node (ref "R65") (pin "1") (pinfunction "1_1") (pintype "passive"))
      (node (ref "R88") (pin "2") (pinfunction "2_2") (pintype "passive"))
      (node (ref "TP12") (pin "1") (pinfunction "1_1") (pintype "passive"))
      (node (ref "TP56") (pin "1") (pinfunction "1_1") (pintype "passive"))
      (node (ref "U8") (pin "4") (pinfunction "GND_4") (pintype "power_in"))
    )
    (net (code "19") (name "GND_GS3") (class "Default")
      (node (ref "C40") (pin "2") (pinfunction "2_2") (pintype "passive"))
      (node (ref "C42") (pin "2") (pinfunction "2_2") (pintype "passive"))
      (node (ref "C43") (pin "2") (pinfunction "2_2") (pintype "passive"))
      (node (ref "C44") (pin "1") (pinfunction "1_1") (pintype "passive"))
      (node (ref "C54") (pin "1") (pinfunction "1_1") (pintype "passive"))
      (node (ref "C55") (pin "2") (pinfunction "2_2") (pintype "passive"))
      (node (ref "CR10") (pin "1") (pinfunction "A_1") (pintype "passive"))
      (node (ref "PS3") (pin "16") (pinfunction "-VOUT_16") (pintype "output"))
      (node (ref "R66") (pin "1") (pinfunction "1_1") (pintype "passive"))
      (node (ref "R68") (pin "2") (pinfunction "2_2") (pintype "passive"))
      (node (ref "R77") (pin "2") (pinfunction "2_2") (pintype "passive"))
      (node (ref "R94") (pin "2") (pinfunction "2_2") (pintype "passive"))
      (node (ref "TP18") (pin "1") (pinfunction "1_1") (pintype "passive"))
      (node (ref "TP61") (pin "1") (pinfunction "1_1") (pintype "passive"))
      (node (ref "U11") (pin "4") (pinfunction "GND_4") (pintype "power_in"))
    )
    (net (code "20") (name "GND_GS4") (class "Default")
      (node (ref "C23") (pin "2") (pinfunction "2_2") (pintype "passive"))
      (node (ref "C57") (pin "2") (pinfunction "2_2") (pintype "passive"))
      (node (ref "C58") (pin "2") (pinfunction "2_2") (pintype "passive"))
      (node (ref "C59") (pin "1") (pinfunction "1_1") (pintype "passive"))
      (node (ref "C61") (pin "2") (pinfunction "2_2") (pintype "passive"))
      (node (ref "C67") (pin "1") (pinfunction "1_1") (pintype "passive"))
      (node (ref "CR14") (pin "1") (pinfunction "A_1") (pintype "passive"))
      (node (ref "PS4") (pin "16") (pinfunction "-VOUT_16") (pintype "output"))
      (node (ref "R110") (pin "2") (pinfunction "2_2") (pintype "passive"))
      (node (ref "R119") (pin "2") (pinfunction "2_2") (pintype "passive"))
      (node (ref "R36") (pin "1") (pinfunction "1_1") (pintype "passive"))
      (node (ref "R90") (pin "2") (pinfunction "2_2") (pintype "passive"))
      (node (ref "TP24") (pin "1") (pinfunction "1_1") (pintype "passive"))
      (node (ref "TP65") (pin "1") (pinfunction "1_1") (pintype "passive"))
      (node (ref "U14") (pin "4") (pinfunction "GND_4") (pintype "power_in"))
    )
    (net (code "21") (name "GND_High voltage-out") (class "Default")
      (node (ref "L1") (pin "1") (pinfunction "1_1") (pintype "passive"))
      (node (ref "P2") (pin "3") (pinfunction "3_3") (pintype "passive"))
      (node (ref "P2") (pin "4") (pinfunction "4_4") (pintype "passive"))
      (node (ref "R151") (pin "1") (pinfunction "1_1") (pintype "passive"))
      (node (ref "R152") (pin "1") (pinfunction "1_1") (pintype "passive"))
      (node (ref "R154") (pin "2") (pinfunction "2_2") (pintype "passive"))
      (node (ref "R162") (pin "1") (pinfunction "1_1") (pintype "passive"))
      (node (ref "R163") (pin "1") (pinfunction "1_1") (pintype "passive"))
      (node (ref "TP42") (pin "1") (pinfunction "1_1") (pintype "passive"))
      (node (ref "TP74") (pin "1") (pinfunction "1_1") (pintype "passive"))
    )
    (net (code "22") (name "GND_IN") (class "Default")
      (node (ref "C2") (pin "2") (pinfunction "2_2") (pintype "passive"))
      (node (ref "C49") (pin "2") (pinfunction "2_2") (pintype "passive"))
      (node (ref "C52") (pin "2") (pinfunction "2_2") (pintype "passive"))
      (node (ref "C56") (pin "2") (pinfunction "2_2") (pintype "passive"))
      (node (ref "C68") (pin "2") (pinfunction "2_2") (pintype "passive"))
      (node (ref "J1") (pin "2") (pinfunction "2_2") (pintype "passive"))
      (node (ref "PS1") (pin "2") (pinfunction "-VIN_2") (pintype "input"))
      (node (ref "PS1") (pin "3") (pinfunction "-VIN_3") (pintype "input"))
      (node (ref "PS2") (pin "2") (pinfunction "-VIN_2") (pintype "input"))
      (node (ref "PS2") (pin "3") (pinfunction "-VIN_3") (pintype "input"))
      (node (ref "PS3") (pin "2") (pinfunction "-VIN_2") (pintype "input"))
      (node (ref "PS3") (pin "3") (pinfunction "-VIN_3") (pintype "input"))
      (node (ref "PS4") (pin "2") (pinfunction "-VIN_2") (pintype "input"))
      (node (ref "PS4") (pin "3") (pinfunction "-VIN_3") (pintype "input"))
      (node (ref "TP57") (pin "1") (pinfunction "1_1") (pintype "passive"))
      (node (ref "U1") (pin "2") (pinfunction "-In_2") (pintype "passive"))
      (node (ref "U3") (pin "3") (pinfunction "E_3") (pintype "passive"))
    )
    (net (code "23") (name "Gate 1") (class "Default")
      (node (ref "D8") (pin "2") (pinfunction "C_2") (pintype "passive"))
      (node (ref "Q1") (pin "1") (pinfunction "G_1") (pintype "passive"))
      (node (ref "R19") (pin "2") (pinfunction "2_2") (pintype "passive"))
      (node (ref "R33") (pin "2") (pinfunction "2_2") (pintype "passive"))
      (node (ref "R7") (pin "2") (pinfunction "2_2") (pintype "passive"))
      (node (ref "R9") (pin "2") (pinfunction "2_2") (pintype "passive"))
      (node (ref "TP71") (pin "1") (pinfunction "1_1") (pintype "passive"))
    )
    (net (code "24") (name "Gate 2") (class "Default")
      (node (ref "D15") (pin "2") (pinfunction "C_2") (pintype "passive"))
      (node (ref "Q2") (pin "1") (pinfunction "G_1") (pintype "passive"))
      (node (ref "R37") (pin "2") (pinfunction "2_2") (pintype "passive"))
      (node (ref "R41") (pin "2") (pinfunction "2_2") (pintype "passive"))
      (node (ref "R50") (pin "2") (pinfunction "2_2") (pintype "passive"))
      (node (ref "R57") (pin "2") (pinfunction "2_2") (pintype "passive"))
      (node (ref "TP79") (pin "1") (pinfunction "1_1") (pintype "passive"))
    )
    (net (code "25") (name "Gate 3") (class "Default")
      (node (ref "D16") (pin "2") (pinfunction "C_2") (pintype "passive"))
      (node (ref "Q3") (pin "1") (pinfunction "G_1") (pintype "passive"))
      (node (ref "R58") (pin "2") (pinfunction "2_2") (pintype "passive"))
      (node (ref "R67") (pin "2") (pinfunction "2_2") (pintype "passive"))
      (node (ref "R69") (pin "2") (pinfunction "2_2") (pintype "passive"))
      (node (ref "R76") (pin "2") (pinfunction "2_2") (pintype "passive"))
      (node (ref "TP80") (pin "1") (pinfunction "1_1") (pintype "passive"))
    )
    (net (code "26") (name "Gate 4") (class "Default")
      (node (ref "D10") (pin "2") (pinfunction "C_2") (pintype "passive"))
      (node (ref "Q4") (pin "1") (pinfunction "G_1") (pintype "passive"))
      (node (ref "R109") (pin "2") (pinfunction "2_2") (pintype "passive"))
      (node (ref "R34") (pin "2") (pinfunction "2_2") (pintype "passive"))
      (node (ref "R89") (pin "2") (pinfunction "2_2") (pintype "passive"))
      (node (ref "R91") (pin "2") (pinfunction "2_2") (pintype "passive"))
      (node (ref "TP73") (pin "1") (pinfunction "1_1") (pintype "passive"))
    )
    (net (code "27") (name "High side FB") (class "Default")
      (node (ref "C24") (pin "2") (pinfunction "2_2") (pintype "passive"))
      (node (ref "D5") (pin "2") (pinfunction "C_2") (pintype "passive"))
      (node (ref "D6") (pin "2") (pinfunction "C_2") (pintype "passive"))
      (node (ref "F1") (pin "2") (pinfunction "2_2") (pintype "passive"))
      (node (ref "Q1") (pin "2") (pinfunction "C_2") (pintype "passive"))
      (node (ref "Q4") (pin "2") (pinfunction "C_2") (pintype "passive"))
      (node (ref "R142") (pin "1") (pinfunction "1_1") (pintype "passive"))
      (node (ref "R31") (pin "2") (pinfunction "2_2") (pintype "passive"))
      (node (ref "R32") (pin "2") (pinfunction "2_2") (pintype "passive"))
      (node (ref "TP68") (pin "1") (pinfunction "1_1") (pintype "passive"))
    )
    (net (code "28") (name "Input 400V") (class "Default")
      (node (ref "F4") (pin "1") (pinfunction "1_1") (pintype "passive"))
      (node (ref "P3") (pin "1") (pinfunction "1_1") (pintype "passive"))
      (node (ref "P3") (pin "2") (pinfunction "2_2") (pintype "passive"))
      (node (ref "R125") (pin "2") (pinfunction "2_2") (pintype "passive"))
      (node (ref "TP31") (pin "1") (pinfunction "1_1") (pintype "passive"))
    )
    (net (code "29") (name "Input voltage of FB") (class "Default")
      (node (ref "J2") (pin "15") (pinfunction "15_15") (pintype "passive"))
      (node (ref "TP59") (pin "1") (pinfunction "1_1") (pintype "passive"))
    )
    (net (code "30") (name "M1 FB command") (class "Default")
      (node (ref "FB3") (pin "1") (pinfunction "1_1") (pintype "power_in"))
      (node (ref "FB9") (pin "2") (pinfunction "2_2") (pintype "power_in"))
      (node (ref "R105") (pin "1") (pinfunction "1_1") (pintype "passive"))
      (node (ref "R26") (pin "1") (pinfunction "1_1") (pintype "passive"))
      (node (ref "TP3") (pin "1") (pinfunction "1_1") (pintype "passive"))
      (node (ref "TP49") (pin "1") (pinfunction "1_1") (pintype "passive"))
    )
    (net (code "31") (name "M2 FB command") (class "Default")
      (node (ref "FB4") (pin "1") (pinfunction "1_1") (pintype "power_in"))
      (node (ref "FB8") (pin "2") (pinfunction "2_2") (pintype "power_in"))
      (node (ref "R104") (pin "1") (pinfunction "1_1") (pintype "passive"))
      (node (ref "R60") (pin "1") (pinfunction "1_1") (pintype "passive"))
      (node (ref "TP50") (pin "1") (pinfunction "1_1") (pintype "passive"))
      (node (ref "TP9") (pin "1") (pinfunction "1_1") (pintype "passive"))
    )
    (net (code "32") (name "M3 FB command") (class "Default")
      (node (ref "FB5") (pin "1") (pinfunction "1_1") (pintype "power_in"))
      (node (ref "FB7") (pin "2") (pinfunction "2_2") (pintype "power_in"))
      (node (ref "R103") (pin "1") (pinfunction "1_1") (pintype "passive"))
      (node (ref "R82") (pin "1") (pinfunction "1_1") (pintype "passive"))
      (node (ref "TP15") (pin "1") (pinfunction "1_1") (pintype "passive"))
      (node (ref "TP51") (pin "1") (pinfunction "1_1") (pintype "passive"))
    )
    (net (code "33") (name "M4 FB command") (class "Default")
      (node (ref "FB10") (pin "1") (pinfunction "1_1") (pintype "power_in"))
      (node (ref "FB6") (pin "2") (pinfunction "2_2") (pintype "power_in"))
      (node (ref "R102") (pin "1") (pinfunction "1_1") (pintype "passive"))
      (node (ref "R115") (pin "1") (pinfunction "1_1") (pintype "passive"))
      (node (ref "TP21") (pin "1") (pinfunction "1_1") (pintype "passive"))
      (node (ref "TP52") (pin "1") (pinfunction "1_1") (pintype "passive"))
    )
    (net (code "34") (name "Net-(C11-Pad1)") (class "Default")
      (node (ref "C11") (pin "1") (pinfunction "1_1") (pintype "passive"))
      (node (ref "C12") (pin "1") (pinfunction "1_1") (pintype "passive"))
      (node (ref "C13") (pin "1") (pinfunction "1_1") (pintype "passive"))
      (node (ref "R31") (pin "1") (pinfunction "1_1") (pintype "passive"))
    )
    (net (code "35") (name "Net-(C15-Pad1)") (class "Default")
      (node (ref "C15") (pin "1") (pinfunction "1_1") (pintype "passive"))
      (node (ref "C16") (pin "1") (pinfunction "1_1") (pintype "passive"))
      (node (ref "C18") (pin "1") (pinfunction "1_1") (pintype "passive"))
      (node (ref "R32") (pin "1") (pinfunction "1_1") (pintype "passive"))
    )
    (net (code "36") (name "Net-(C22-Pad1)") (class "Default")
      (node (ref "C22") (pin "1") (pinfunction "1_1") (pintype "passive"))
      (node (ref "C25") (pin "1") (pinfunction "1_1") (pintype "passive"))
      (node (ref "F2") (pin "1") (pinfunction "1_1") (pintype "passive"))
    )
    (net (code "37") (name "Net-(C22-Pad2)") (class "Default")
      (node (ref "C22") (pin "2") (pinfunction "2_2") (pintype "passive"))
      (node (ref "C25") (pin "2") (pinfunction "2_2") (pintype "passive"))
      (node (ref "F3") (pin "2") (pinfunction "2_2") (pintype "passive"))
    )
    (net (code "38") (name "Net-(C26-Pad1)") (class "Default")
      (node (ref "C26") (pin "1") (pinfunction "1_1") (pintype "passive"))
      (node (ref "C27") (pin "1") (pinfunction "1_1") (pintype "passive"))
      (node (ref "C28") (pin "1") (pinfunction "1_1") (pintype "passive"))
      (node (ref "R52") (pin "1") (pinfunction "1_1") (pintype "passive"))
    )
    (net (code "39") (name "Net-(C30-Pad1)") (class "Default")
      (node (ref "C30") (pin "1") (pinfunction "1_1") (pintype "passive"))
      (node (ref "C31") (pin "1") (pinfunction "1_1") (pintype "passive"))
      (node (ref "R54") (pin "1") (pinfunction "1_1") (pintype "passive"))
    )
    (net (code "40") (name "Net-(C74-Pad1)") (class "Default")
      (node (ref "C74") (pin "1") (pinfunction "1_1") (pintype "passive"))
      (node (ref "R132") (pin "2") (pinfunction "2_2") (pintype "passive"))
      (node (ref "R133") (pin "1") (pinfunction "1_1") (pintype "passive"))
    )
    (net (code "41") (name "Net-(C74-Pad2)") (class "Default")
      (node (ref "C74") (pin "2") (pinfunction "2_2") (pintype "passive"))
      (node (ref "R129") (pin "2") (pinfunction "2_2") (pintype "passive"))
      (node (ref "R130") (pin "1") (pinfunction "1_1") (pintype "passive"))
    )
    (net (code "42") (name "Net-(C75-Pad2)") (class "Default")
      (node (ref "C75") (pin "2") (pinfunction "2_2") (pintype "passive"))
      (node (ref "FB12") (pin "1") (pinfunction "1_1") (pintype "power_in"))
      (node (ref "R131") (pin "2") (pinfunction "2_2") (pintype "passive"))
      (node (ref "TP36") (pin "1") (pinfunction "1_1") (pintype "passive"))
    )
    (net (code "43") (name "Net-(C81-Pad2)") (class "Default")
      (node (ref "C81") (pin "2") (pinfunction "2_2") (pintype "passive"))
      (node (ref "R153") (pin "2") (pinfunction "2_2") (pintype "passive"))
    )
    (net (code "44") (name "Net-(C88-Pad2)") (class "Default")
      (node (ref "C88") (pin "2") (pinfunction "2_2") (pintype "passive"))
      (node (ref "R173") (pin "2") (pinfunction "2_2") (pintype "passive"))
      (node (ref "R174") (pin "1") (pinfunction "1_1") (pintype "passive"))
    )
    (net (code "45") (name "Net-(CR1-A)") (class "Default")
      (node (ref "CR1") (pin "1") (pinfunction "A_1") (pintype "passive"))
      (node (ref "CR2") (pin "2") (pinfunction "K_2") (pintype "passive"))
      (node (ref "R18") (pin "1") (pinfunction "1_1") (pintype "passive"))
      (node (ref "R30") (pin "2") (pinfunction "2_2") (pintype "passive"))
      (node (ref "TP5") (pin "1") (pinfunction "1_1") (pintype "passive"))
      (node (ref "U5") (pin "5") (pinfunction "VO_5") (pintype "output"))
    )
    (net (code "46") (name "Net-(CR3-K)") (class "Default")
      (node (ref "CR3") (pin "2") (pinfunction "K_2") (pintype "passive"))
      (node (ref "CR4") (pin "1") (pinfunction "A_1") (pintype "passive"))
      (node (ref "D3") (pin "2") (pinfunction "C_2") (pintype "passive"))
      (node (ref "D4") (pin "2") (pinfunction "C_2") (pintype "passive"))
      (node (ref "R13") (pin "1") (pinfunction "1_1") (pintype "passive"))
      (node (ref "R22") (pin "1") (pinfunction "1_1") (pintype "passive"))
      (node (ref "TP7") (pin "1") (pinfunction "1_1") (pintype "passive"))
      (node (ref "U6") (pin "6") (pinfunction "OUT_6") (pintype "output"))
      (node (ref "U6") (pin "7") (pinfunction "OUT_7") (pintype "output"))
    )
    (net (code "47") (name "Net-(CR5-A)") (class "Default")
      (node (ref "CR5") (pin "1") (pinfunction "A_1") (pintype "passive"))
      (node (ref "CR6") (pin "2") (pinfunction "K_2") (pintype "passive"))
      (node (ref "R49") (pin "1") (pinfunction "1_1") (pintype "passive"))
      (node (ref "R64") (pin "2") (pinfunction "2_2") (pintype "passive"))
      (node (ref "TP11") (pin "1") (pinfunction "1_1") (pintype "passive"))
      (node (ref "U8") (pin "5") (pinfunction "VO_5") (pintype "output"))
    )
    (net (code "48") (name "Net-(CR7-K)") (class "Default")
      (node (ref "CR7") (pin "2") (pinfunction "K_2") (pintype "passive"))
      (node (ref "CR8") (pin "1") (pinfunction "A_1") (pintype "passive"))
      (node (ref "D11") (pin "2") (pinfunction "C_2") (pintype "passive"))
      (node (ref "D12") (pin "2") (pinfunction "C_2") (pintype "passive"))
      (node (ref "R46") (pin "1") (pinfunction "1_1") (pintype "passive"))
      (node (ref "R55") (pin "1") (pinfunction "1_1") (pintype "passive"))
      (node (ref "TP13") (pin "1") (pinfunction "1_1") (pintype "passive"))
      (node (ref "U9") (pin "6") (pinfunction "OUT_6") (pintype "output"))
      (node (ref "U9") (pin "7") (pinfunction "OUT_7") (pintype "output"))
    )
    (net (code "49") (name "Net-(CR10-K)") (class "Default")
      (node (ref "CR10") (pin "2") (pinfunction "K_2") (pintype "passive"))
      (node (ref "CR9") (pin "1") (pinfunction "A_1") (pintype "passive"))
      (node (ref "R75") (pin "1") (pinfunction "1_1") (pintype "passive"))
      (node (ref "R86") (pin "2") (pinfunction "2_2") (pintype "passive"))
      (node (ref "TP17") (pin "1") (pinfunction "1_1") (pintype "passive"))
      (node (ref "U11") (pin "5") (pinfunction "VO_5") (pintype "output"))
    )
    (net (code "50") (name "Net-(CR11-K)") (class "Default")
      (node (ref "CR11") (pin "2") (pinfunction "K_2") (pintype "passive"))
      (node (ref "CR12") (pin "1") (pinfunction "A_1") (pintype "passive"))
      (node (ref "D19") (pin "2") (pinfunction "C_2") (pintype "passive"))
      (node (ref "D20") (pin "2") (pinfunction "C_2") (pintype "passive"))
      (node (ref "R72") (pin "1") (pinfunction "1_1") (pintype "passive"))
      (node (ref "R79") (pin "1") (pinfunction "1_1") (pintype "passive"))
      (node (ref "TP19") (pin "1") (pinfunction "1_1") (pintype "passive"))
      (node (ref "U12") (pin "6") (pinfunction "OUT_6") (pintype "output"))
      (node (ref "U12") (pin "7") (pinfunction "OUT_7") (pintype "output"))
    )
    (net (code "51") (name "Net-(CR13-A)") (class "Default")
      (node (ref "CR13") (pin "1") (pinfunction "A_1") (pintype "passive"))
      (node (ref "CR14") (pin "2") (pinfunction "K_2") (pintype "passive"))
      (node (ref "R108") (pin "1") (pinfunction "1_1") (pintype "passive"))
      (node (ref "R120") (pin "2") (pinfunction "2_2") (pintype "passive"))
      (node (ref "TP23") (pin "1") (pinfunction "1_1") (pintype "passive"))
      (node (ref "U14") (pin "5") (pinfunction "VO_5") (pintype "output"))
    )
    (net (code "52") (name "Net-(CR15-K)") (class "Default")
      (node (ref "CR15") (pin "2") (pinfunction "K_2") (pintype "passive"))
      (node (ref "CR16") (pin "1") (pinfunction "A_1") (pintype "passive"))
      (node (ref "D21") (pin "2") (pinfunction "C_2") (pintype "passive"))
      (node (ref "D22") (pin "2") (pinfunction "C_2") (pintype "passive"))
      (node (ref "R112") (pin "1") (pinfunction "1_1") (pintype "passive"))
      (node (ref "R97") (pin "1") (pinfunction "1_1") (pintype "passive"))
      (node (ref "TP27") (pin "1") (pinfunction "1_1") (pintype "passive"))
      (node (ref "U15") (pin "6") (pinfunction "OUT_6") (pintype "output"))
      (node (ref "U15") (pin "7") (pinfunction "OUT_7") (pintype "output"))
    )
    (net (code "53") (name "Net-(CR17-K)") (class "Default")
      (node (ref "CR17") (pin "2") (pinfunction "K_2") (pintype "passive"))
      (node (ref "CR18") (pin "2") (pinfunction "K_2") (pintype "passive"))
    )
    (net (code "54") (name "Net-(CR18-A)") (class "Default")
      (node (ref "C21") (pin "2") (pinfunction "2_2") (pintype "passive"))
      (node (ref "CR18") (pin "1") (pinfunction "A_1") (pintype "passive"))
      (node (ref "F1") (pin "1") (pinfunction "1_1") (pintype "passive"))
      (node (ref "F4") (pin "2") (pinfunction "2_2") (pintype "passive"))
      (node (ref "R38") (pin "1") (pinfunction "1_1") (pintype "passive"))
      (node (ref "R39") (pin "1") (pinfunction "1_1") (pintype "passive"))
    )
    (net (code "55") (name "Net-(D1-K)") (class "Default")
      (node (ref "D1") (pin "2") (pinfunction "K_2") (pintype "passive"))
      (node (ref "D2") (pin "2") (pinfunction "K_2") (pintype "passive"))
    )
    (net (code "56") (name "Net-(D3-A)") (class "Default")
      (node (ref "D3") (pin "1") (pinfunction "A_1") (pintype "passive"))
      (node (ref "D4") (pin "1") (pinfunction "A_1") (pintype "passive"))
      (node (ref "R7") (pin "1") (pinfunction "1_1") (pintype "passive"))
      (node (ref "R9") (pin "1") (pinfunction "1_1") (pintype "passive"))
    )
    (net (code "57") (name "Net-(D11-A)") (class "Default")
      (node (ref "D11") (pin "1") (pinfunction "A_1") (pintype "passive"))
      (node (ref "D12") (pin "1") (pinfunction "A_1") (pintype "passive"))
      (node (ref "R37") (pin "1") (pinfunction "1_1") (pintype "passive"))
      (node (ref "R41") (pin "1") (pinfunction "1_1") (pintype "passive"))
    )
    (net (code "58") (name "Net-(D19-A)") (class "Default")
      (node (ref "D19") (pin "1") (pinfunction "A_1") (pintype "passive"))
      (node (ref "D20") (pin "1") (pinfunction "A_1") (pintype "passive"))
      (node (ref "R67") (pin "1") (pinfunction "1_1") (pintype "passive"))
      (node (ref "R69") (pin "1") (pinfunction "1_1") (pintype "passive"))
    )
    (net (code "59") (name "Net-(D21-A)") (class "Default")
      (node (ref "D21") (pin "1") (pinfunction "A_1") (pintype "passive"))
      (node (ref "D22") (pin "1") (pinfunction "A_1") (pintype "passive"))
      (node (ref "R89") (pin "1") (pinfunction "1_1") (pintype "passive"))
      (node (ref "R91") (pin "1") (pinfunction "1_1") (pintype "passive"))
    )
    (net (code "60") (name "Net-(DS1-K)") (class "Default")
      (node (ref "DS1") (pin "2") (pinfunction "K_2") (pintype "passive"))
      (node (ref "R1") (pin "1") (pinfunction "1_1") (pintype "passive"))
    )
    (net (code "61") (name "Net-(DS2-A)") (class "Default")
      (node (ref "DS2") (pin "1") (pinfunction "A_1") (pintype "passive"))
      (node (ref "R5") (pin "1") (pinfunction "1_1") (pintype "passive"))
      (node (ref "TP1") (pin "1") (pinfunction "1_1") (pintype "passive"))
      (node (ref "U2") (pin "4") (pinfunction "Y_4") (pintype "output"))
    )
    (net (code "62") (name "Net-(DS2-K)") (class "Default")
      (node (ref "DS2") (pin "2") (pinfunction "K_2") (pintype "passive"))
      (node (ref "R10") (pin "1") (pinfunction "1_1") (pintype "passive"))
    )
    (net (code "63") (name "Net-(DS3-A)") (class "Default")
      (node (ref "DS3") (pin "1") (pinfunction "A_1") (pintype "passive"))
      (node (ref "R17") (pin "1") (pinfunction "1_1") (pintype "passive"))
      (node (ref "TP4") (pin "1") (pinfunction "1_1") (pintype "passive"))
      (node (ref "U4") (pin "4") (pinfunction "Y_4") (pintype "output"))
    )
    (net (code "64") (name "Net-(DS3-K)") (class "Default")
      (node (ref "DS3") (pin "2") (pinfunction "K_2") (pintype "passive"))
      (node (ref "R28") (pin "1") (pinfunction "1_1") (pintype "passive"))
    )
    (net (code "65") (name "Net-(DS4-A)") (class "Default")
      (node (ref "DS4") (pin "1") (pinfunction "A_1") (pintype "passive"))
      (node (ref "R48") (pin "1") (pinfunction "1_1") (pintype "passive"))
      (node (ref "TP10") (pin "1") (pinfunction "1_1") (pintype "passive"))
      (node (ref "U7") (pin "4") (pinfunction "Y_4") (pintype "output"))
    )
    (net (code "66") (name "Net-(DS4-K)") (class "Default")
      (node (ref "DS4") (pin "2") (pinfunction "K_2") (pintype "passive"))
      (node (ref "R62") (pin "1") (pinfunction "1_1") (pintype "passive"))
    )
    (net (code "67") (name "Net-(DS5-A)") (class "Default")
      (node (ref "DS5") (pin "1") (pinfunction "A_1") (pintype "passive"))
      (node (ref "R74") (pin "1") (pinfunction "1_1") (pintype "passive"))
      (node (ref "TP16") (pin "1") (pinfunction "1_1") (pintype "passive"))
      (node (ref "U10") (pin "4") (pinfunction "Y_4") (pintype "output"))
    )
    (net (code "68") (name "Net-(DS5-K)") (class "Default")
      (node (ref "DS5") (pin "2") (pinfunction "K_2") (pintype "passive"))
      (node (ref "R84") (pin "1") (pinfunction "1_1") (pintype "passive"))
    )
    (net (code "69") (name "Net-(DS6-K)") (class "Default")
      (node (ref "DS6") (pin "2") (pinfunction "K_2") (pintype "passive"))
      (node (ref "R87") (pin "1") (pinfunction "1_1") (pintype "passive"))
    )
    (net (code "70") (name "Net-(DS7-K)") (class "Default")
      (node (ref "DS7") (pin "2") (pinfunction "K_2") (pintype "passive"))
      (node (ref "R88") (pin "1") (pinfunction "1_1") (pintype "passive"))
    )
    (net (code "71") (name "Net-(DS8-K)") (class "Default")
      (node (ref "DS8") (pin "2") (pinfunction "K_2") (pintype "passive"))
      (node (ref "R94") (pin "1") (pinfunction "1_1") (pintype "passive"))
    )
    (net (code "72") (name "Net-(DS9-A)") (class "Default")
      (node (ref "DS9") (pin "1") (pinfunction "A_1") (pintype "passive"))
      (node (ref "R107") (pin "1") (pinfunction "1_1") (pintype "passive"))
      (node (ref "TP22") (pin "1") (pinfunction "1_1") (pintype "passive"))
      (node (ref "U13") (pin "4") (pinfunction "Y_4") (pintype "output"))
    )
    (net (code "73") (name "Net-(DS9-K)") (class "Default")
      (node (ref "DS9") (pin "2") (pinfunction "K_2") (pintype "passive"))
      (node (ref "R117") (pin "1") (pinfunction "1_1") (pintype "passive"))
    )
    (net (code "74") (name "Net-(DS10-K)") (class "Default")
      (node (ref "DS10") (pin "2") (pinfunction "K_2") (pintype "passive"))
      (node (ref "R121") (pin "1") (pinfunction "1_1") (pintype "passive"))
    )
    (net (code "75") (name "Net-(DS11-K)") (class "Default")
      (node (ref "DS11") (pin "2") (pinfunction "K_2") (pintype "passive"))
      (node (ref "R119") (pin "1") (pinfunction "1_1") (pintype "passive"))
    )
    (net (code "76") (name "Net-(DS12-K)") (class "Default")
      (node (ref "DS12") (pin "2") (pinfunction "K_2") (pintype "passive"))
      (node (ref "R122") (pin "1") (pinfunction "1_1") (pintype "passive"))
    )
    (net (code "77") (name "Net-(F3-Pad1)") (class "Default")
      (node (ref "F3") (pin "1") (pinfunction "1_1") (pintype "passive"))
      (node (ref "U17") (pin "10") (pinfunction "OUT_10") (pintype "passive"))
      (node (ref "U17") (pin "8") (pinfunction "OUT_8") (pintype "passive"))
      (node (ref "U17") (pin "9") (pinfunction "OUT_9") (pintype "passive"))
    )
    (net (code "78") (name "Net-(FB1-Pad2)") (class "Default")
      (node (ref "FB1") (pin "2") (pinfunction "2_2") (pintype "power_in"))
      (node (ref "R4") (pin "1") (pinfunction "1_1") (pintype "passive"))
    )
    (net (code "79") (name "Net-(FB2-Pad1)") (class "Default")
      (node (ref "FB2") (pin "1") (pinfunction "1_1") (pintype "power_in"))
      (node (ref "P1") (pin "4") (pinfunction "4_4") (pintype "passive"))
      (node (ref "R24") (pin "1") (pinfunction "1_1") (pintype "passive"))
    )
    (net (code "80") (name "Net-(FB3-Pad2)") (class "Default")
      (node (ref "FB3") (pin "2") (pinfunction "2_2") (pintype "power_in"))
      (node (ref "R16") (pin "1") (pinfunction "1_1") (pintype "passive"))
      (node (ref "R27") (pin "1") (pinfunction "1_1") (pintype "passive"))
    )
    (net (code "81") (name "Net-(FB4-Pad2)") (class "Default")
      (node (ref "FB4") (pin "2") (pinfunction "2_2") (pintype "power_in"))
      (node (ref "R47") (pin "1") (pinfunction "1_1") (pintype "passive"))
      (node (ref "R61") (pin "1") (pinfunction "1_1") (pintype "passive"))
    )
    (net (code "82") (name "Net-(FB5-Pad2)") (class "Default")
      (node (ref "FB5") (pin "2") (pinfunction "2_2") (pintype "power_in"))
      (node (ref "R73") (pin "1") (pinfunction "1_1") (pintype "passive"))
      (node (ref "R83") (pin "1") (pinfunction "1_1") (pintype "passive"))
    )
    (net (code "83") (name "Net-(FB6-Pad1)") (class "Default")
      (node (ref "FB6") (pin "1") (pinfunction "1_1") (pintype "power_in"))
      (node (ref "J2") (pin "21") (pinfunction "21_21") (pintype "passive"))
      (node (ref "R98") (pin "1") (pinfunction "1_1") (pintype "passive"))
    )
    (net (code "84") (name "Net-(FB7-Pad1)") (class "Default")
      (node (ref "FB7") (pin "1") (pinfunction "1_1") (pintype "power_in"))
      (node (ref "J2") (pin "9") (pinfunction "9_9") (pintype "passive"))
      (node (ref "R99") (pin "1") (pinfunction "1_1") (pintype "passive"))
    )
    (net (code "85") (name "Net-(FB8-Pad1)") (class "Default")
      (node (ref "FB8") (pin "1") (pinfunction "1_1") (pintype "power_in"))
      (node (ref "J2") (pin "22") (pinfunction "22_22") (pintype "passive"))
      (node (ref "R100") (pin "1") (pinfunction "1_1") (pintype "passive"))
    )
    (net (code "86") (name "Net-(FB9-Pad1)") (class "Default")
      (node (ref "FB9") (pin "1") (pinfunction "1_1") (pintype "power_in"))
      (node (ref "J2") (pin "10") (pinfunction "10_10") (pintype "passive"))
      (node (ref "R101") (pin "1") (pinfunction "1_1") (pintype "passive"))
    )
    (net (code "87") (name "Net-(FB10-Pad2)") (class "Default")
      (node (ref "FB10") (pin "2") (pinfunction "2_2") (pintype "power_in"))
      (node (ref "R106") (pin "1") (pinfunction "1_1") (pintype "passive"))
      (node (ref "R116") (pin "1") (pinfunction "1_1") (pintype "passive"))
    )
    (net (code "88") (name "Net-(FB13-Pad1)") (class "Default")
      (node (ref "FB13") (pin "1") (pinfunction "1_1") (pintype "power_in"))
      (node (ref "R174") (pin "2") (pinfunction "2_2") (pintype "passive"))
      (node (ref "R175") (pin "1") (pinfunction "1_1") (pintype "passive"))
    )
    (net (code "89") (name "Net-(P1-Pad3)") (class "Default")
      (node (ref "P1") (pin "3") (pinfunction "3_3") (pintype "passive"))
      (node (ref "R14") (pin "2") (pinfunction "2_2") (pintype "passive"))
      (node (ref "R15") (pin "2") (pinfunction "2_2") (pintype "passive"))
    )
    (net (code "90") (name "Net-(Q5-GND1)") (class "Default")
      (node (ref "C84") (pin "2") (pinfunction "2_2") (pintype "passive"))
      (node (ref "C85") (pin "2") (pinfunction "2_2") (pintype "passive"))
      (node (ref "Q5") (pin "4") (pinfunction "GND1_4") (pintype "power_in"))
      (node (ref "R154") (pin "1") (pinfunction "1_1") (pintype "passive"))
      (node (ref "R162") (pin "2") (pinfunction "2_2") (pintype "passive"))
      (node (ref "R168") (pin "1") (pinfunction "1_1") (pintype "passive"))
      (node (ref "TP46") (pin "1") (pinfunction "1_1") (pintype "passive"))
    )
    (net (code "91") (name "Net-(Q5-SHDN)") (class "Default")
      (node (ref "Q5") (pin "3") (pinfunction "SHDN_3") (pintype "input"))
      (node (ref "R163") (pin "2") (pinfunction "2_2") (pintype "passive"))
      (node (ref "R167") (pin "1") (pinfunction "1_1") (pintype "passive"))
    )
    (net (code "92") (name "Net-(Q5-VDD2)") (class "Default")
      (node (ref "C82") (pin "1") (pinfunction "1_1") (pintype "passive"))
      (node (ref "C83") (pin "1") (pinfunction "1_1") (pintype "passive"))
      (node (ref "Q5") (pin "8") (pinfunction "VDD2_8") (pintype "power_in"))
      (node (ref "R149") (pin "1") (pinfunction "1_1") (pintype "passive"))
      (node (ref "R150") (pin "1") (pinfunction "1_1") (pintype "passive"))
    )
    (net (code "93") (name "Net-(Q5-VIN)") (class "Default")
      (node (ref "C84") (pin "1") (pinfunction "1_1") (pintype "passive"))
      (node (ref "Q5") (pin "2") (pinfunction "VIN_2") (pintype "power_in"))
      (node (ref "R147") (pin "1") (pinfunction "1_1") (pintype "passive"))
      (node (ref "R148") (pin "1") (pinfunction "1_1") (pintype "passive"))
      (node (ref "R151") (pin "2") (pinfunction "2_2") (pintype "passive"))
      (node (ref "R152") (pin "2") (pinfunction "2_2") (pintype "passive"))
      (node (ref "TP41") (pin "1") (pinfunction "1_1") (pintype "passive"))
    )
    (net (code "94") (name "Net-(Q5-VOUT+)") (class "Default")
      (node (ref "Q5") (pin "7") (pinfunction "VOUT+_7") (pintype "passive"))
      (node (ref "R153") (pin "1") (pinfunction "1_1") (pintype "passive"))
      (node (ref "R157") (pin "2") (pinfunction "2_2") (pintype "passive"))
      (node (ref "TP43") (pin "1") (pinfunction "1_1") (pintype "passive"))
    )
    (net (code "95") (name "Net-(Q5-VOUT-)") (class "Default")
      (node (ref "C81") (pin "1") (pinfunction "1_1") (pintype "passive"))
      (node (ref "Q5") (pin "6") (pinfunction "VOUT-_6") (pintype "passive"))
      (node (ref "R158") (pin "2") (pinfunction "2_2") (pintype "passive"))
      (node (ref "R159") (pin "1") (pinfunction "1_1") (pintype "passive"))
      (node (ref "TP44") (pin "1") (pinfunction "1_1") (pintype "passive"))
    )
    (net (code "96") (name "Net-(R13-Pad2)") (class "Default")
      (node (ref "R13") (pin "2") (pinfunction "2_2") (pintype "passive"))
      (node (ref "R19") (pin "1") (pinfunction "1_1") (pintype "passive"))
      (node (ref "R22") (pin "2") (pinfunction "2_2") (pintype "passive"))
    )
    (net (code "97") (name "Net-(R38-Pad2)") (class "Default")
      (node (ref "R38") (pin "2") (pinfunction "2_2") (pintype "passive"))
      (node (ref "R42") (pin "1") (pinfunction "1_1") (pintype "passive"))
    )
    (net (code "98") (name "Net-(R39-Pad2)") (class "Default")
      (node (ref "R39") (pin "2") (pinfunction "2_2") (pintype "passive"))
      (node (ref "R43") (pin "1") (pinfunction "1_1") (pintype "passive"))
    )
    (net (code "99") (name "Net-(R46-Pad2)") (class "Default")
      (node (ref "R46") (pin "2") (pinfunction "2_2") (pintype "passive"))
      (node (ref "R50") (pin "1") (pinfunction "1_1") (pintype "passive"))
      (node (ref "R55") (pin "2") (pinfunction "2_2") (pintype "passive"))
    )
    (net (code "100") (name "Net-(R72-Pad2)") (class "Default")
      (node (ref "R72") (pin "2") (pinfunction "2_2") (pintype "passive"))
      (node (ref "R76") (pin "1") (pinfunction "1_1") (pintype "passive"))
      (node (ref "R79") (pin "2") (pinfunction "2_2") (pintype "passive"))
    )
    (net (code "101") (name "Net-(R109-Pad1)") (class "Default")
      (node (ref "R109") (pin "1") (pinfunction "1_1") (pintype "passive"))
      (node (ref "R112") (pin "2") (pinfunction "2_2") (pintype "passive"))
      (node (ref "R97") (pin "2") (pinfunction "2_2") (pintype "passive"))
    )
    (net (code "102") (name "Net-(R123-Pad1)") (class "Default")
      (node (ref "R123") (pin "1") (pinfunction "1_1") (pintype "passive"))
      (node (ref "R124") (pin "2") (pinfunction "2_2") (pintype "passive"))
      (node (ref "R132") (pin "1") (pinfunction "1_1") (pintype "passive"))
      (node (ref "TP30") (pin "1") (pinfunction "1_1") (pintype "passive"))
    )
    (net (code "103") (name "Net-(R123-Pad2)") (class "Default")
      (node (ref "R123") (pin "2") (pinfunction "2_2") (pintype "passive"))
      (node (ref "U17") (pin "11") (pinfunction "OUT_11") (pintype "passive"))
    )
    (net (code "104") (name "Net-(R126-Pad2)") (class "Default")
      (node (ref "R126") (pin "2") (pinfunction "2_2") (pintype "passive"))
      (node (ref "R127") (pin "1") (pinfunction "1_1") (pintype "passive"))
    )
    (net (code "105") (name "Net-(R141-Pad2)") (class "Default")
      (node (ref "R141") (pin "2") (pinfunction "2_2") (pintype "passive"))
      (node (ref "R142") (pin "2") (pinfunction "2_2") (pintype "passive"))
      (node (ref "R147") (pin "2") (pinfunction "2_2") (pintype "passive"))
      (node (ref "R148") (pin "2") (pinfunction "2_2") (pintype "passive"))
      (node (ref "TP40") (pin "1") (pinfunction "1_1") (pintype "passive"))
    )
    (net (code "106") (name "Net-(R155-Pad1)") (class "Default")
      (node (ref "R155") (pin "1") (pinfunction "1_1") (pintype "passive"))
      (node (ref "R156") (pin "2") (pinfunction "2_2") (pintype "passive"))
    )
    (net (code "107") (name "Net-(R156-Pad1)") (class "Default")
      (node (ref "R156") (pin "1") (pinfunction "1_1") (pintype "passive"))
      (node (ref "R160") (pin "1") (pinfunction "1_1") (pintype "passive"))
      (node (ref "R161") (pin "1") (pinfunction "1_1") (pintype "passive"))
    )
    (net (code "108") (name "Net-(R161-Pad2)") (class "Default")
      (node (ref "R161") (pin "2") (pinfunction "2_2") (pintype "passive"))
      (node (ref "R166") (pin "1") (pinfunction "1_1") (pintype "passive"))
      (node (ref "R171") (pin "2") (pinfunction "2_2") (pintype "passive"))
      (node (ref "R172") (pin "1") (pinfunction "1_1") (pintype "passive"))
    )
    (net (code "109") (name "Net-(R165-Pad1)") (class "Default")
      (node (ref "R165") (pin "1") (pinfunction "1_1") (pintype "passive"))
      (node (ref "R166") (pin "2") (pinfunction "2_2") (pintype "passive"))
    )
    (net (code "110") (name "Net-(U1-on{slash}off)") (class "Default")
      (node (ref "U1") (pin "6") (pinfunction "on/off_6") (pintype "passive"))
      (node (ref "U3") (pin "4") (pinfunction "C_4") (pintype "passive"))
    )
    (net (code "111") (name "Net-(U2-A)") (class "Default")
      (node (ref "R4") (pin "2") (pinfunction "2_2") (pintype "passive"))
      (node (ref "U2") (pin "2") (pinfunction "A_2") (pintype "input"))
    )
    (net (code "112") (name "Net-(U2-NC)") (class "Default")
      (node (ref "R6") (pin "2") (pinfunction "2_2") (pintype "passive"))
      (node (ref "U2") (pin "1") (pinfunction "NC_1") (pintype "passive"))
    )
    (net (code "113") (name "Net-(U2-VCC)") (class "Default")
      (node (ref "C1") (pin "1") (pinfunction "1_1") (pintype "passive"))
      (node (ref "R2") (pin "1") (pinfunction "1_1") (pintype "passive"))
      (node (ref "R3") (pin "2") (pinfunction "2_2") (pintype "passive"))
      (node (ref "U2") (pin "5") (pinfunction "VCC_5") (pintype "power_in"))
    )
    (net (code "114") (name "Net-(U3-A)") (class "Default")
      (node (ref "R5") (pin "2") (pinfunction "2_2") (pintype "passive"))
      (node (ref "U3") (pin "1") (pinfunction "A_1") (pintype "passive"))
    )
    (net (code "115") (name "Net-(U4-A)") (class "Default")
      (node (ref "R16") (pin "2") (pinfunction "2_2") (pintype "passive"))
      (node (ref "U4") (pin "2") (pinfunction "A_2") (pintype "input"))
    )
    (net (code "116") (name "Net-(U4-NC)") (class "Default")
      (node (ref "R21") (pin "2") (pinfunction "2_2") (pintype "passive"))
      (node (ref "U4") (pin "1") (pinfunction "NC_1") (pintype "passive"))
    )
    (net (code "117") (name "Net-(U4-VCC)") (class "Default")
      (node (ref "C5") (pin "1") (pinfunction "1_1") (pintype "passive"))
      (node (ref "R11") (pin "1") (pinfunction "1_1") (pintype "passive"))
      (node (ref "R12") (pin "2") (pinfunction "2_2") (pintype "passive"))
      (node (ref "U4") (pin "5") (pinfunction "VCC_5") (pintype "power_in"))
    )
    (net (code "118") (name "Net-(U5-ANODE)") (class "Default")
      (node (ref "R17") (pin "2") (pinfunction "2_2") (pintype "passive"))
      (node (ref "R23") (pin "1") (pinfunction "1_1") (pintype "passive"))
      (node (ref "U5") (pin "1") (pinfunction "ANODE_1") (pintype "passive"))
    )
    (net (code "119") (name "Net-(U5-NC)") (class "Default")
      (node (ref "R25") (pin "2") (pinfunction "2_2") (pintype "passive"))
      (node (ref "U5") (pin "2") (pinfunction "NC_2") (pintype "passive"))
    )
    (net (code "120") (name "Net-(U6-IN)") (class "Default")
      (node (ref "R18") (pin "2") (pinfunction "2_2") (pintype "passive"))
      (node (ref "U6") (pin "2") (pinfunction "IN_2") (pintype "input"))
    )
    (net (code "121") (name "Net-(U6-NC)") (class "Default")
      (node (ref "R29") (pin "2") (pinfunction "2_2") (pintype "passive"))
      (node (ref "U6") (pin "3") (pinfunction "NC_3") (pintype "passive"))
    )
    (net (code "122") (name "Net-(U7-A)") (class "Default")
      (node (ref "R47") (pin "2") (pinfunction "2_2") (pintype "passive"))
      (node (ref "U7") (pin "2") (pinfunction "A_2") (pintype "input"))
    )
    (net (code "123") (name "Net-(U7-NC)") (class "Default")
      (node (ref "R53") (pin "2") (pinfunction "2_2") (pintype "passive"))
      (node (ref "U7") (pin "1") (pinfunction "NC_1") (pintype "passive"))
    )
    (net (code "124") (name "Net-(U7-VCC)") (class "Default")
      (node (ref "C20") (pin "1") (pinfunction "1_1") (pintype "passive"))
      (node (ref "R44") (pin "1") (pinfunction "1_1") (pintype "passive"))
      (node (ref "R45") (pin "2") (pinfunction "2_2") (pintype "passive"))
      (node (ref "U7") (pin "5") (pinfunction "VCC_5") (pintype "power_in"))
    )
    (net (code "125") (name "Net-(U8-ANODE)") (class "Default")
      (node (ref "R48") (pin "2") (pinfunction "2_2") (pintype "passive"))
      (node (ref "R56") (pin "1") (pinfunction "1_1") (pintype "passive"))
      (node (ref "U8") (pin "1") (pinfunction "ANODE_1") (pintype "passive"))
    )
    (net (code "126") (name "Net-(U8-NC)") (class "Default")
      (node (ref "R59") (pin "2") (pinfunction "2_2") (pintype "passive"))
      (node (ref "U8") (pin "2") (pinfunction "NC_2") (pintype "passive"))
    )
    (net (code "127") (name "Net-(U9-IN)") (class "Default")
      (node (ref "R49") (pin "2") (pinfunction "2_2") (pintype "passive"))
      (node (ref "U9") (pin "2") (pinfunction "IN_2") (pintype "input"))
    )
    (net (code "128") (name "Net-(U9-NC)") (class "Default")
      (node (ref "R63") (pin "2") (pinfunction "2_2") (pintype "passive"))
      (node (ref "U9") (pin "3") (pinfunction "NC_3") (pintype "passive"))
    )
    (net (code "129") (name "Net-(U10-A)") (class "Default")
      (node (ref "R73") (pin "2") (pinfunction "2_2") (pintype "passive"))
      (node (ref "U10") (pin "2") (pinfunction "A_2") (pintype "input"))
    )
    (net (code "130") (name "Net-(U10-NC)") (class "Default")
      (node (ref "R78") (pin "2") (pinfunction "2_2") (pintype "passive"))
      (node (ref "U10") (pin "1") (pinfunction "NC_1") (pintype "passive"))
    )
    (net (code "131") (name "Net-(U10-VCC)") (class "Default")
      (node (ref "C41") (pin "1") (pinfunction "1_1") (pintype "passive"))
      (node (ref "R70") (pin "1") (pinfunction "1_1") (pintype "passive"))
      (node (ref "R71") (pin "2") (pinfunction "2_2") (pintype "passive"))
      (node (ref "U10") (pin "5") (pinfunction "VCC_5") (pintype "power_in"))
    )
    (net (code "132") (name "Net-(U11-ANODE)") (class "Default")
      (node (ref "R74") (pin "2") (pinfunction "2_2") (pintype "passive"))
      (node (ref "R80") (pin "1") (pinfunction "1_1") (pintype "passive"))
      (node (ref "U11") (pin "1") (pinfunction "ANODE_1") (pintype "passive"))
    )
    (net (code "133") (name "Net-(U11-NC)") (class "Default")
      (node (ref "R81") (pin "2") (pinfunction "2_2") (pintype "passive"))
      (node (ref "U11") (pin "2") (pinfunction "NC_2") (pintype "passive"))
    )
    (net (code "134") (name "Net-(U12-IN)") (class "Default")
      (node (ref "R75") (pin "2") (pinfunction "2_2") (pintype "passive"))
      (node (ref "U12") (pin "2") (pinfunction "IN_2") (pintype "input"))
    )
    (net (code "135") (name "Net-(U12-NC)") (class "Default")
      (node (ref "R85") (pin "2") (pinfunction "2_2") (pintype "passive"))
      (node (ref "U12") (pin "3") (pinfunction "NC_3") (pintype "passive"))
    )
    (net (code "136") (name "Net-(U13-A)") (class "Default")
      (node (ref "R106") (pin "2") (pinfunction "2_2") (pintype "passive"))
      (node (ref "U13") (pin "2") (pinfunction "A_2") (pintype "input"))
    )
    (net (code "137") (name "Net-(U13-NC)") (class "Default")
      (node (ref "R111") (pin "2") (pinfunction "2_2") (pintype "passive"))
      (node (ref "U13") (pin "1") (pinfunction "NC_1") (pintype "passive"))
    )
    (net (code "138") (name "Net-(U13-VCC)") (class "Default")
      (node (ref "C53") (pin "1") (pinfunction "1_1") (pintype "passive"))
      (node (ref "R95") (pin "1") (pinfunction "1_1") (pintype "passive"))
      (node (ref "R96") (pin "2") (pinfunction "2_2") (pintype "passive"))
      (node (ref "U13") (pin "5") (pinfunction "VCC_5") (pintype "power_in"))
    )
    (net (code "139") (name "Net-(U14-ANODE)") (class "Default")
      (node (ref "R107") (pin "2") (pinfunction "2_2") (pintype "passive"))
      (node (ref "R113") (pin "1") (pinfunction "1_1") (pintype "passive"))
      (node (ref "U14") (pin "1") (pinfunction "ANODE_1") (pintype "passive"))
    )
    (net (code "140") (name "Net-(U14-NC)") (class "Default")
      (node (ref "R114") (pin "2") (pinfunction "2_2") (pintype "passive"))
      (node (ref "U14") (pin "2") (pinfunction "NC_2") (pintype "passive"))
    )
    (net (code "141") (name "Net-(U15-IN)") (class "Default")
      (node (ref "R108") (pin "2") (pinfunction "2_2") (pintype "passive"))
      (node (ref "U15") (pin "2") (pinfunction "IN_2") (pintype "input"))
    )
    (net (code "142") (name "Net-(U15-NC)") (class "Default")
      (node (ref "R118") (pin "2") (pinfunction "2_2") (pintype "passive"))
      (node (ref "U15") (pin "3") (pinfunction "NC_3") (pintype "passive"))
    )
    (net (code "143") (name "Net-(U16-IN)") (class "Default")
      (node (ref "C62") (pin "2") (pinfunction "2_2") (pintype "passive"))
      (node (ref "C63") (pin "2") (pinfunction "2_2") (pintype "passive"))
      (node (ref "FB11") (pin "2") (pinfunction "2_2") (pintype "power_in"))
      (node (ref "U16") (pin "1") (pinfunction "~{SHDN}_1") (pintype "input"))
      (node (ref "U16") (pin "2") (pinfunction "IN_2") (pintype "power_in"))
    )
    (net (code "144") (name "Net-(U19-IN+)") (class "Default")
      (node (ref "C77") (pin "2") (pinfunction "2_2") (pintype "passive"))
      (node (ref "R133") (pin "2") (pinfunction "2_2") (pintype "passive"))
      (node (ref "R136") (pin "2") (pinfunction "2_2") (pintype "passive"))
      (node (ref "TP37") (pin "1") (pinfunction "1_1") (pintype "passive"))
      (node (ref "U19") (pin "3") (pinfunction "IN+_3") (pintype "input"))
    )
    (net (code "145") (name "Net-(U19-IN-)") (class "Default")
      (node (ref "C70") (pin "2") (pinfunction "2_2") (pintype "passive"))
      (node (ref "R126") (pin "1") (pinfunction "1_1") (pintype "passive"))
      (node (ref "R130") (pin "2") (pinfunction "2_2") (pintype "passive"))
      (node (ref "TP34") (pin "1") (pinfunction "1_1") (pintype "passive"))
      (node (ref "U19") (pin "4") (pinfunction "IN-_4") (pintype "input"))
    )
    (net (code "146") (name "Net-(U19-OUT)") (class "Default")
      (node (ref "C70") (pin "1") (pinfunction "1_1") (pintype "passive"))
      (node (ref "R127") (pin "2") (pinfunction "2_2") (pintype "passive"))
      (node (ref "R131") (pin "1") (pinfunction "1_1") (pintype "passive"))
      (node (ref "U19") (pin "1") (pinfunction "OUT_1") (pintype "output"))
    )
    (net (code "147") (name "Net-(U19-V-)") (class "Default")
      (node (ref "R134") (pin "1") (pinfunction "1_1") (pintype "passive"))
      (node (ref "R135") (pin "1") (pinfunction "1_1") (pintype "passive"))
      (node (ref "U19") (pin "2") (pinfunction "V-_2") (pintype "power_in"))
    )
    (net (code "148") (name "Net-(U20-CE)") (class "Default")
      (node (ref "R138") (pin "2") (pinfunction "2_2") (pintype "passive"))
      (node (ref "R139") (pin "1") (pinfunction "1_1") (pintype "passive"))
      (node (ref "U20") (pin "3") (pinfunction "CE_3") (pintype "input"))
    )
    (net (code "149") (name "Net-(U20-NC)") (class "Default")
      (node (ref "R137") (pin "1") (pinfunction "1_1") (pintype "passive"))
      (node (ref "U20") (pin "4") (pinfunction "NC_4") (pintype "passive"))
    )
    (net (code "150") (name "Output Current of FB to micro controller") (class "Default")
      (node (ref "FB12") (pin "2") (pinfunction "2_2") (pintype "power_in"))
      (node (ref "J2") (pin "2") (pinfunction "2_2") (pintype "passive"))
    )
    (net (code "151") (name "Output voltage of FB") (class "Default")
      (node (ref "FB13") (pin "2") (pinfunction "2_2") (pintype "power_in"))
      (node (ref "J2") (pin "3") (pinfunction "3_3") (pintype "passive"))
      (node (ref "TP47") (pin "1") (pinfunction "1_1") (pintype "passive"))
      (node (ref "TP60") (pin "1") (pinfunction "1_1") (pintype "passive"))
    )
    (net (code "152") (name "P1 OP37-2") (class "Default")
      (node (ref "R155") (pin "2") (pinfunction "2_2") (pintype "passive"))
      (node (ref "U21") (pin "1") (pinfunction "OFFSET_TRIM_1") (pintype "input"))
    )
    (net (code "153") (name "P2 OP37-2") (class "Default")
      (node (ref "C87") (pin "1") (pinfunction "1_1") (pintype "passive"))
      (node (ref "R158") (pin "1") (pinfunction "1_1") (pintype "passive"))
      (node (ref "R159") (pin "2") (pinfunction "2_2") (pintype "passive"))
      (node (ref "R169") (pin "2") (pinfunction "2_2") (pintype "passive"))
      (node (ref "R170") (pin "2") (pinfunction "2_2") (pintype "passive"))
      (node (ref "U21") (pin "2") (pinfunction "IN-_2") (pintype "input"))
    )
    (net (code "154") (name "P3 OP37-2") (class "Default")
      (node (ref "C86") (pin "1") (pinfunction "1_1") (pintype "passive"))
      (node (ref "R157") (pin "1") (pinfunction "1_1") (pintype "passive"))
      (node (ref "R164") (pin "1") (pinfunction "1_1") (pintype "passive"))
      (node (ref "U21") (pin "3") (pinfunction "IN+_3") (pintype "input"))
    )
    (net (code "155") (name "P4 OP37-2") (class "Default")
      (node (ref "R145") (pin "2") (pinfunction "2_2") (pintype "passive"))
      (node (ref "R146") (pin "2") (pinfunction "2_2") (pintype "passive"))
      (node (ref "U21") (pin "4") (pinfunction "VCC-_4") (pintype "power_in"))
    )
    (net (code "156") (name "P5 OP37-2") (class "Default")
      (node (ref "R143") (pin "1") (pinfunction "1_1") (pintype "passive"))
      (node (ref "U21") (pin "5") (pinfunction "NC_5") (pintype "passive"))
    )
    (net (code "157") (name "P6 OP37-2") (class "Default")
      (node (ref "C87") (pin "2") (pinfunction "2_2") (pintype "passive"))
      (node (ref "C88") (pin "1") (pinfunction "1_1") (pintype "passive"))
      (node (ref "R169") (pin "1") (pinfunction "1_1") (pintype "passive"))
      (node (ref "R170") (pin "1") (pinfunction "1_1") (pintype "passive"))
      (node (ref "R173") (pin "1") (pinfunction "1_1") (pintype "passive"))
      (node (ref "TP45") (pin "1") (pinfunction "1_1") (pintype "passive"))
      (node (ref "U21") (pin "6") (pinfunction "OUT_6") (pintype "output"))
    )
    (net (code "158") (name "P7 OP37-2") (class "Default")
      (node (ref "C80") (pin "1") (pinfunction "1_1") (pintype "passive"))
      (node (ref "R140") (pin "2") (pinfunction "2_2") (pintype "passive"))
      (node (ref "R144") (pin "2") (pinfunction "2_2") (pintype "passive"))
      (node (ref "U21") (pin "7") (pinfunction "VCC+_7") (pintype "power_in"))
    )
    (net (code "159") (name "P8 OP37-2") (class "Default")
      (node (ref "R165") (pin "2") (pinfunction "2_2") (pintype "passive"))
      (node (ref "U21") (pin "8") (pinfunction "OFFSET_TRIM_8") (pintype "input"))
    )
    (net (code "160") (name "Relay FB command") (class "Default")
      (node (ref "J2") (pin "11") (pinfunction "11_11") (pintype "passive"))
    )
    (net (code "161") (name "Source 1") (class "Default")
      (node (ref "C10") (pin "2") (pinfunction "2_2") (pintype "passive"))
      (node (ref "C14") (pin "1") (pinfunction "1_1") (pintype "passive"))
      (node (ref "C15") (pin "2") (pinfunction "2_2") (pintype "passive"))
      (node (ref "C16") (pin "2") (pinfunction "2_2") (pintype "passive"))
      (node (ref "C18") (pin "2") (pinfunction "2_2") (pintype "passive"))
      (node (ref "C19") (pin "1") (pinfunction "1_1") (pintype "passive"))
      (node (ref "C9") (pin "2") (pinfunction "2_2") (pintype "passive"))
      (node (ref "CR3") (pin "1") (pinfunction "A_1") (pintype "passive"))
      (node (ref "D13") (pin "2") (pinfunction "C_2") (pintype "passive"))
      (node (ref "D6") (pin "1") (pinfunction "A_1") (pintype "passive"))
      (node (ref "D7") (pin "1") (pinfunction "A_1") (pintype "passive"))
      (node (ref "D8") (pin "1") (pinfunction "A_1") (pintype "passive"))
      (node (ref "Q1") (pin "3") (pinfunction "E_3") (pintype "passive"))
      (node (ref "Q2") (pin "2") (pinfunction "C_2") (pintype "passive"))
      (node (ref "R20") (pin "1") (pinfunction "1_1") (pintype "passive"))
      (node (ref "R30") (pin "1") (pinfunction "1_1") (pintype "passive"))
      (node (ref "R33") (pin "1") (pinfunction "1_1") (pintype "passive"))
      (node (ref "R35") (pin "2") (pinfunction "2_2") (pintype "passive"))
      (node (ref "R52") (pin "2") (pinfunction "2_2") (pintype "passive"))
      (node (ref "R8") (pin "1") (pinfunction "1_1") (pintype "passive"))
      (node (ref "TP77") (pin "1") (pinfunction "1_1") (pintype "passive"))
      (node (ref "TP78") (pin "1") (pinfunction "1_1") (pintype "passive"))
      (node (ref "U17") (pin "1") (pinfunction "IN_1") (pintype "passive"))
      (node (ref "U17") (pin "2") (pinfunction "IN_2") (pintype "passive"))
      (node (ref "U17") (pin "3") (pinfunction "IN_3") (pintype "passive"))
      (node (ref "U6") (pin "4") (pinfunction "GND_4") (pintype "power_in"))
      (node (ref "U6") (pin "5") (pinfunction "GND_5") (pintype "power_in"))
    )
    (net (code "162") (name "Source 4") (class "Default")
      (node (ref "C11") (pin "2") (pinfunction "2_2") (pintype "passive"))
      (node (ref "C12") (pin "2") (pinfunction "2_2") (pintype "passive"))
      (node (ref "C13") (pin "2") (pinfunction "2_2") (pintype "passive"))
      (node (ref "C17") (pin "1") (pinfunction "1_1") (pintype "passive"))
      (node (ref "C23") (pin "1") (pinfunction "1_1") (pintype "passive"))
      (node (ref "C29") (pin "1") (pinfunction "1_1") (pintype "passive"))
      (node (ref "C65") (pin "2") (pinfunction "2_2") (pintype "passive"))
      (node (ref "C66") (pin "2") (pinfunction "2_2") (pintype "passive"))
      (node (ref "CR15") (pin "1") (pinfunction "A_1") (pintype "passive"))
      (node (ref "D10") (pin "1") (pinfunction "A_1") (pintype "passive"))
      (node (ref "D14") (pin "2") (pinfunction "C_2") (pintype "passive"))
      (node (ref "D5") (pin "1") (pinfunction "A_1") (pintype "passive"))
      (node (ref "D9") (pin "1") (pinfunction "A_1") (pintype "passive"))
      (node (ref "L1") (pin "2") (pinfunction "2_2") (pintype "passive"))
      (node (ref "Q3") (pin "2") (pinfunction "C_2") (pintype "passive"))
      (node (ref "Q4") (pin "3") (pinfunction "E_3") (pintype "passive"))
      (node (ref "R110") (pin "1") (pinfunction "1_1") (pintype "passive"))
      (node (ref "R120") (pin "1") (pinfunction "1_1") (pintype "passive"))
      (node (ref "R34") (pin "1") (pinfunction "1_1") (pintype "passive"))
      (node (ref "R36") (pin "2") (pinfunction "2_2") (pintype "passive"))
      (node (ref "R54") (pin "2") (pinfunction "2_2") (pintype "passive"))
      (node (ref "R90") (pin "1") (pinfunction "1_1") (pintype "passive"))
      (node (ref "TP75") (pin "1") (pinfunction "1_1") (pintype "passive"))
      (node (ref "TP76") (pin "1") (pinfunction "1_1") (pintype "passive"))
      (node (ref "U15") (pin "4") (pinfunction "GND_4") (pintype "power_in"))
      (node (ref "U15") (pin "5") (pinfunction "GND_5") (pintype "power_in"))
    )
    (net (code "163") (name "Spare Analog FB 1") (class "Default")
      (node (ref "J2") (pin "4") (pinfunction "4_4") (pintype "passive"))
    )
    (net (code "164") (name "Spare Analog FB 2") (class "Default")
      (node (ref "J2") (pin "17") (pinfunction "17_17") (pintype "passive"))
    )
    (net (code "165") (name "Spare Analog FB 3") (class "Default")
      (node (ref "J2") (pin "5") (pinfunction "5_5") (pintype "passive"))
    )
    (net (code "166") (name "Spare Analog FB 4") (class "Default")
      (node (ref "J2") (pin "18") (pinfunction "18_18") (pintype "passive"))
    )
    (net (code "167") (name "Spare Dig FB 1") (class "Default")
      (node (ref "J2") (pin "20") (pinfunction "20_20") (pintype "passive"))
    )
    (net (code "168") (name "Spare Dig FB 2") (class "Default")
      (node (ref "J2") (pin "7") (pinfunction "7_7") (pintype "passive"))
    )
    (net (code "169") (name "Spare Dig FB 3") (class "Default")
      (node (ref "J2") (pin "19") (pinfunction "19_19") (pintype "passive"))
    )
    (net (code "170") (name "Spare Dig FB 4") (class "Default")
      (node (ref "J2") (pin "6") (pinfunction "6_6") (pintype "passive"))
    )
    (net (code "171") (name "VDD Sensor voltage out") (class "Default")
      (node (ref "C85") (pin "1") (pinfunction "1_1") (pintype "passive"))
      (node (ref "Q5") (pin "1") (pinfunction "VDD1_1") (pintype "power_in"))
    )
    (net (code "172") (name "VGS 1") (class "Default")
      (node (ref "C10") (pin "1") (pinfunction "1_1") (pintype "passive"))
      (node (ref "C14") (pin "2") (pinfunction "2_2") (pintype "passive"))
      (node (ref "C47") (pin "1") (pinfunction "1_1") (pintype "passive"))
      (node (ref "C48") (pin "2") (pinfunction "2_2") (pintype "passive"))
      (node (ref "C6") (pin "1") (pinfunction "1_1") (pintype "passive"))
      (node (ref "C7") (pin "1") (pinfunction "1_1") (pintype "passive"))
      (node (ref "C8") (pin "2") (pinfunction "2_2") (pintype "passive"))
      (node (ref "C9") (pin "1") (pinfunction "1_1") (pintype "passive"))
      (node (ref "CR1") (pin "2") (pinfunction "K_2") (pintype "passive"))
      (node (ref "CR4") (pin "2") (pinfunction "K_2") (pintype "passive"))
      (node (ref "D7") (pin "2") (pinfunction "K_2") (pintype "passive"))
      (node (ref "DS6") (pin "1") (pinfunction "A_1") (pintype "passive"))
      (node (ref "PS1") (pin "14") (pinfunction "+VOUT_14") (pintype "output"))
      (node (ref "TP35") (pin "1") (pinfunction "1_1") (pintype "passive"))
      (node (ref "TP70") (pin "1") (pinfunction "1_1") (pintype "passive"))
      (node (ref "U5") (pin "6") (pinfunction "VDD_6") (pintype "power_in"))
      (node (ref "U6") (pin "1") (pinfunction "VCC_1") (pintype "power_in"))
      (node (ref "U6") (pin "8") (pinfunction "VCC_8") (pintype "power_in"))
    )
    (net (code "173") (name "VGS 2") (class "Default")
      (node (ref "C32") (pin "2") (pinfunction "2_2") (pintype "passive"))
      (node (ref "C33") (pin "1") (pinfunction "1_1") (pintype "passive"))
      (node (ref "C34") (pin "1") (pinfunction "1_1") (pintype "passive"))
      (node (ref "C36") (pin "2") (pinfunction "2_2") (pintype "passive"))
      (node (ref "C37") (pin "1") (pinfunction "1_1") (pintype "passive"))
      (node (ref "C38") (pin "1") (pinfunction "1_1") (pintype "passive"))
      (node (ref "C50") (pin "1") (pinfunction "1_1") (pintype "passive"))
      (node (ref "C51") (pin "2") (pinfunction "2_2") (pintype "passive"))
      (node (ref "CR5") (pin "2") (pinfunction "K_2") (pintype "passive"))
      (node (ref "CR8") (pin "2") (pinfunction "K_2") (pintype "passive"))
      (node (ref "D17") (pin "2") (pinfunction "K_2") (pintype "passive"))
      (node (ref "DS7") (pin "1") (pinfunction "A_1") (pintype "passive"))
      (node (ref "PS2") (pin "14") (pinfunction "+VOUT_14") (pintype "output"))
      (node (ref "TP54") (pin "1") (pinfunction "1_1") (pintype "passive"))
      (node (ref "TP81") (pin "1") (pinfunction "1_1") (pintype "passive"))
      (node (ref "U8") (pin "6") (pinfunction "VDD_6") (pintype "power_in"))
      (node (ref "U9") (pin "1") (pinfunction "VCC_1") (pintype "power_in"))
      (node (ref "U9") (pin "8") (pinfunction "VCC_8") (pintype "power_in"))
    )
    (net (code "174") (name "VGS 3") (class "Default")
      (node (ref "C35") (pin "2") (pinfunction "2_2") (pintype "passive"))
      (node (ref "C42") (pin "1") (pinfunction "1_1") (pintype "passive"))
      (node (ref "C43") (pin "1") (pinfunction "1_1") (pintype "passive"))
      (node (ref "C44") (pin "2") (pinfunction "2_2") (pintype "passive"))
      (node (ref "C45") (pin "1") (pinfunction "1_1") (pintype "passive"))
      (node (ref "C46") (pin "1") (pinfunction "1_1") (pintype "passive"))
      (node (ref "C54") (pin "2") (pinfunction "2_2") (pintype "passive"))
      (node (ref "C55") (pin "1") (pinfunction "1_1") (pintype "passive"))
      (node (ref "CR12") (pin "2") (pinfunction "K_2") (pintype "passive"))
      (node (ref "CR9") (pin "2") (pinfunction "K_2") (pintype "passive"))
      (node (ref "D18") (pin "2") (pinfunction "K_2") (pintype "passive"))
      (node (ref "DS8") (pin "1") (pinfunction "A_1") (pintype "passive"))
      (node (ref "PS3") (pin "14") (pinfunction "+VOUT_14") (pintype "output"))
      (node (ref "TP58") (pin "1") (pinfunction "1_1") (pintype "passive"))
      (node (ref "TP82") (pin "1") (pinfunction "1_1") (pintype "passive"))
      (node (ref "U11") (pin "6") (pinfunction "VDD_6") (pintype "power_in"))
      (node (ref "U12") (pin "1") (pinfunction "VCC_1") (pintype "power_in"))
      (node (ref "U12") (pin "8") (pinfunction "VCC_8") (pintype "power_in"))
    )
    (net (code "175") (name "VGS 4") (class "Default")
      (node (ref "C17") (pin "2") (pinfunction "2_2") (pintype "passive"))
      (node (ref "C57") (pin "1") (pinfunction "1_1") (pintype "passive"))
      (node (ref "C58") (pin "1") (pinfunction "1_1") (pintype "passive"))
      (node (ref "C59") (pin "2") (pinfunction "2_2") (pintype "passive"))
      (node (ref "C61") (pin "1") (pinfunction "1_1") (pintype "passive"))
      (node (ref "C65") (pin "1") (pinfunction "1_1") (pintype "passive"))
      (node (ref "C66") (pin "1") (pinfunction "1_1") (pintype "passive"))
      (node (ref "C67") (pin "2") (pinfunction "2_2") (pintype "passive"))
      (node (ref "CR13") (pin "2") (pinfunction "K_2") (pintype "passive"))
      (node (ref "CR16") (pin "2") (pinfunction "K_2") (pintype "passive"))
      (node (ref "D9") (pin "2") (pinfunction "K_2") (pintype "passive"))
      (node (ref "DS11") (pin "1") (pinfunction "A_1") (pintype "passive"))
      (node (ref "PS4") (pin "14") (pinfunction "+VOUT_14") (pintype "output"))
      (node (ref "TP62") (pin "1") (pinfunction "1_1") (pintype "passive"))
      (node (ref "TP72") (pin "1") (pinfunction "1_1") (pintype "passive"))
      (node (ref "U14") (pin "6") (pinfunction "VDD_6") (pintype "power_in"))
      (node (ref "U15") (pin "1") (pinfunction "VCC_1") (pintype "power_in"))
      (node (ref "U15") (pin "8") (pinfunction "VCC_8") (pintype "power_in"))
    )
    (net (code "176") (name "unconnected-(J2-PadM1)") (class "Default")
      (node (ref "J2") (pin "M1") (pinfunction "M1_M1") (pintype "passive"))
    )
    (net (code "177") (name "unconnected-(J2-PadM2)") (class "Default")
      (node (ref "J2") (pin "M2") (pinfunction "M2_M2") (pintype "passive"))
    )
    (net (code "178") (name "unconnected-(PS1-NC-Pad9)") (class "Default")
      (node (ref "PS1") (pin "9") (pinfunction "NC_9") (pintype "passive"))
    )
    (net (code "179") (name "unconnected-(PS1-NC1-Pad11)") (class "Default")
      (node (ref "PS1") (pin "11") (pinfunction "NC1_11") (pintype "passive"))
    )
    (net (code "180") (name "unconnected-(PS2-NC-Pad9)") (class "Default")
      (node (ref "PS2") (pin "9") (pinfunction "NC_9") (pintype "passive"))
    )
    (net (code "181") (name "unconnected-(PS2-NC1-Pad11)") (class "Default")
      (node (ref "PS2") (pin "11") (pinfunction "NC1_11") (pintype "passive"))
    )
    (net (code "182") (name "unconnected-(PS3-NC-Pad9)") (class "Default")
      (node (ref "PS3") (pin "9") (pinfunction "NC_9") (pintype "passive"))
    )
    (net (code "183") (name "unconnected-(PS3-NC1-Pad11)") (class "Default")
      (node (ref "PS3") (pin "11") (pinfunction "NC1_11") (pintype "passive"))
    )
    (net (code "184") (name "unconnected-(PS4-NC-Pad9)") (class "Default")
      (node (ref "PS4") (pin "9") (pinfunction "NC_9") (pintype "passive"))
    )
    (net (code "185") (name "unconnected-(PS4-NC1-Pad11)") (class "Default")
      (node (ref "PS4") (pin "11") (pinfunction "NC1_11") (pintype "passive"))
    )
    (net (code "186") (name "unconnected-(U1-trim-Pad4)") (class "Default")
      (node (ref "U1") (pin "4") (pinfunction "trim_4") (pintype "passive"))
    )
  )
)
